# STM32F446_front_pane_-_south_-_v3.net
KiCad netlist of a schematic drawn in EAGLE
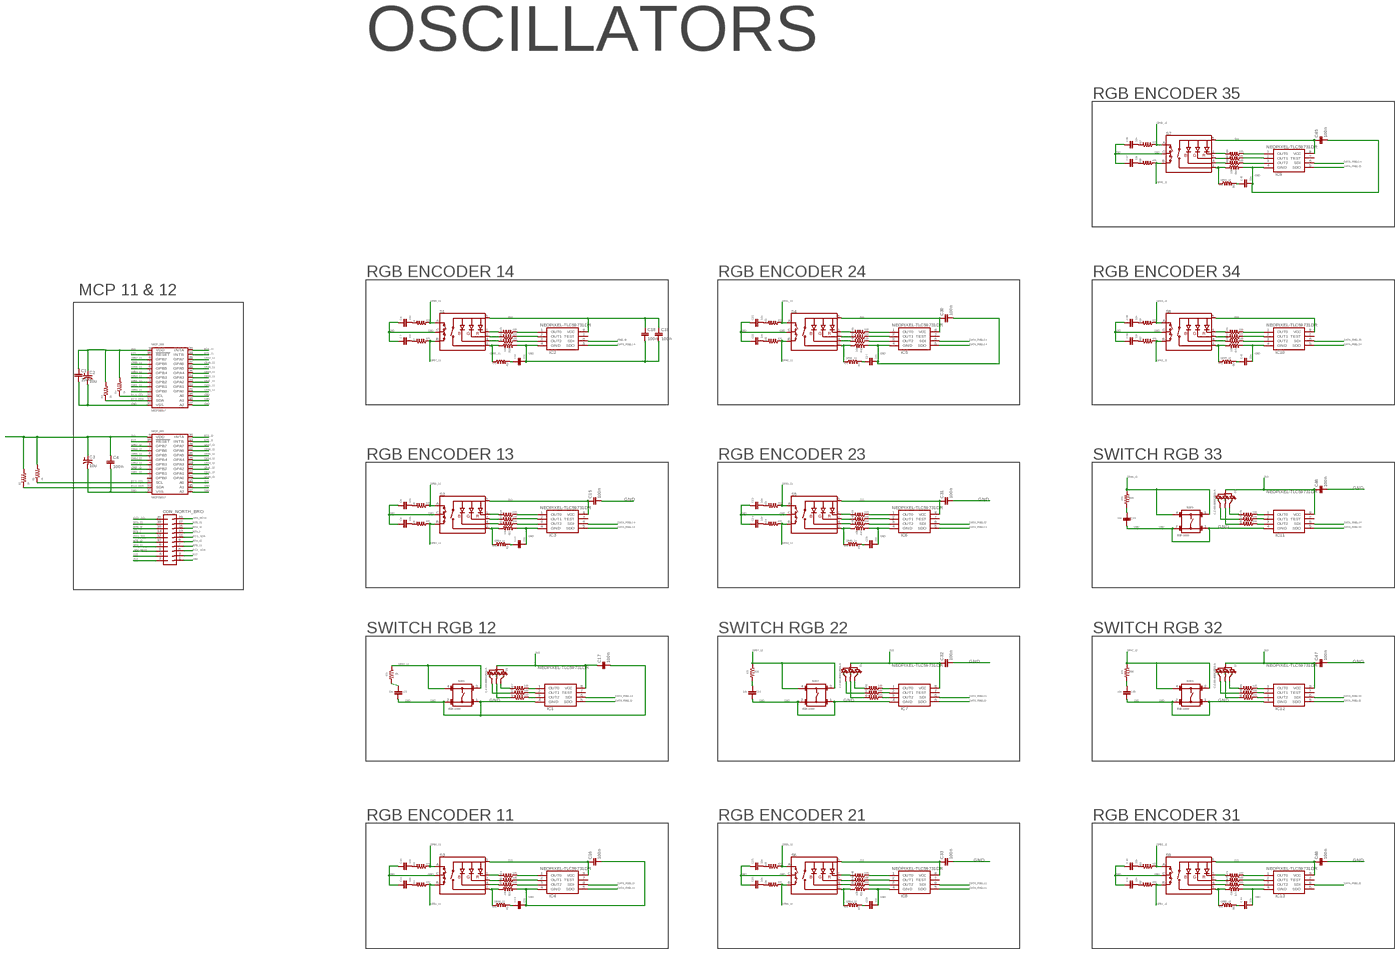
[diagram p0: schematic, sheet 1, overview]
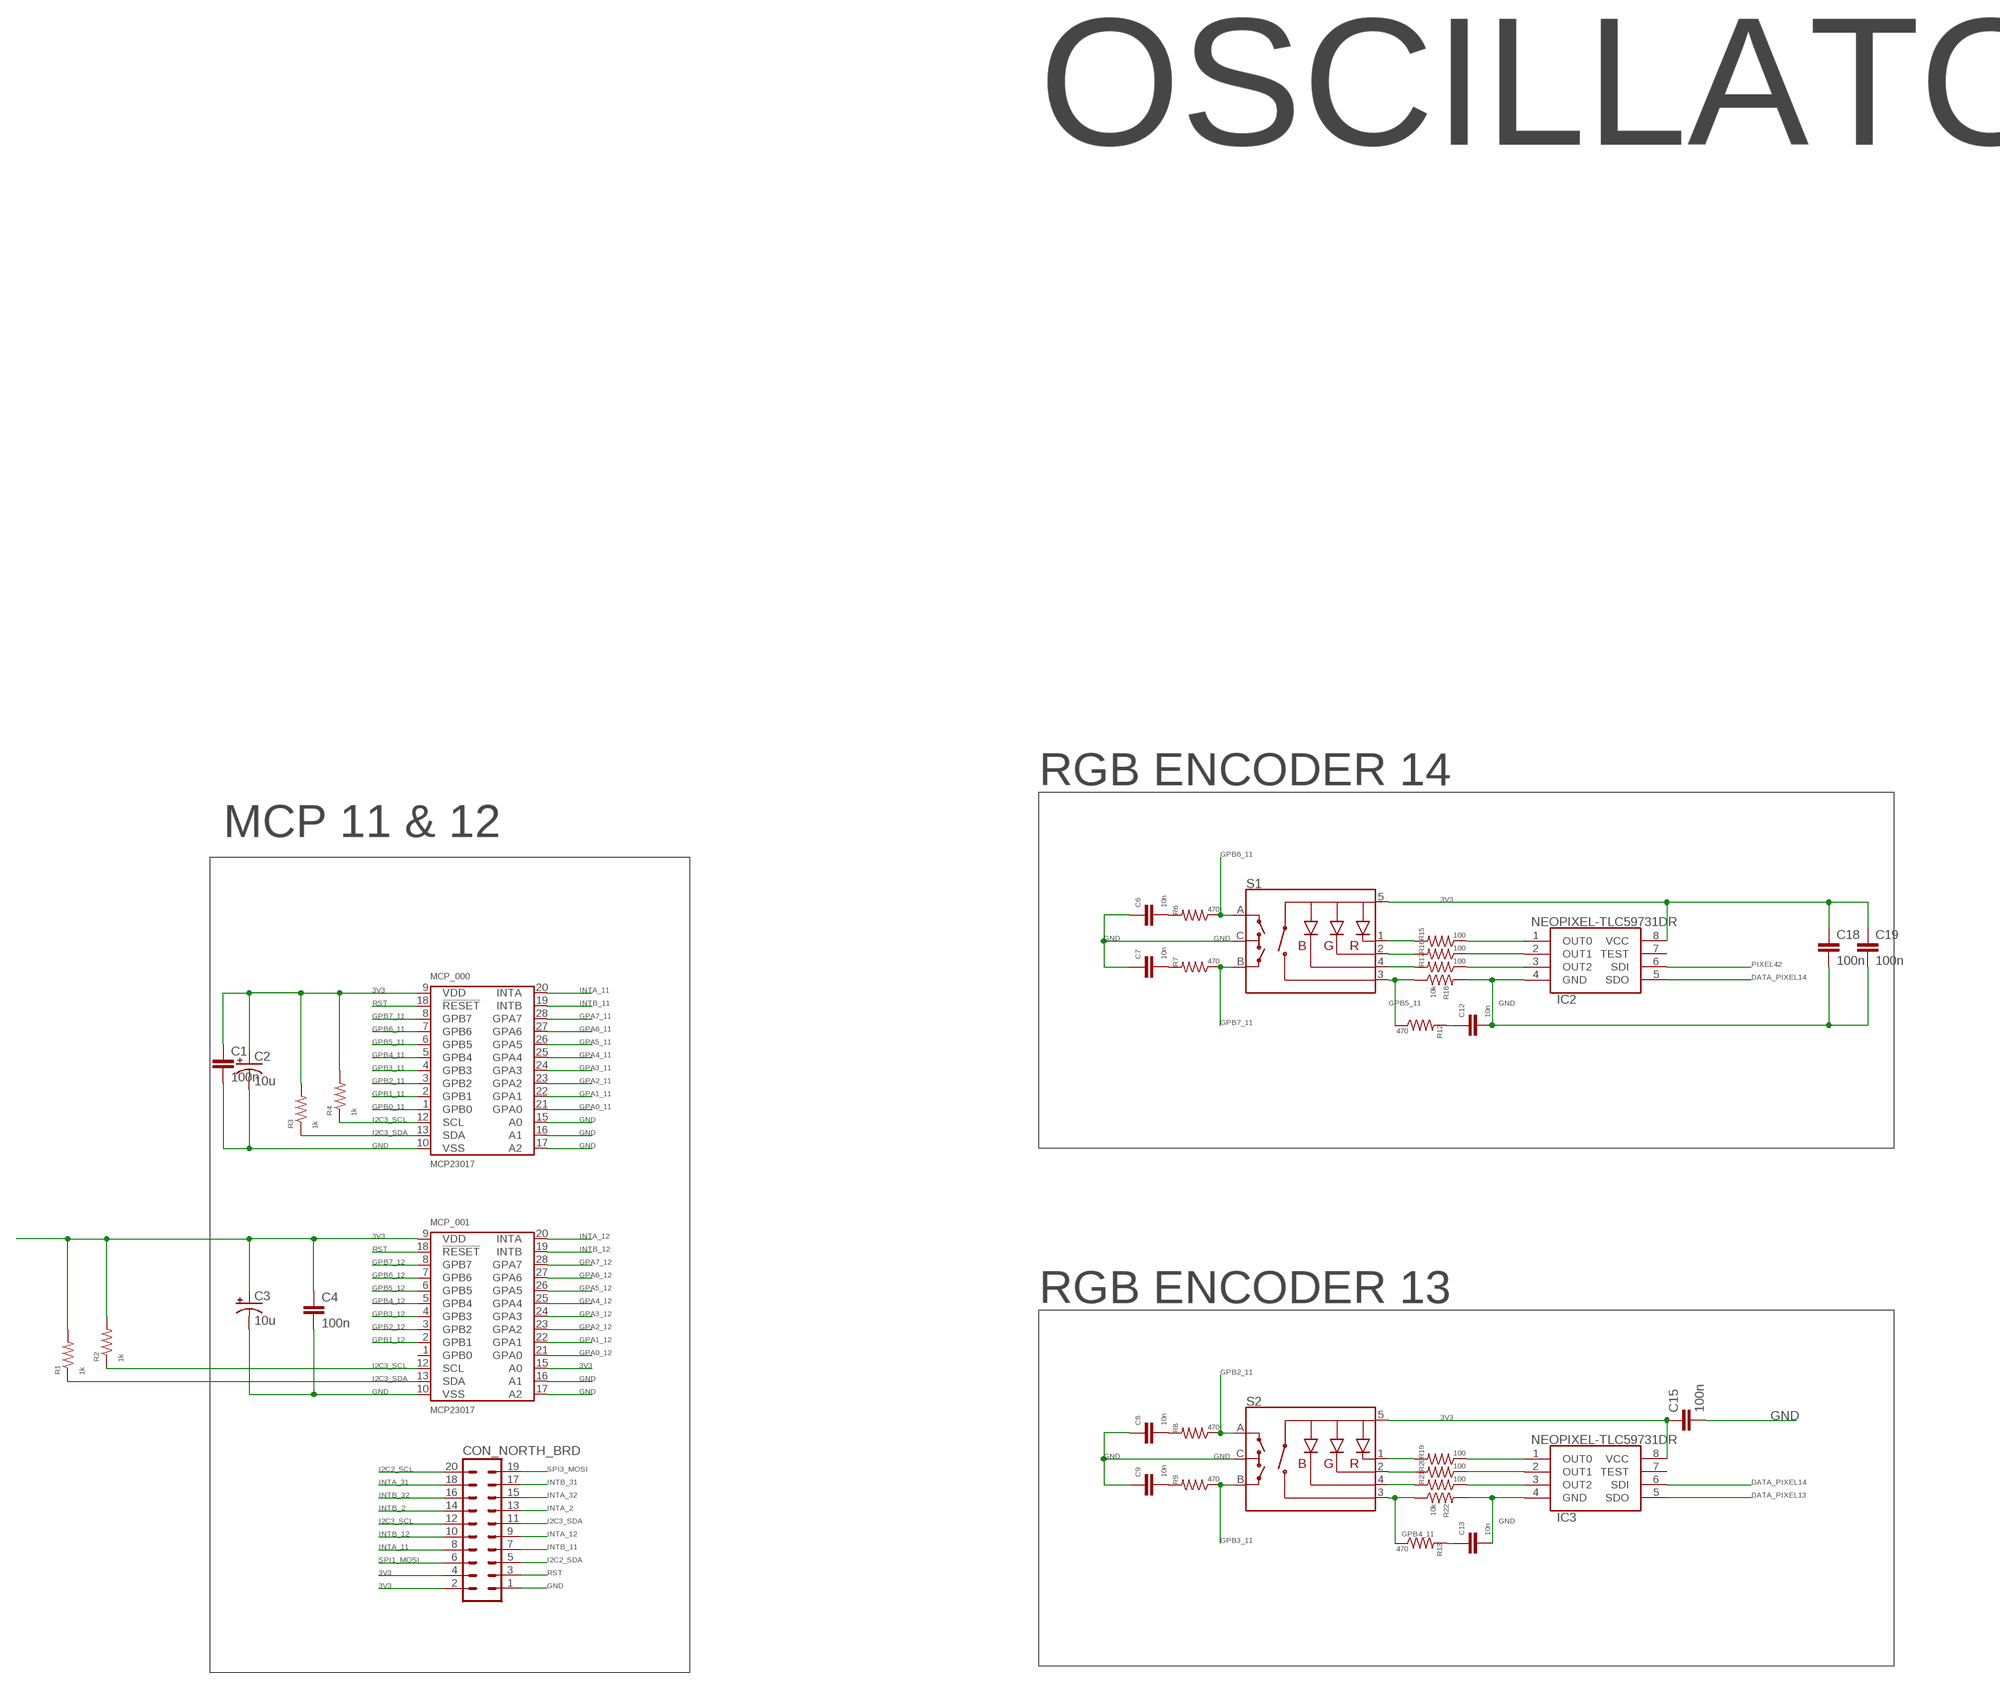
[diagram p1: schematic, sheet 1, part 1 of 4]
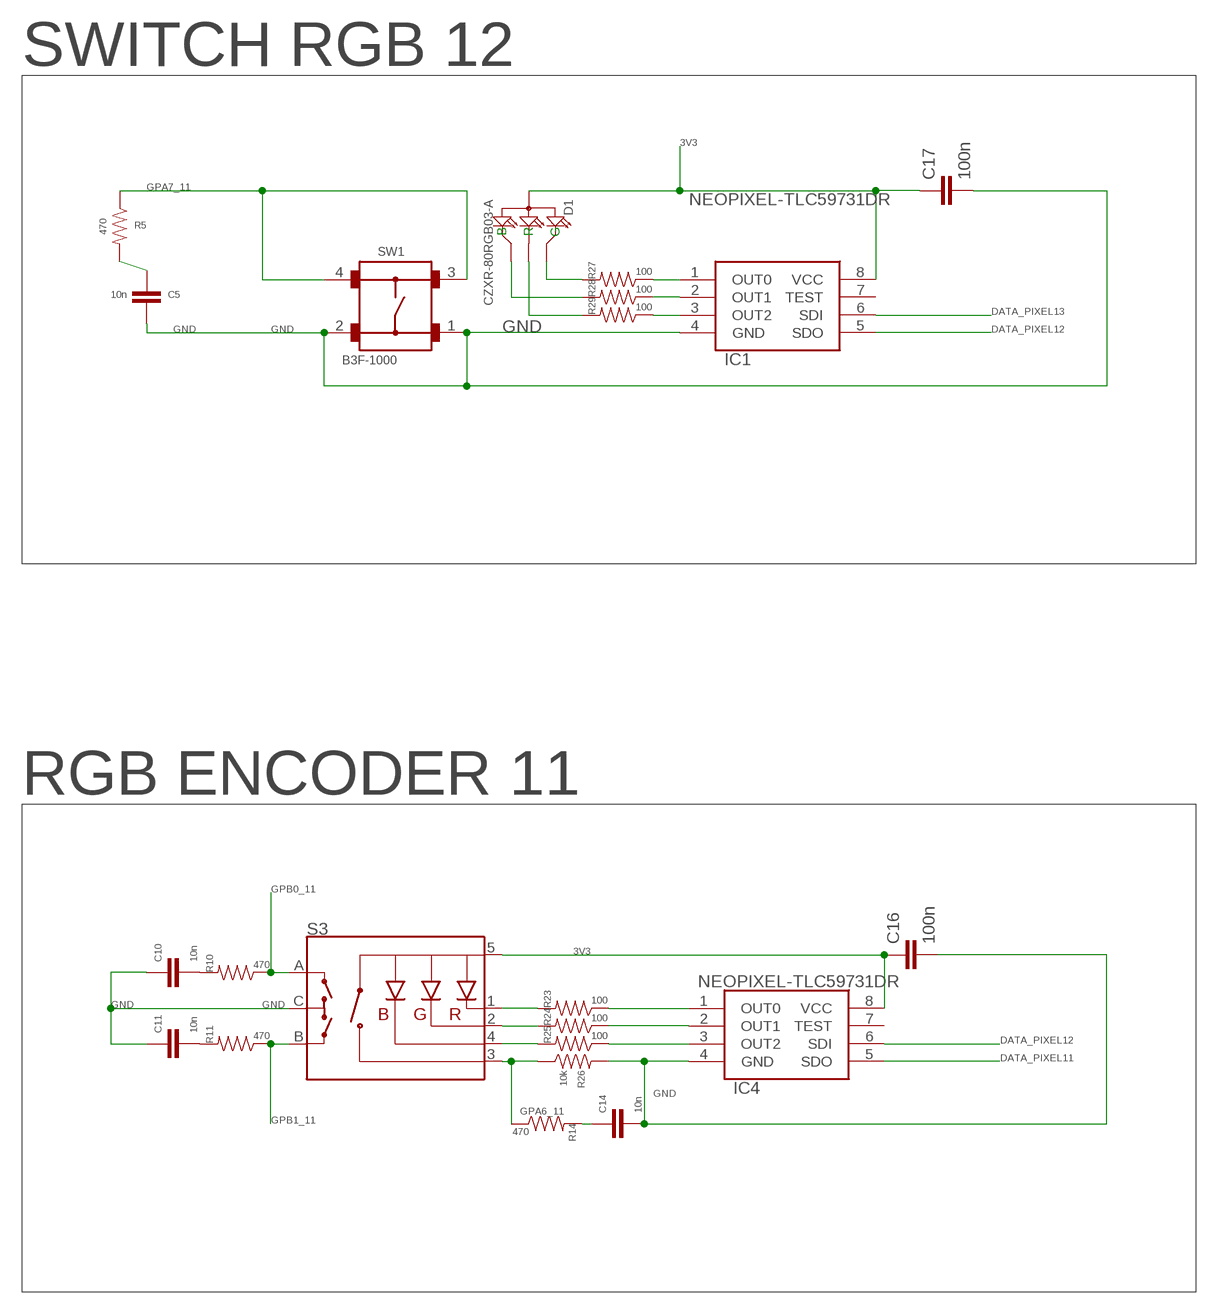
[diagram p2: schematic, sheet 1, part 2 of 4]
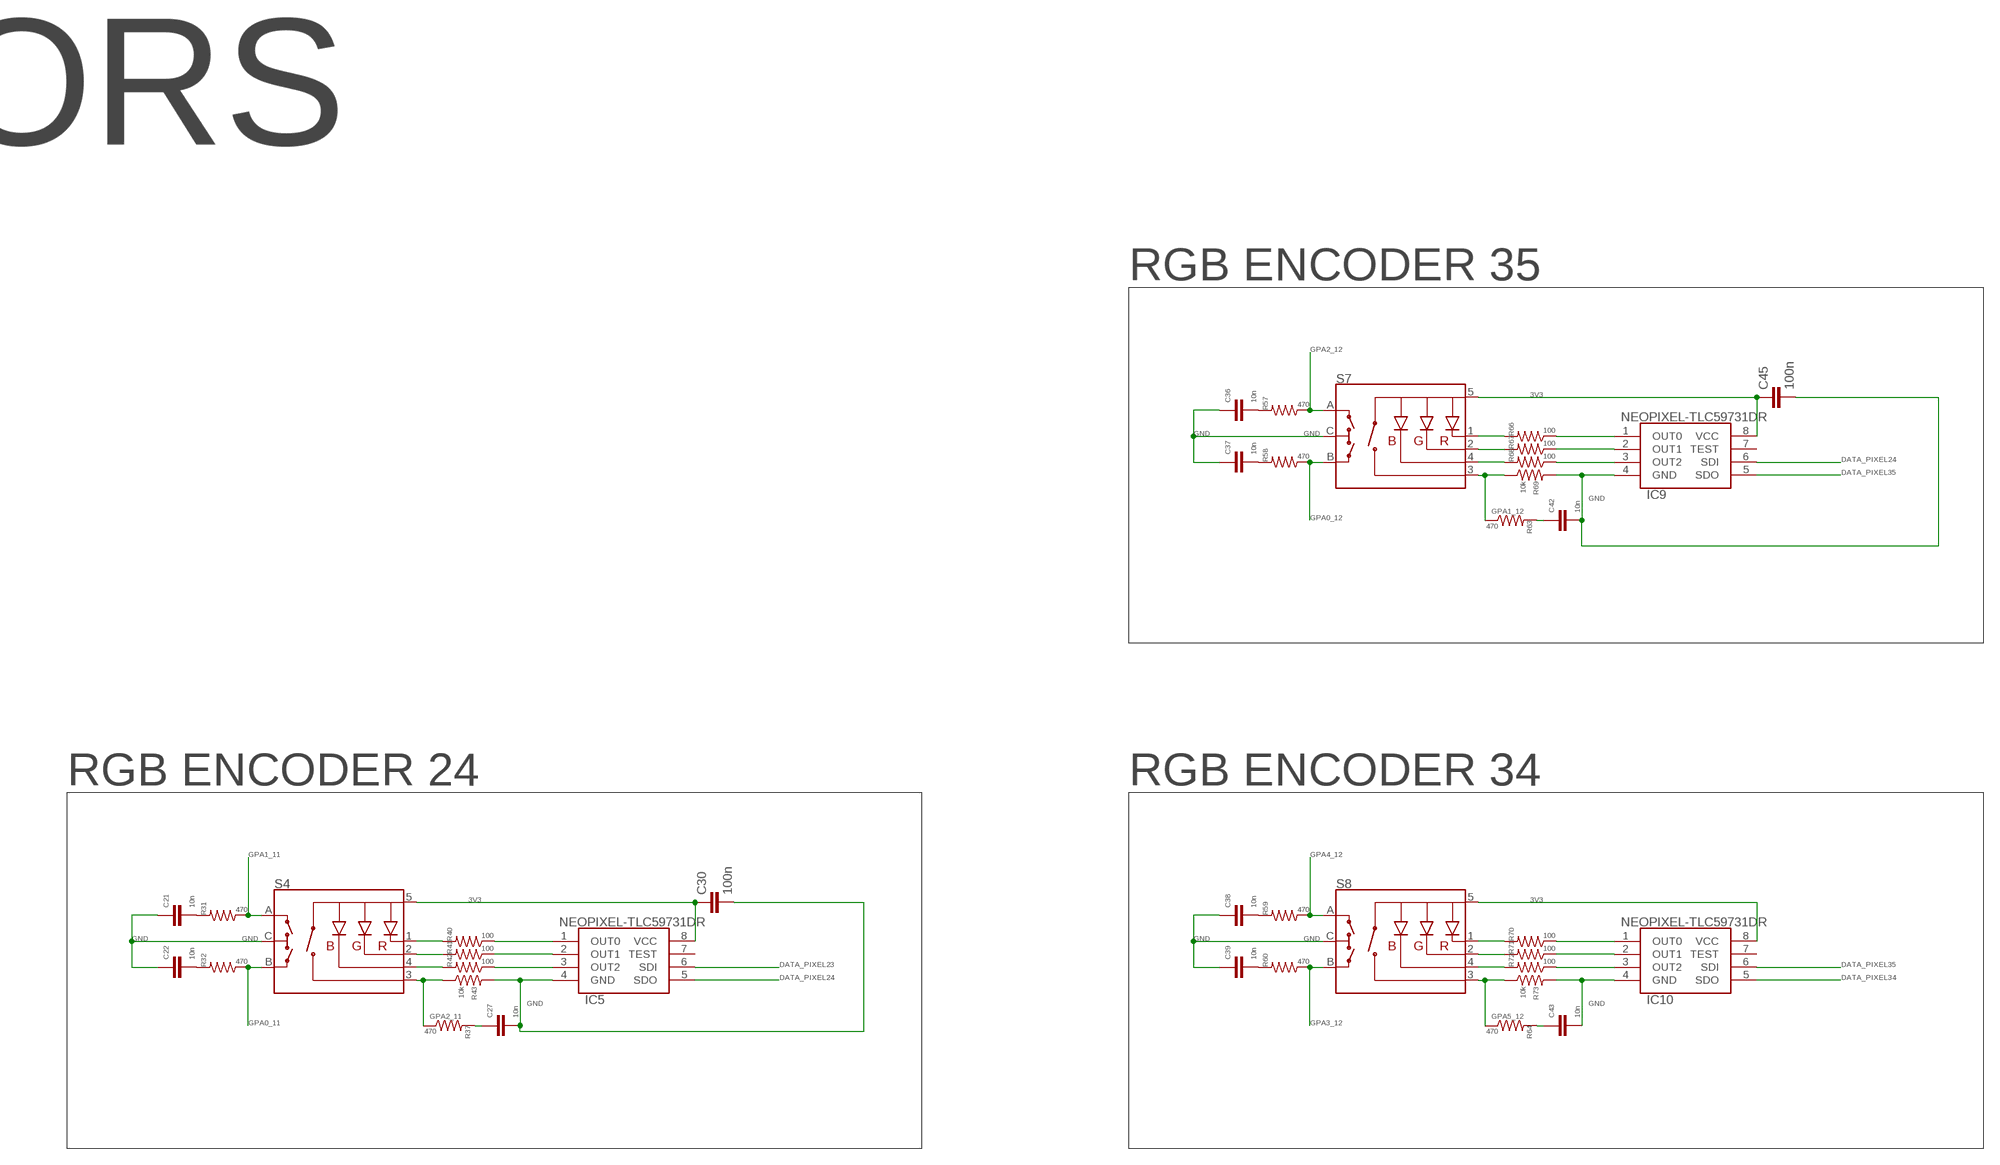
[diagram p3: schematic, sheet 1, part 3 of 4]
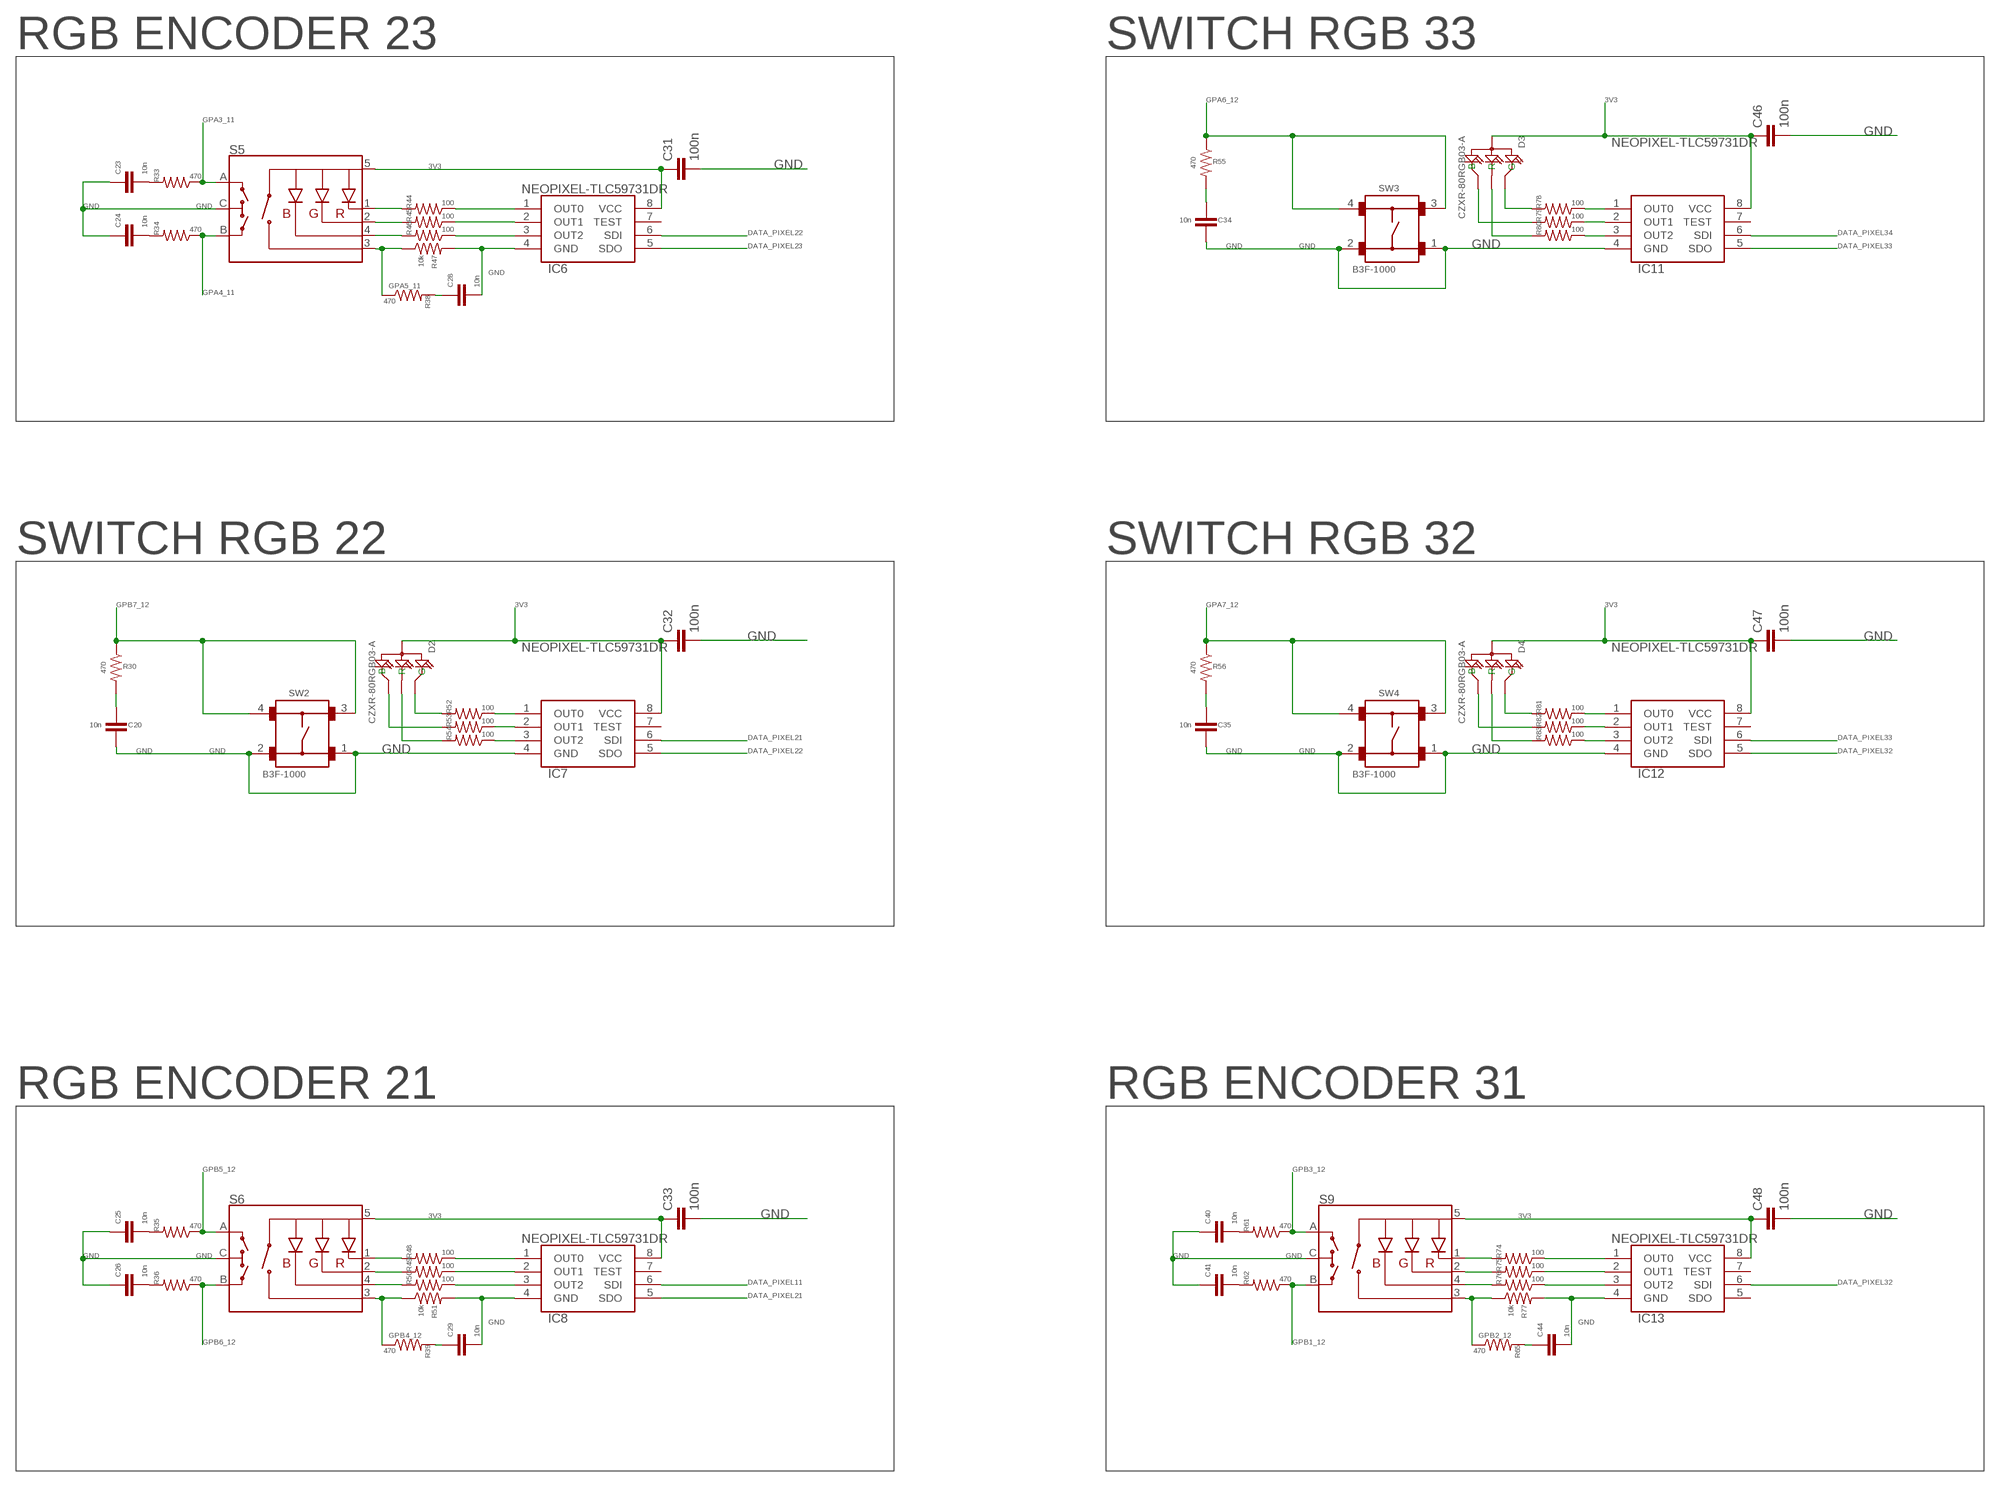
[diagram p4: schematic, sheet 1, part 4 of 4]
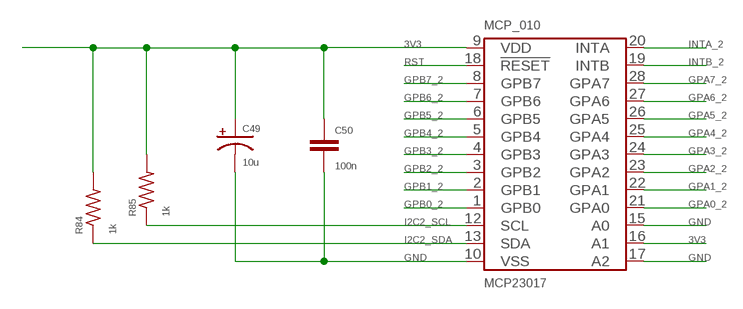
[diagram p5: schematic, sheet 2, part 1 of 2]
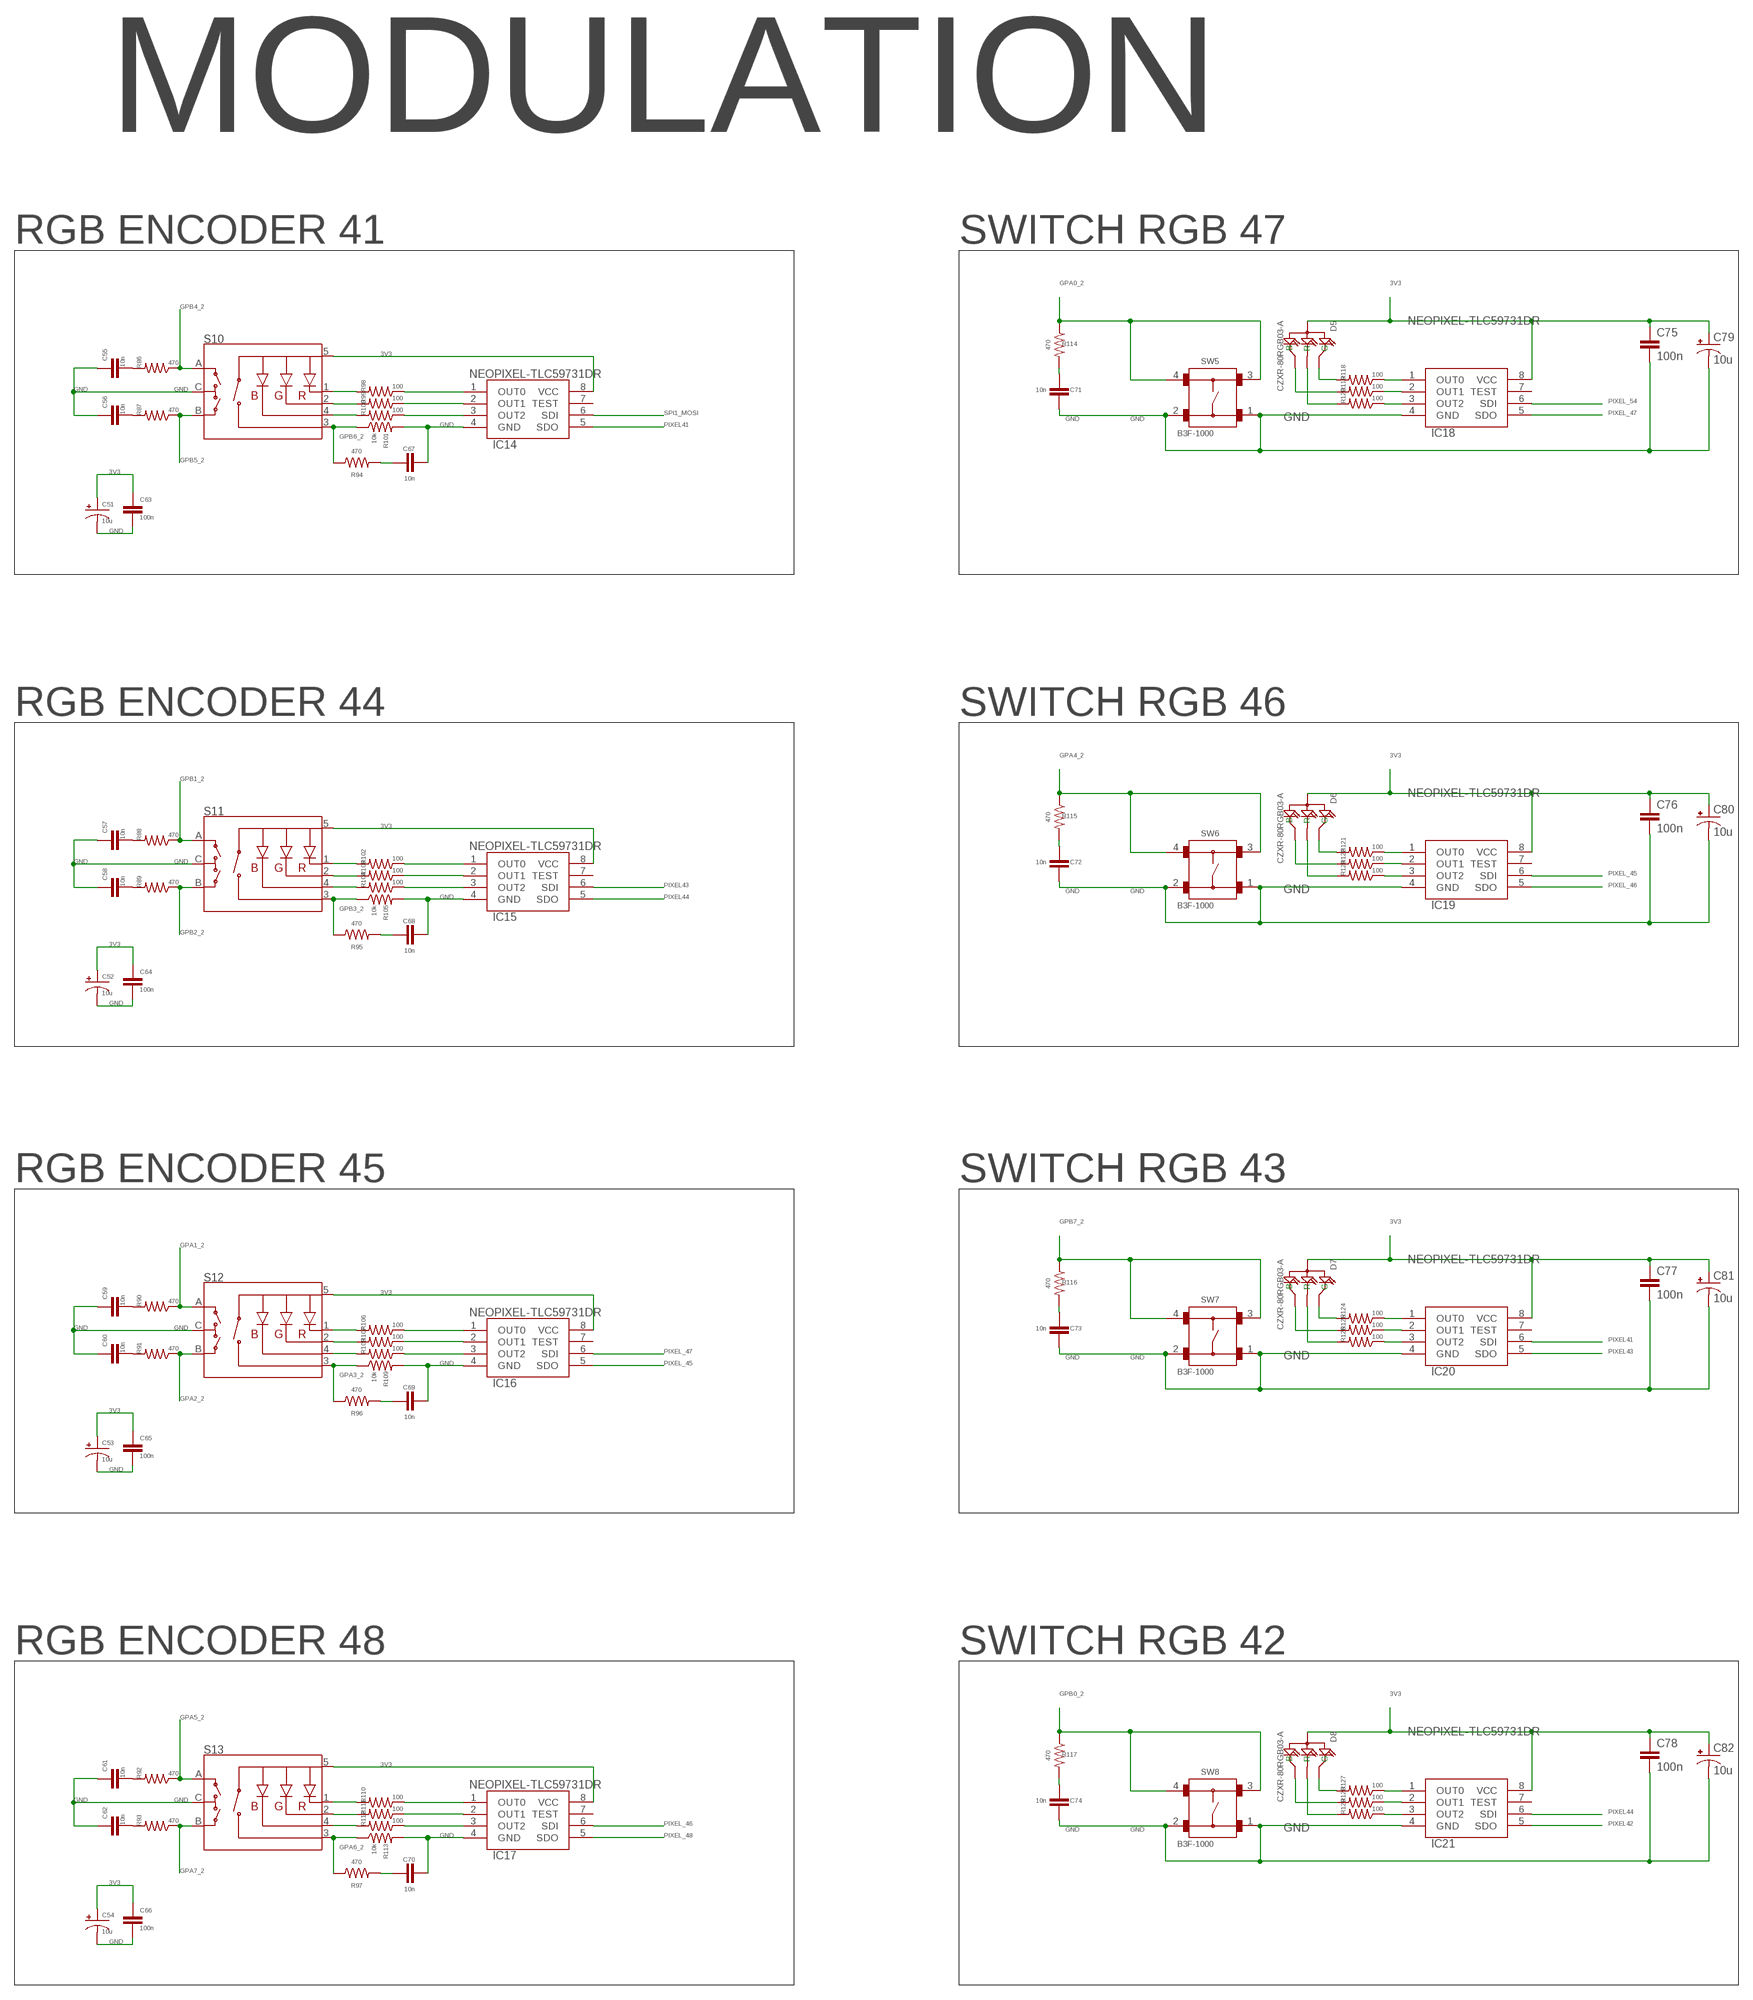
[diagram p6: schematic, sheet 2, part 2 of 2]
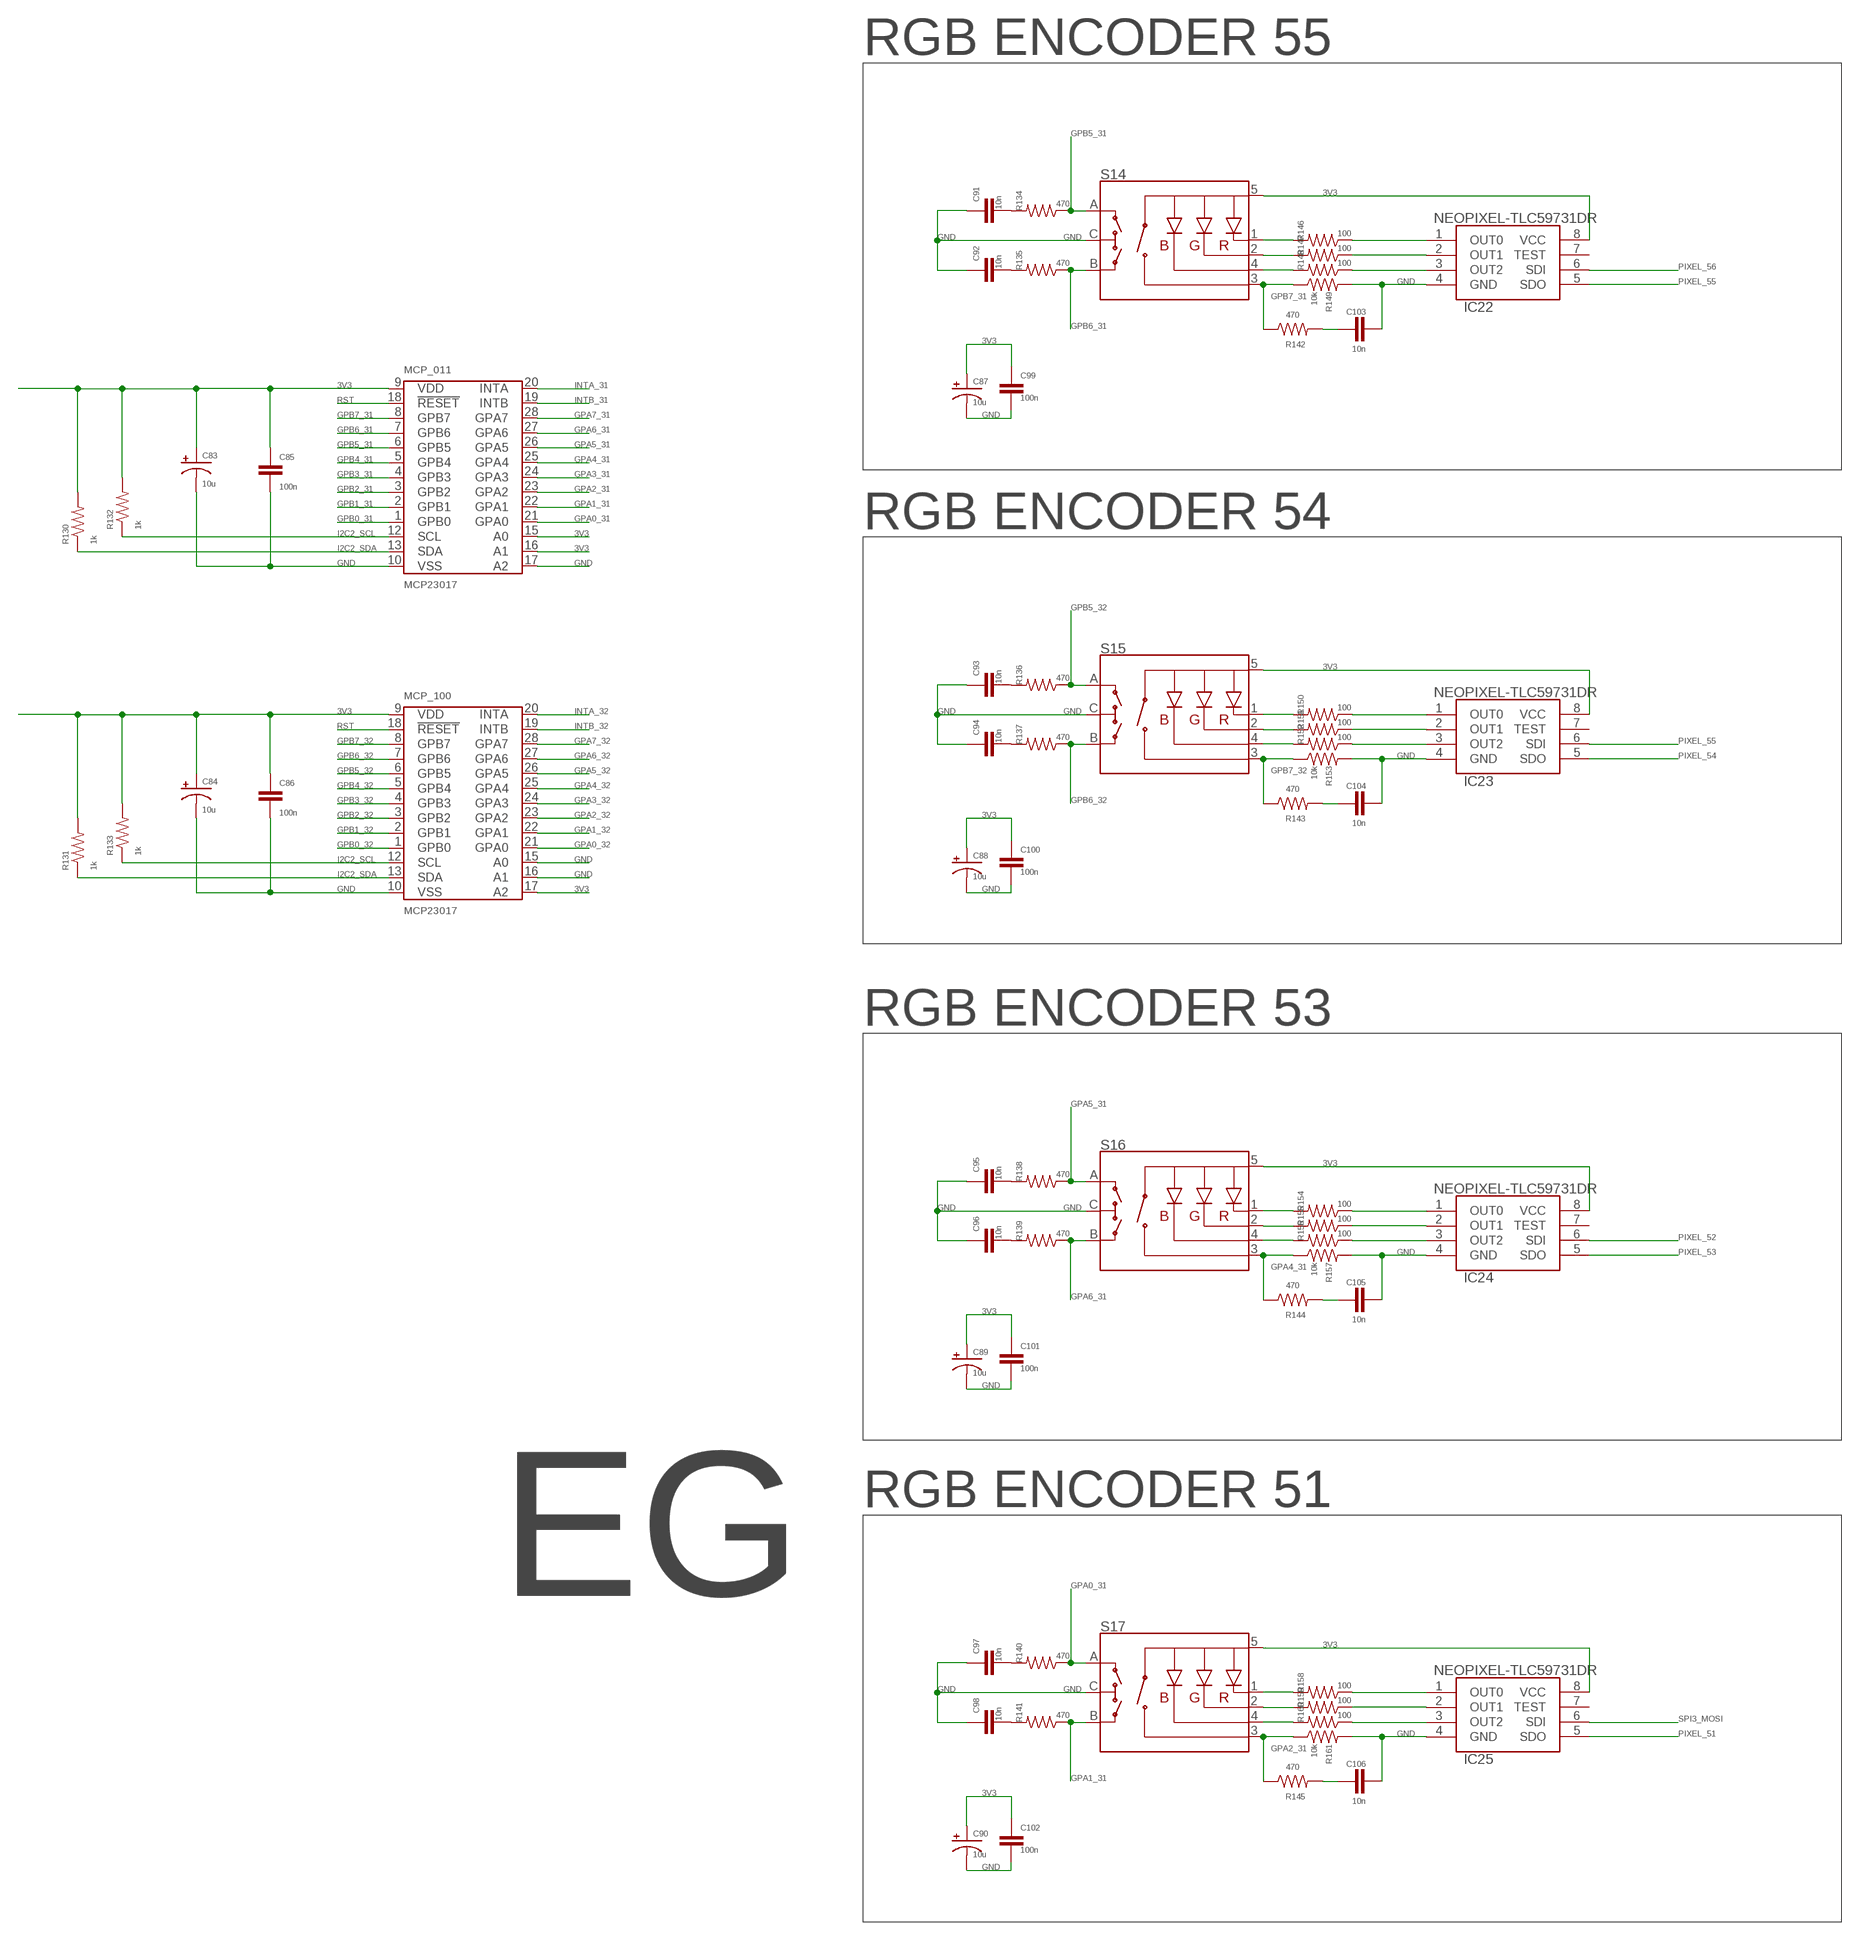
[diagram p7: schematic, sheet 3, part 1 of 2]
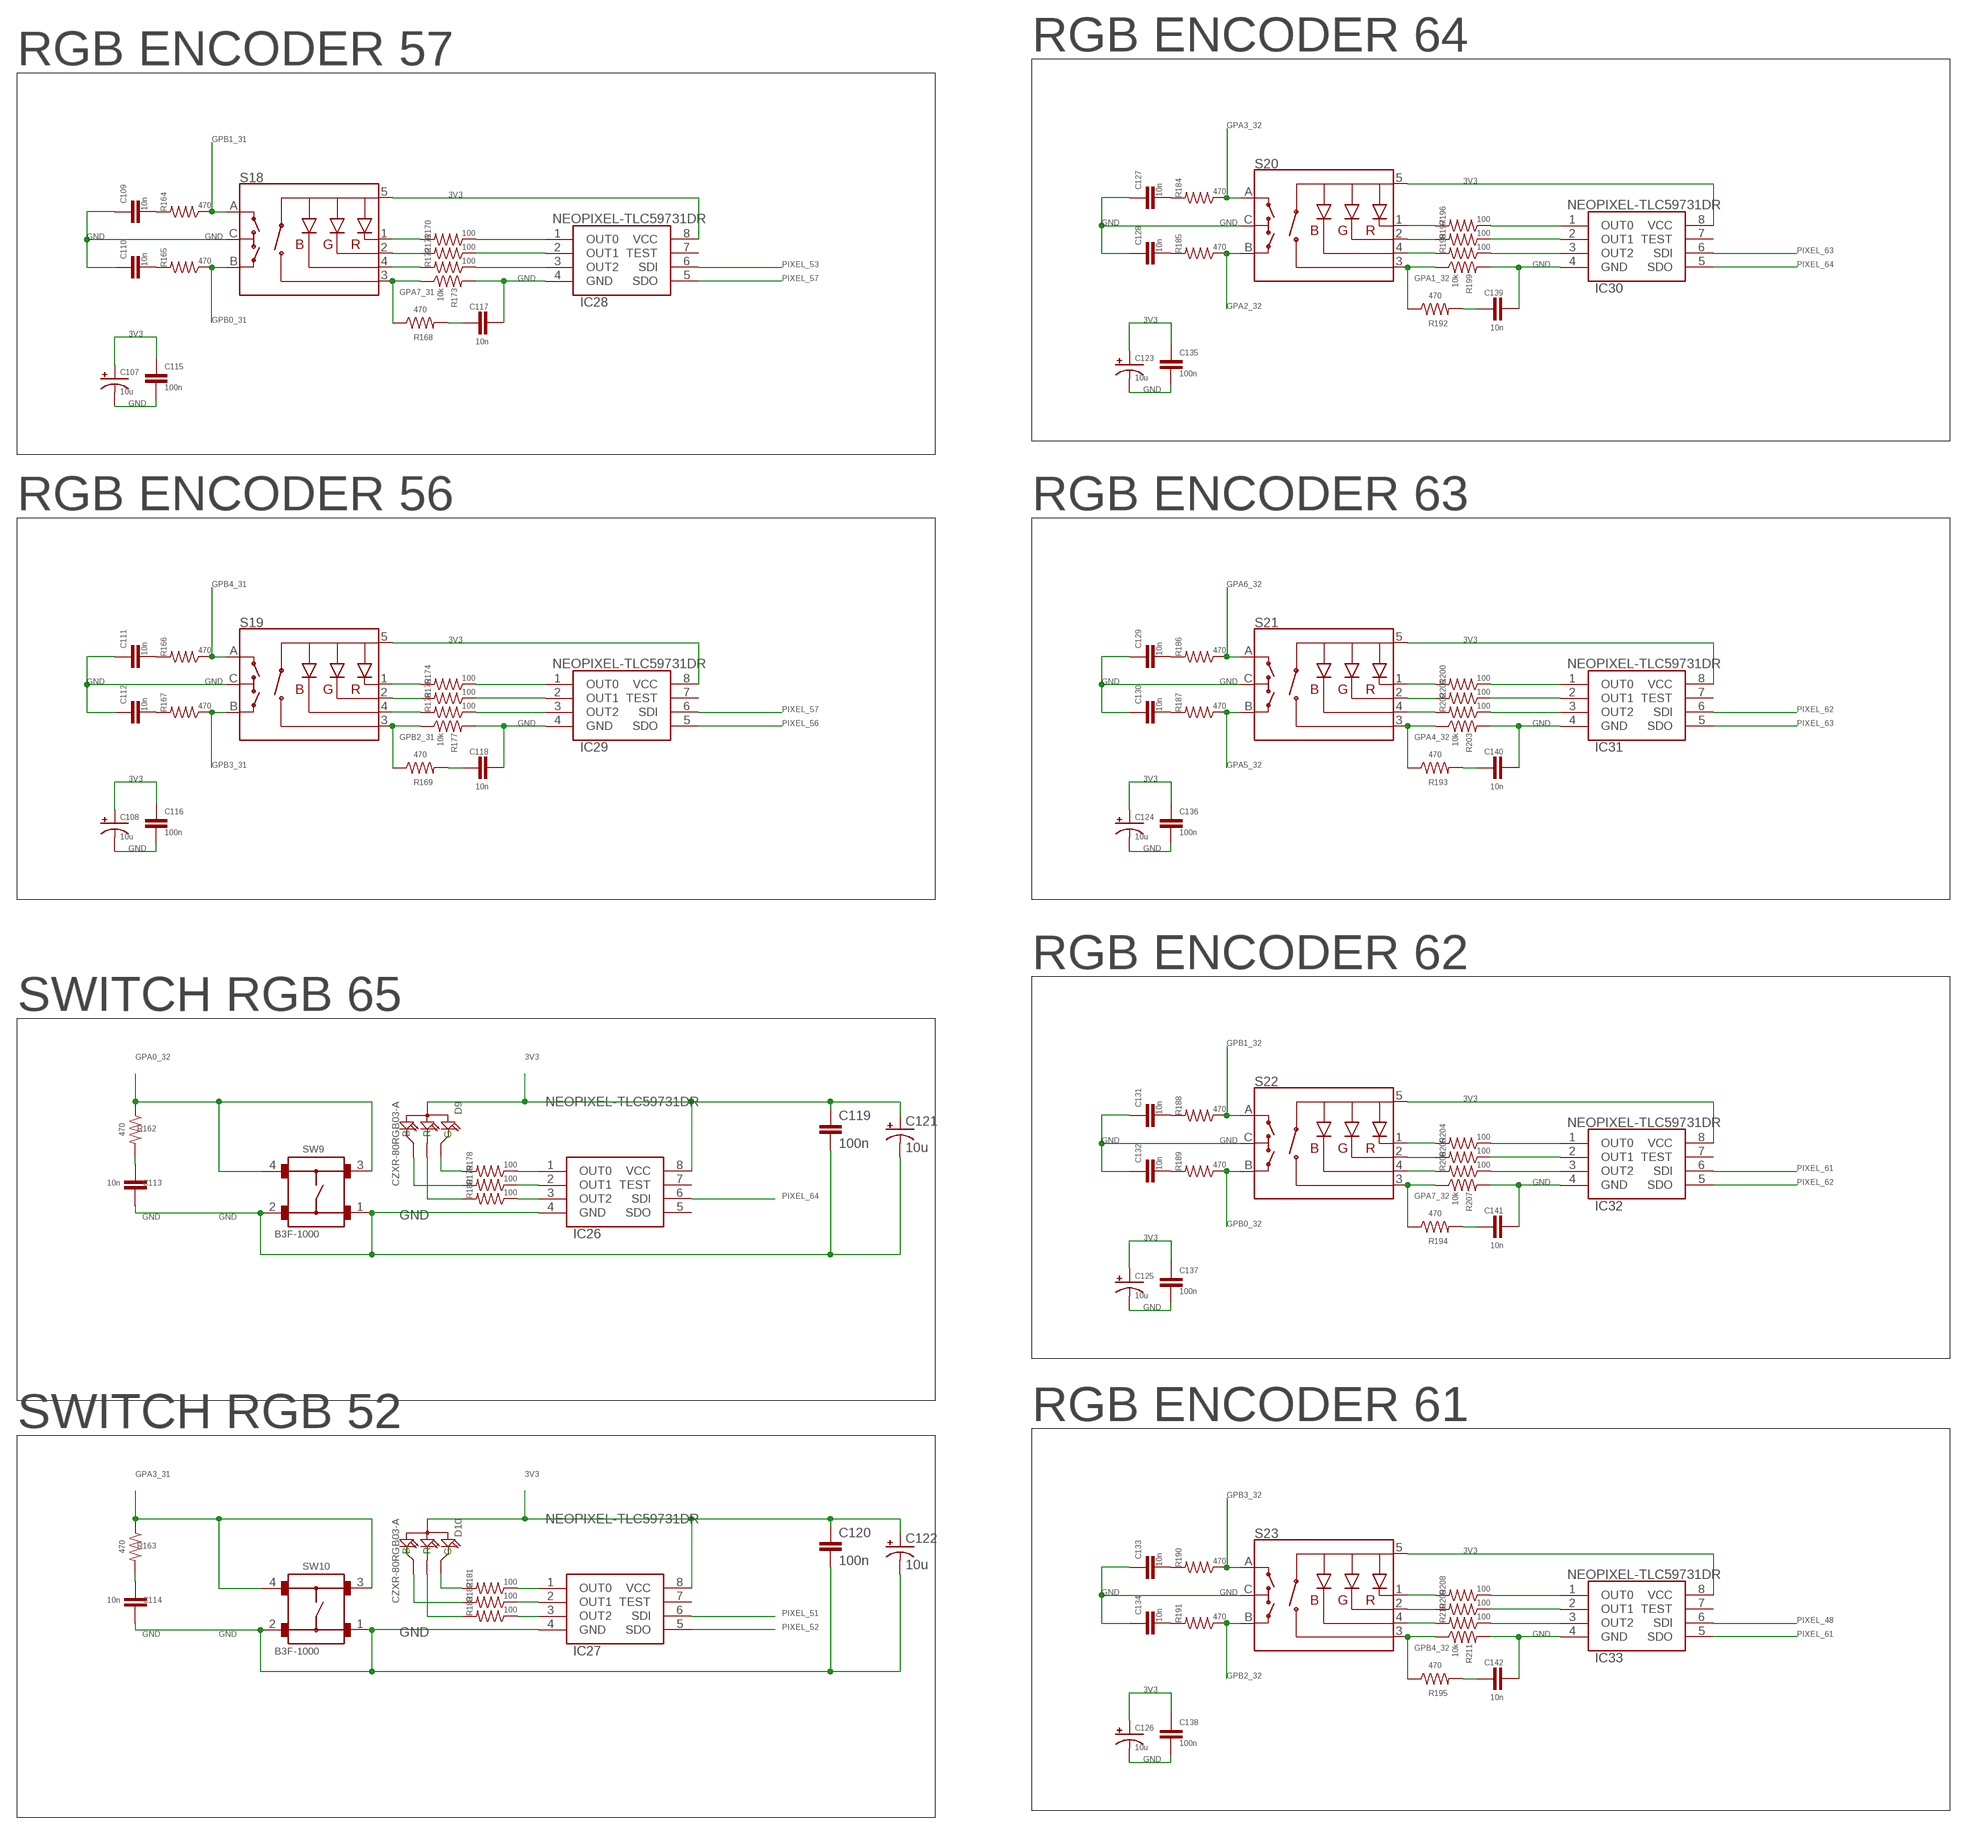
[diagram p8: schematic, sheet 3, part 2 of 2]

(export (version "E")
  (design (tool "Eeschema 10.0.6"))
  (components
    (comp (ref "C83")
      (value "10u")
      (footprint "eagle-import:CPOL2917")
      (libsource (lib "eagle-import") (part "PASSIF-CPOL-US2917"))
    )
    (comp (ref "C84")
      (value "10u")
      (footprint "eagle-import:CPOL2917")
      (libsource (lib "eagle-import") (part "PASSIF-CPOL-US2917"))
    )
    (comp (ref "C85")
      (value "100n")
      (footprint "eagle-import:0805-CAP")
      (libsource (lib "eagle-import") (part "PASSIF-CAP-0805"))
    )
    (comp (ref "C86")
      (value "100n")
      (footprint "eagle-import:0805-CAP")
      (libsource (lib "eagle-import") (part "PASSIF-CAP-0805"))
    )
    (comp (ref "C87")
      (value "10u")
      (footprint "eagle-import:CPOL2917")
      (libsource (lib "eagle-import") (part "PASSIF-CPOL-US2917"))
    )
    (comp (ref "C88")
      (value "10u")
      (footprint "eagle-import:CPOL2917")
      (libsource (lib "eagle-import") (part "PASSIF-CPOL-US2917"))
    )
    (comp (ref "C89")
      (value "10u")
      (footprint "eagle-import:CPOL2917")
      (libsource (lib "eagle-import") (part "PASSIF-CPOL-US2917"))
    )
    (comp (ref "C90")
      (value "10u")
      (footprint "eagle-import:CPOL2917")
      (libsource (lib "eagle-import") (part "PASSIF-CPOL-US2917"))
    )
    (comp (ref "C91")
      (value "10n")
      (footprint "eagle-import:0805-CAP")
      (libsource (lib "eagle-import") (part "PASSIF-CAP-0805"))
    )
    (comp (ref "C92")
      (value "10n")
      (footprint "eagle-import:0805-CAP")
      (libsource (lib "eagle-import") (part "PASSIF-CAP-0805"))
    )
    (comp (ref "C93")
      (value "10n")
      (footprint "eagle-import:0805-CAP")
      (libsource (lib "eagle-import") (part "PASSIF-CAP-0805"))
    )
    (comp (ref "C94")
      (value "10n")
      (footprint "eagle-import:0805-CAP")
      (libsource (lib "eagle-import") (part "PASSIF-CAP-0805"))
    )
    (comp (ref "C95")
      (value "10n")
      (footprint "eagle-import:0805-CAP")
      (libsource (lib "eagle-import") (part "PASSIF-CAP-0805"))
    )
    (comp (ref "C96")
      (value "10n")
      (footprint "eagle-import:0805-CAP")
      (libsource (lib "eagle-import") (part "PASSIF-CAP-0805"))
    )
    (comp (ref "C97")
      (value "10n")
      (footprint "eagle-import:0805-CAP")
      (libsource (lib "eagle-import") (part "PASSIF-CAP-0805"))
    )
    (comp (ref "C98")
      (value "10n")
      (footprint "eagle-import:0805-CAP")
      (libsource (lib "eagle-import") (part "PASSIF-CAP-0805"))
    )
    (comp (ref "C99")
      (value "100n")
      (footprint "eagle-import:0805-CAP")
      (libsource (lib "eagle-import") (part "PASSIF-CAP-0805"))
    )
    (comp (ref "C100")
      (value "100n")
      (footprint "eagle-import:0805-CAP")
      (libsource (lib "eagle-import") (part "PASSIF-CAP-0805"))
    )
    (comp (ref "C101")
      (value "100n")
      (footprint "eagle-import:0805-CAP")
      (libsource (lib "eagle-import") (part "PASSIF-CAP-0805"))
    )
    (comp (ref "C102")
      (value "100n")
      (footprint "eagle-import:0805-CAP")
      (libsource (lib "eagle-import") (part "PASSIF-CAP-0805"))
    )
    (comp (ref "C103")
      (value "10n")
      (footprint "eagle-import:0805-CAP")
      (libsource (lib "eagle-import") (part "PASSIF-CAP-0805"))
    )
    (comp (ref "C104")
      (value "10n")
      (footprint "eagle-import:0805-CAP")
      (libsource (lib "eagle-import") (part "PASSIF-CAP-0805"))
    )
    (comp (ref "C105")
      (value "10n")
      (footprint "eagle-import:0805-CAP")
      (libsource (lib "eagle-import") (part "PASSIF-CAP-0805"))
    )
    (comp (ref "C106")
      (value "10n")
      (footprint "eagle-import:0805-CAP")
      (libsource (lib "eagle-import") (part "PASSIF-CAP-0805"))
    )
    (comp (ref "C107")
      (value "10u")
      (footprint "eagle-import:CPOL2917")
      (libsource (lib "eagle-import") (part "PASSIF-CPOL-US2917"))
    )
    (comp (ref "C108")
      (value "10u")
      (footprint "eagle-import:CPOL2917")
      (libsource (lib "eagle-import") (part "PASSIF-CPOL-US2917"))
    )
    (comp (ref "C109")
      (value "10n")
      (footprint "eagle-import:0805-CAP")
      (libsource (lib "eagle-import") (part "PASSIF-CAP-0805"))
    )
    (comp (ref "C110")
      (value "10n")
      (footprint "eagle-import:0805-CAP")
      (libsource (lib "eagle-import") (part "PASSIF-CAP-0805"))
    )
    (comp (ref "C111")
      (value "10n")
      (footprint "eagle-import:0805-CAP")
      (libsource (lib "eagle-import") (part "PASSIF-CAP-0805"))
    )
    (comp (ref "C112")
      (value "10n")
      (footprint "eagle-import:0805-CAP")
      (libsource (lib "eagle-import") (part "PASSIF-CAP-0805"))
    )
    (comp (ref "C113")
      (value "10n")
      (footprint "eagle-import:0805-CAP")
      (libsource (lib "eagle-import") (part "PASSIF-CAP-0805"))
    )
    (comp (ref "C114")
      (value "10n")
      (footprint "eagle-import:0805-CAP")
      (libsource (lib "eagle-import") (part "PASSIF-CAP-0805"))
    )
    (comp (ref "C115")
      (value "100n")
      (footprint "eagle-import:0805-CAP")
      (libsource (lib "eagle-import") (part "PASSIF-CAP-0805"))
    )
    (comp (ref "C116")
      (value "100n")
      (footprint "eagle-import:0805-CAP")
      (libsource (lib "eagle-import") (part "PASSIF-CAP-0805"))
    )
    (comp (ref "C117")
      (value "10n")
      (footprint "eagle-import:0805-CAP")
      (libsource (lib "eagle-import") (part "PASSIF-CAP-0805"))
    )
    (comp (ref "C118")
      (value "10n")
      (footprint "eagle-import:0805-CAP")
      (libsource (lib "eagle-import") (part "PASSIF-CAP-0805"))
    )
    (comp (ref "C119")
      (value "100n")
      (footprint "eagle-import:0805-CAP")
      (libsource (lib "eagle-import") (part "PASSIF-CAP-0805"))
    )
    (comp (ref "C120")
      (value "100n")
      (footprint "eagle-import:0805-CAP")
      (libsource (lib "eagle-import") (part "PASSIF-CAP-0805"))
    )
    (comp (ref "C121")
      (value "10u")
      (footprint "eagle-import:CPOL2917")
      (libsource (lib "eagle-import") (part "PASSIF-CPOL-US2917"))
    )
    (comp (ref "C122")
      (value "10u")
      (footprint "eagle-import:CPOL2917")
      (libsource (lib "eagle-import") (part "PASSIF-CPOL-US2917"))
    )
    (comp (ref "C123")
      (value "10u")
      (footprint "eagle-import:CPOL2917")
      (libsource (lib "eagle-import") (part "PASSIF-CPOL-US2917"))
    )
    (comp (ref "C124")
      (value "10u")
      (footprint "eagle-import:CPOL2917")
      (libsource (lib "eagle-import") (part "PASSIF-CPOL-US2917"))
    )
    (comp (ref "C125")
      (value "10u")
      (footprint "eagle-import:CPOL2917")
      (libsource (lib "eagle-import") (part "PASSIF-CPOL-US2917"))
    )
    (comp (ref "C126")
      (value "10u")
      (footprint "eagle-import:CPOL2917")
      (libsource (lib "eagle-import") (part "PASSIF-CPOL-US2917"))
    )
    (comp (ref "C127")
      (value "10n")
      (footprint "eagle-import:0805-CAP")
      (libsource (lib "eagle-import") (part "PASSIF-CAP-0805"))
    )
    (comp (ref "C128")
      (value "10n")
      (footprint "eagle-import:0805-CAP")
      (libsource (lib "eagle-import") (part "PASSIF-CAP-0805"))
    )
    (comp (ref "C129")
      (value "10n")
      (footprint "eagle-import:0805-CAP")
      (libsource (lib "eagle-import") (part "PASSIF-CAP-0805"))
    )
    (comp (ref "C130")
      (value "10n")
      (footprint "eagle-import:0805-CAP")
      (libsource (lib "eagle-import") (part "PASSIF-CAP-0805"))
    )
    (comp (ref "C131")
      (value "10n")
      (footprint "eagle-import:0805-CAP")
      (libsource (lib "eagle-import") (part "PASSIF-CAP-0805"))
    )
    (comp (ref "C132")
      (value "10n")
      (footprint "eagle-import:0805-CAP")
      (libsource (lib "eagle-import") (part "PASSIF-CAP-0805"))
    )
    (comp (ref "C133")
      (value "10n")
      (footprint "eagle-import:0805-CAP")
      (libsource (lib "eagle-import") (part "PASSIF-CAP-0805"))
    )
    (comp (ref "C134")
      (value "10n")
      (footprint "eagle-import:0805-CAP")
      (libsource (lib "eagle-import") (part "PASSIF-CAP-0805"))
    )
    (comp (ref "C135")
      (value "100n")
      (footprint "eagle-import:0805-CAP")
      (libsource (lib "eagle-import") (part "PASSIF-CAP-0805"))
    )
    (comp (ref "C136")
      (value "100n")
      (footprint "eagle-import:0805-CAP")
      (libsource (lib "eagle-import") (part "PASSIF-CAP-0805"))
    )
    (comp (ref "C137")
      (value "100n")
      (footprint "eagle-import:0805-CAP")
      (libsource (lib "eagle-import") (part "PASSIF-CAP-0805"))
    )
    (comp (ref "C138")
      (value "100n")
      (footprint "eagle-import:0805-CAP")
      (libsource (lib "eagle-import") (part "PASSIF-CAP-0805"))
    )
    (comp (ref "C139")
      (value "10n")
      (footprint "eagle-import:0805-CAP")
      (libsource (lib "eagle-import") (part "PASSIF-CAP-0805"))
    )
    (comp (ref "C140")
      (value "10n")
      (footprint "eagle-import:0805-CAP")
      (libsource (lib "eagle-import") (part "PASSIF-CAP-0805"))
    )
    (comp (ref "C141")
      (value "10n")
      (footprint "eagle-import:0805-CAP")
      (libsource (lib "eagle-import") (part "PASSIF-CAP-0805"))
    )
    (comp (ref "C142")
      (value "10n")
      (footprint "eagle-import:0805-CAP")
      (libsource (lib "eagle-import") (part "PASSIF-CAP-0805"))
    )
    (comp (ref "D9")
      (value "CZXR-80RGB03-A")
      (footprint "eagle-import:LED4-2.0-D8.0MM")
      (libsource (lib "eagle-import") (part "DIP-LED-RGB-COMMON-ANODE(4P-D8MM)"))
    )
    (comp (ref "D10")
      (value "CZXR-80RGB03-A")
      (footprint "eagle-import:LED4-2.0-D8.0MM")
      (libsource (lib "eagle-import") (part "DIP-LED-RGB-COMMON-ANODE(4P-D8MM)"))
    )
    (comp (ref "IC22")
      (value "NEOPIXEL-TLC59731DR")
      (footprint "eagle-import:SOIC127P600X175-8N")
      (fields
        (field (name "ARROW_PART_NUMBER") "TLC59731DR")
        (field (name "MOUSER_PART_NUMBER") "595-TLC59731DR")
      )
      (libsource (lib "eagle-import") (part "NEOPIXEL-TLC59731DR"))
    )
    (comp (ref "IC23")
      (value "NEOPIXEL-TLC59731DR")
      (footprint "eagle-import:SOIC127P600X175-8N")
      (fields
        (field (name "ARROW_PART_NUMBER") "TLC59731DR")
        (field (name "MOUSER_PART_NUMBER") "595-TLC59731DR")
      )
      (libsource (lib "eagle-import") (part "NEOPIXEL-TLC59731DR"))
    )
    (comp (ref "IC24")
      (value "NEOPIXEL-TLC59731DR")
      (footprint "eagle-import:SOIC127P600X175-8N")
      (fields
        (field (name "ARROW_PART_NUMBER") "TLC59731DR")
        (field (name "MOUSER_PART_NUMBER") "595-TLC59731DR")
      )
      (libsource (lib "eagle-import") (part "NEOPIXEL-TLC59731DR"))
    )
    (comp (ref "IC25")
      (value "NEOPIXEL-TLC59731DR")
      (footprint "eagle-import:SOIC127P600X175-8N")
      (fields
        (field (name "ARROW_PART_NUMBER") "TLC59731DR")
        (field (name "MOUSER_PART_NUMBER") "595-TLC59731DR")
      )
      (libsource (lib "eagle-import") (part "NEOPIXEL-TLC59731DR"))
    )
    (comp (ref "IC26")
      (value "NEOPIXEL-TLC59731DR")
      (footprint "eagle-import:SOIC127P600X175-8N")
      (fields
        (field (name "ARROW_PART_NUMBER") "TLC59731DR")
        (field (name "MOUSER_PART_NUMBER") "595-TLC59731DR")
      )
      (libsource (lib "eagle-import") (part "NEOPIXEL-TLC59731DR"))
    )
    (comp (ref "IC27")
      (value "NEOPIXEL-TLC59731DR")
      (footprint "eagle-import:SOIC127P600X175-8N")
      (fields
        (field (name "ARROW_PART_NUMBER") "TLC59731DR")
        (field (name "MOUSER_PART_NUMBER") "595-TLC59731DR")
      )
      (libsource (lib "eagle-import") (part "NEOPIXEL-TLC59731DR"))
    )
    (comp (ref "IC28")
      (value "NEOPIXEL-TLC59731DR")
      (footprint "eagle-import:SOIC127P600X175-8N")
      (fields
        (field (name "ARROW_PART_NUMBER") "TLC59731DR")
        (field (name "MOUSER_PART_NUMBER") "595-TLC59731DR")
      )
      (libsource (lib "eagle-import") (part "NEOPIXEL-TLC59731DR"))
    )
    (comp (ref "IC29")
      (value "NEOPIXEL-TLC59731DR")
      (footprint "eagle-import:SOIC127P600X175-8N")
      (fields
        (field (name "ARROW_PART_NUMBER") "TLC59731DR")
        (field (name "MOUSER_PART_NUMBER") "595-TLC59731DR")
      )
      (libsource (lib "eagle-import") (part "NEOPIXEL-TLC59731DR"))
    )
    (comp (ref "IC30")
      (value "NEOPIXEL-TLC59731DR")
      (footprint "eagle-import:SOIC127P600X175-8N")
      (fields
        (field (name "ARROW_PART_NUMBER") "TLC59731DR")
        (field (name "MOUSER_PART_NUMBER") "595-TLC59731DR")
      )
      (libsource (lib "eagle-import") (part "NEOPIXEL-TLC59731DR"))
    )
    (comp (ref "IC31")
      (value "NEOPIXEL-TLC59731DR")
      (footprint "eagle-import:SOIC127P600X175-8N")
      (fields
        (field (name "ARROW_PART_NUMBER") "TLC59731DR")
        (field (name "MOUSER_PART_NUMBER") "595-TLC59731DR")
      )
      (libsource (lib "eagle-import") (part "NEOPIXEL-TLC59731DR"))
    )
    (comp (ref "IC32")
      (value "NEOPIXEL-TLC59731DR")
      (footprint "eagle-import:SOIC127P600X175-8N")
      (fields
        (field (name "ARROW_PART_NUMBER") "TLC59731DR")
        (field (name "MOUSER_PART_NUMBER") "595-TLC59731DR")
      )
      (libsource (lib "eagle-import") (part "NEOPIXEL-TLC59731DR"))
    )
    (comp (ref "IC33")
      (value "NEOPIXEL-TLC59731DR")
      (footprint "eagle-import:SOIC127P600X175-8N")
      (fields
        (field (name "ARROW_PART_NUMBER") "TLC59731DR")
        (field (name "MOUSER_PART_NUMBER") "595-TLC59731DR")
      )
      (libsource (lib "eagle-import") (part "NEOPIXEL-TLC59731DR"))
    )
    (comp (ref "MCP_011")
      (value "MCP23017")
      (footprint "eagle-import:SOIC-28")
      (libsource (lib "eagle-import") (part "MCP23017"))
    )
    (comp (ref "MCP_100")
      (value "MCP23017")
      (footprint "eagle-import:SOIC-28")
      (libsource (lib "eagle-import") (part "MCP23017"))
    )
    (comp (ref "R130")
      (value "1k")
      (footprint "eagle-import:R0805")
      (libsource (lib "eagle-import") (part "R-US_R0805"))
    )
    (comp (ref "R131")
      (value "1k")
      (footprint "eagle-import:R0805")
      (libsource (lib "eagle-import") (part "R-US_R0805"))
    )
    (comp (ref "R132")
      (value "1k")
      (footprint "eagle-import:R0805")
      (libsource (lib "eagle-import") (part "R-US_R0805"))
    )
    (comp (ref "R133")
      (value "1k")
      (footprint "eagle-import:R0805")
      (libsource (lib "eagle-import") (part "R-US_R0805"))
    )
    (comp (ref "R134")
      (value "470")
      (footprint "eagle-import:1206")
      (libsource (lib "eagle-import") (part "PASSIF-RESISTOR-1206"))
    )
    (comp (ref "R135")
      (value "470")
      (footprint "eagle-import:1206")
      (libsource (lib "eagle-import") (part "PASSIF-RESISTOR-1206"))
    )
    (comp (ref "R136")
      (value "470")
      (footprint "eagle-import:1206")
      (libsource (lib "eagle-import") (part "PASSIF-RESISTOR-1206"))
    )
    (comp (ref "R137")
      (value "470")
      (footprint "eagle-import:1206")
      (libsource (lib "eagle-import") (part "PASSIF-RESISTOR-1206"))
    )
    (comp (ref "R138")
      (value "470")
      (footprint "eagle-import:1206")
      (libsource (lib "eagle-import") (part "PASSIF-RESISTOR-1206"))
    )
    (comp (ref "R139")
      (value "470")
      (footprint "eagle-import:1206")
      (libsource (lib "eagle-import") (part "PASSIF-RESISTOR-1206"))
    )
    (comp (ref "R140")
      (value "470")
      (footprint "eagle-import:1206")
      (libsource (lib "eagle-import") (part "PASSIF-RESISTOR-1206"))
    )
    (comp (ref "R141")
      (value "470")
      (footprint "eagle-import:1206")
      (libsource (lib "eagle-import") (part "PASSIF-RESISTOR-1206"))
    )
    (comp (ref "R142")
      (value "470")
      (footprint "eagle-import:1206")
      (libsource (lib "eagle-import") (part "PASSIF-RESISTOR-1206"))
    )
    (comp (ref "R143")
      (value "470")
      (footprint "eagle-import:1206")
      (libsource (lib "eagle-import") (part "PASSIF-RESISTOR-1206"))
    )
    (comp (ref "R144")
      (value "470")
      (footprint "eagle-import:1206")
      (libsource (lib "eagle-import") (part "PASSIF-RESISTOR-1206"))
    )
    (comp (ref "R145")
      (value "470")
      (footprint "eagle-import:1206")
      (libsource (lib "eagle-import") (part "PASSIF-RESISTOR-1206"))
    )
    (comp (ref "R146")
      (value "100")
      (footprint "eagle-import:1206")
      (libsource (lib "eagle-import") (part "PASSIF-RESISTOR-1206"))
    )
    (comp (ref "R147")
      (value "100")
      (footprint "eagle-import:1206")
      (libsource (lib "eagle-import") (part "PASSIF-RESISTOR-1206"))
    )
    (comp (ref "R148")
      (value "100")
      (footprint "eagle-import:1206")
      (libsource (lib "eagle-import") (part "PASSIF-RESISTOR-1206"))
    )
    (comp (ref "R149")
      (value "10k")
      (footprint "eagle-import:1206")
      (libsource (lib "eagle-import") (part "PASSIF-RESISTOR-1206"))
    )
    (comp (ref "R150")
      (value "100")
      (footprint "eagle-import:1206")
      (libsource (lib "eagle-import") (part "PASSIF-RESISTOR-1206"))
    )
    (comp (ref "R151")
      (value "100")
      (footprint "eagle-import:1206")
      (libsource (lib "eagle-import") (part "PASSIF-RESISTOR-1206"))
    )
    (comp (ref "R152")
      (value "100")
      (footprint "eagle-import:1206")
      (libsource (lib "eagle-import") (part "PASSIF-RESISTOR-1206"))
    )
    (comp (ref "R153")
      (value "10k")
      (footprint "eagle-import:1206")
      (libsource (lib "eagle-import") (part "PASSIF-RESISTOR-1206"))
    )
    (comp (ref "R154")
      (value "100")
      (footprint "eagle-import:1206")
      (libsource (lib "eagle-import") (part "PASSIF-RESISTOR-1206"))
    )
    (comp (ref "R155")
      (value "100")
      (footprint "eagle-import:1206")
      (libsource (lib "eagle-import") (part "PASSIF-RESISTOR-1206"))
    )
    (comp (ref "R156")
      (value "100")
      (footprint "eagle-import:1206")
      (libsource (lib "eagle-import") (part "PASSIF-RESISTOR-1206"))
    )
    (comp (ref "R157")
      (value "10k")
      (footprint "eagle-import:1206")
      (libsource (lib "eagle-import") (part "PASSIF-RESISTOR-1206"))
    )
    (comp (ref "R158")
      (value "100")
      (footprint "eagle-import:1206")
      (libsource (lib "eagle-import") (part "PASSIF-RESISTOR-1206"))
    )
    (comp (ref "R159")
      (value "100")
      (footprint "eagle-import:1206")
      (libsource (lib "eagle-import") (part "PASSIF-RESISTOR-1206"))
    )
    (comp (ref "R160")
      (value "100")
      (footprint "eagle-import:1206")
      (libsource (lib "eagle-import") (part "PASSIF-RESISTOR-1206"))
    )
    (comp (ref "R161")
      (value "10k")
      (footprint "eagle-import:1206")
      (libsource (lib "eagle-import") (part "PASSIF-RESISTOR-1206"))
    )
    (comp (ref "R162")
      (value "470")
      (footprint "eagle-import:1206")
      (libsource (lib "eagle-import") (part "PASSIF-RESISTOR-1206"))
    )
    (comp (ref "R163")
      (value "470")
      (footprint "eagle-import:1206")
      (libsource (lib "eagle-import") (part "PASSIF-RESISTOR-1206"))
    )
    (comp (ref "R164")
      (value "470")
      (footprint "eagle-import:1206")
      (libsource (lib "eagle-import") (part "PASSIF-RESISTOR-1206"))
    )
    (comp (ref "R165")
      (value "470")
      (footprint "eagle-import:1206")
      (libsource (lib "eagle-import") (part "PASSIF-RESISTOR-1206"))
    )
    (comp (ref "R166")
      (value "470")
      (footprint "eagle-import:1206")
      (libsource (lib "eagle-import") (part "PASSIF-RESISTOR-1206"))
    )
    (comp (ref "R167")
      (value "470")
      (footprint "eagle-import:1206")
      (libsource (lib "eagle-import") (part "PASSIF-RESISTOR-1206"))
    )
    (comp (ref "R168")
      (value "470")
      (footprint "eagle-import:1206")
      (libsource (lib "eagle-import") (part "PASSIF-RESISTOR-1206"))
    )
    (comp (ref "R169")
      (value "470")
      (footprint "eagle-import:1206")
      (libsource (lib "eagle-import") (part "PASSIF-RESISTOR-1206"))
    )
    (comp (ref "R170")
      (value "100")
      (footprint "eagle-import:1206")
      (libsource (lib "eagle-import") (part "PASSIF-RESISTOR-1206"))
    )
    (comp (ref "R171")
      (value "100")
      (footprint "eagle-import:1206")
      (libsource (lib "eagle-import") (part "PASSIF-RESISTOR-1206"))
    )
    (comp (ref "R172")
      (value "100")
      (footprint "eagle-import:1206")
      (libsource (lib "eagle-import") (part "PASSIF-RESISTOR-1206"))
    )
    (comp (ref "R173")
      (value "10k")
      (footprint "eagle-import:1206")
      (libsource (lib "eagle-import") (part "PASSIF-RESISTOR-1206"))
    )
    (comp (ref "R174")
      (value "100")
      (footprint "eagle-import:1206")
      (libsource (lib "eagle-import") (part "PASSIF-RESISTOR-1206"))
    )
    (comp (ref "R175")
      (value "100")
      (footprint "eagle-import:1206")
      (libsource (lib "eagle-import") (part "PASSIF-RESISTOR-1206"))
    )
    (comp (ref "R176")
      (value "100")
      (footprint "eagle-import:1206")
      (libsource (lib "eagle-import") (part "PASSIF-RESISTOR-1206"))
    )
    (comp (ref "R177")
      (value "10k")
      (footprint "eagle-import:1206")
      (libsource (lib "eagle-import") (part "PASSIF-RESISTOR-1206"))
    )
    (comp (ref "R178")
      (value "100")
      (footprint "eagle-import:1206")
      (libsource (lib "eagle-import") (part "PASSIF-RESISTOR-1206"))
    )
    (comp (ref "R179")
      (value "100")
      (footprint "eagle-import:1206")
      (libsource (lib "eagle-import") (part "PASSIF-RESISTOR-1206"))
    )
    (comp (ref "R180")
      (value "100")
      (footprint "eagle-import:1206")
      (libsource (lib "eagle-import") (part "PASSIF-RESISTOR-1206"))
    )
    (comp (ref "R181")
      (value "100")
      (footprint "eagle-import:1206")
      (libsource (lib "eagle-import") (part "PASSIF-RESISTOR-1206"))
    )
    (comp (ref "R182")
      (value "100")
      (footprint "eagle-import:1206")
      (libsource (lib "eagle-import") (part "PASSIF-RESISTOR-1206"))
    )
    (comp (ref "R183")
      (value "100")
      (footprint "eagle-import:1206")
      (libsource (lib "eagle-import") (part "PASSIF-RESISTOR-1206"))
    )
    (comp (ref "R184")
      (value "470")
      (footprint "eagle-import:1206")
      (libsource (lib "eagle-import") (part "PASSIF-RESISTOR-1206"))
    )
    (comp (ref "R185")
      (value "470")
      (footprint "eagle-import:1206")
      (libsource (lib "eagle-import") (part "PASSIF-RESISTOR-1206"))
    )
    (comp (ref "R186")
      (value "470")
      (footprint "eagle-import:1206")
      (libsource (lib "eagle-import") (part "PASSIF-RESISTOR-1206"))
    )
    (comp (ref "R187")
      (value "470")
      (footprint "eagle-import:1206")
      (libsource (lib "eagle-import") (part "PASSIF-RESISTOR-1206"))
    )
    (comp (ref "R188")
      (value "470")
      (footprint "eagle-import:1206")
      (libsource (lib "eagle-import") (part "PASSIF-RESISTOR-1206"))
    )
    (comp (ref "R189")
      (value "470")
      (footprint "eagle-import:1206")
      (libsource (lib "eagle-import") (part "PASSIF-RESISTOR-1206"))
    )
    (comp (ref "R190")
      (value "470")
      (footprint "eagle-import:1206")
      (libsource (lib "eagle-import") (part "PASSIF-RESISTOR-1206"))
    )
    (comp (ref "R191")
      (value "470")
      (footprint "eagle-import:1206")
      (libsource (lib "eagle-import") (part "PASSIF-RESISTOR-1206"))
    )
    (comp (ref "R192")
      (value "470")
      (footprint "eagle-import:1206")
      (libsource (lib "eagle-import") (part "PASSIF-RESISTOR-1206"))
    )
    (comp (ref "R193")
      (value "470")
      (footprint "eagle-import:1206")
      (libsource (lib "eagle-import") (part "PASSIF-RESISTOR-1206"))
    )
    (comp (ref "R194")
      (value "470")
      (footprint "eagle-import:1206")
      (libsource (lib "eagle-import") (part "PASSIF-RESISTOR-1206"))
    )
    (comp (ref "R195")
      (value "470")
      (footprint "eagle-import:1206")
      (libsource (lib "eagle-import") (part "PASSIF-RESISTOR-1206"))
    )
    (comp (ref "R196")
      (value "100")
      (footprint "eagle-import:1206")
      (libsource (lib "eagle-import") (part "PASSIF-RESISTOR-1206"))
    )
    (comp (ref "R197")
      (value "100")
      (footprint "eagle-import:1206")
      (libsource (lib "eagle-import") (part "PASSIF-RESISTOR-1206"))
    )
    (comp (ref "R198")
      (value "100")
      (footprint "eagle-import:1206")
      (libsource (lib "eagle-import") (part "PASSIF-RESISTOR-1206"))
    )
    (comp (ref "R199")
      (value "10k")
      (footprint "eagle-import:1206")
      (libsource (lib "eagle-import") (part "PASSIF-RESISTOR-1206"))
    )
    (comp (ref "R200")
      (value "100")
      (footprint "eagle-import:1206")
      (libsource (lib "eagle-import") (part "PASSIF-RESISTOR-1206"))
    )
    (comp (ref "R201")
      (value "100")
      (footprint "eagle-import:1206")
      (libsource (lib "eagle-import") (part "PASSIF-RESISTOR-1206"))
    )
    (comp (ref "R202")
      (value "100")
      (footprint "eagle-import:1206")
      (libsource (lib "eagle-import") (part "PASSIF-RESISTOR-1206"))
    )
    (comp (ref "R203")
      (value "10k")
      (footprint "eagle-import:1206")
      (libsource (lib "eagle-import") (part "PASSIF-RESISTOR-1206"))
    )
    (comp (ref "R204")
      (value "100")
      (footprint "eagle-import:1206")
      (libsource (lib "eagle-import") (part "PASSIF-RESISTOR-1206"))
    )
    (comp (ref "R205")
      (value "100")
      (footprint "eagle-import:1206")
      (libsource (lib "eagle-import") (part "PASSIF-RESISTOR-1206"))
    )
    (comp (ref "R206")
      (value "100")
      (footprint "eagle-import:1206")
      (libsource (lib "eagle-import") (part "PASSIF-RESISTOR-1206"))
    )
    (comp (ref "R207")
      (value "10k")
      (footprint "eagle-import:1206")
      (libsource (lib "eagle-import") (part "PASSIF-RESISTOR-1206"))
    )
    (comp (ref "R208")
      (value "100")
      (footprint "eagle-import:1206")
      (libsource (lib "eagle-import") (part "PASSIF-RESISTOR-1206"))
    )
    (comp (ref "R209")
      (value "100")
      (footprint "eagle-import:1206")
      (libsource (lib "eagle-import") (part "PASSIF-RESISTOR-1206"))
    )
    (comp (ref "R210")
      (value "100")
      (footprint "eagle-import:1206")
      (libsource (lib "eagle-import") (part "PASSIF-RESISTOR-1206"))
    )
    (comp (ref "R211")
      (value "10k")
      (footprint "eagle-import:1206")
      (libsource (lib "eagle-import") (part "PASSIF-RESISTOR-1206"))
    )
    (comp (ref "S14")
      (value "ENCODER-RGB-SWITCH-NO_NUT")
      (footprint "eagle-import:ENCODER_LED_3")
      (libsource (lib "eagle-import") (part "ENCODER-RGB-SWITCH-NO_NUT"))
    )
    (comp (ref "S15")
      (value "ENCODER-RGB-SWITCH-NO_NUT")
      (footprint "eagle-import:ENCODER_LED_3")
      (libsource (lib "eagle-import") (part "ENCODER-RGB-SWITCH-NO_NUT"))
    )
    (comp (ref "S16")
      (value "ENCODER-RGB-SWITCH-NO_NUT")
      (footprint "eagle-import:ENCODER_LED_3")
      (libsource (lib "eagle-import") (part "ENCODER-RGB-SWITCH-NO_NUT"))
    )
    (comp (ref "S17")
      (value "ENCODER-RGB-SWITCH-NO_NUT")
      (footprint "eagle-import:ENCODER_LED_3")
      (libsource (lib "eagle-import") (part "ENCODER-RGB-SWITCH-NO_NUT"))
    )
    (comp (ref "S18")
      (value "ENCODER-RGB-SWITCH-NO_NUT")
      (footprint "eagle-import:ENCODER_LED_3")
      (libsource (lib "eagle-import") (part "ENCODER-RGB-SWITCH-NO_NUT"))
    )
    (comp (ref "S19")
      (value "ENCODER-RGB-SWITCH-NO_NUT")
      (footprint "eagle-import:ENCODER_LED_3")
      (libsource (lib "eagle-import") (part "ENCODER-RGB-SWITCH-NO_NUT"))
    )
    (comp (ref "S20")
      (value "ENCODER-RGB-SWITCH-NO_NUT")
      (footprint "eagle-import:ENCODER_LED_3")
      (libsource (lib "eagle-import") (part "ENCODER-RGB-SWITCH-NO_NUT"))
    )
    (comp (ref "S21")
      (value "ENCODER-RGB-SWITCH-NO_NUT")
      (footprint "eagle-import:ENCODER_LED_3")
      (libsource (lib "eagle-import") (part "ENCODER-RGB-SWITCH-NO_NUT"))
    )
    (comp (ref "S22")
      (value "ENCODER-RGB-SWITCH-NO_NUT")
      (footprint "eagle-import:ENCODER_LED_3")
      (libsource (lib "eagle-import") (part "ENCODER-RGB-SWITCH-NO_NUT"))
    )
    (comp (ref "S23")
      (value "ENCODER-RGB-SWITCH-NO_NUT")
      (footprint "eagle-import:ENCODER_LED_3")
      (libsource (lib "eagle-import") (part "ENCODER-RGB-SWITCH-NO_NUT"))
    )
    (comp (ref "SW9")
      (value "B3F-1000")
      (footprint "eagle-import:B3F-1000")
      (fields
        (field (name "DIGI_KEY_PART_NUMBER") "SW400-ND")
        (field (name "MANUFACTURER") "Omron Electronics Inc-EMC Div")
        (field (name "CREATED_BY") "PCBLayout.com")
      )
      (libsource (lib "eagle-import") (part "B3F-1000"))
    )
    (comp (ref "SW10")
      (value "B3F-1000")
      (footprint "eagle-import:B3F-1000")
      (fields
        (field (name "DIGI_KEY_PART_NUMBER") "SW400-ND")
        (field (name "MANUFACTURER") "Omron Electronics Inc-EMC Div")
        (field (name "CREATED_BY") "PCBLayout.com")
      )
      (libsource (lib "eagle-import") (part "B3F-1000"))
    )
    (comp (ref "C49")
      (value "10u")
      (footprint "eagle-import:CPOL2917")
      (libsource (lib "eagle-import") (part "PASSIF-CPOL-US2917"))
    )
    (comp (ref "C50")
      (value "100n")
      (footprint "eagle-import:0805-CAP")
      (libsource (lib "eagle-import") (part "PASSIF-CAP-0805"))
    )
    (comp (ref "C51")
      (value "10u")
      (footprint "eagle-import:CPOL2917")
      (libsource (lib "eagle-import") (part "PASSIF-CPOL-US2917"))
    )
    (comp (ref "C52")
      (value "10u")
      (footprint "eagle-import:CPOL2917")
      (libsource (lib "eagle-import") (part "PASSIF-CPOL-US2917"))
    )
    (comp (ref "C53")
      (value "10u")
      (footprint "eagle-import:CPOL2917")
      (libsource (lib "eagle-import") (part "PASSIF-CPOL-US2917"))
    )
    (comp (ref "C54")
      (value "10u")
      (footprint "eagle-import:CPOL2917")
      (libsource (lib "eagle-import") (part "PASSIF-CPOL-US2917"))
    )
    (comp (ref "C55")
      (value "10n")
      (footprint "eagle-import:0805-CAP")
      (libsource (lib "eagle-import") (part "PASSIF-CAP-0805"))
    )
    (comp (ref "C56")
      (value "10n")
      (footprint "eagle-import:0805-CAP")
      (libsource (lib "eagle-import") (part "PASSIF-CAP-0805"))
    )
    (comp (ref "C57")
      (value "10n")
      (footprint "eagle-import:0805-CAP")
      (libsource (lib "eagle-import") (part "PASSIF-CAP-0805"))
    )
    (comp (ref "C58")
      (value "10n")
      (footprint "eagle-import:0805-CAP")
      (libsource (lib "eagle-import") (part "PASSIF-CAP-0805"))
    )
    (comp (ref "C59")
      (value "10n")
      (footprint "eagle-import:0805-CAP")
      (libsource (lib "eagle-import") (part "PASSIF-CAP-0805"))
    )
    (comp (ref "C60")
      (value "10n")
      (footprint "eagle-import:0805-CAP")
      (libsource (lib "eagle-import") (part "PASSIF-CAP-0805"))
    )
    (comp (ref "C61")
      (value "10n")
      (footprint "eagle-import:0805-CAP")
      (libsource (lib "eagle-import") (part "PASSIF-CAP-0805"))
    )
    (comp (ref "C62")
      (value "10n")
      (footprint "eagle-import:0805-CAP")
      (libsource (lib "eagle-import") (part "PASSIF-CAP-0805"))
    )
    (comp (ref "C63")
      (value "100n")
      (footprint "eagle-import:0805-CAP")
      (libsource (lib "eagle-import") (part "PASSIF-CAP-0805"))
    )
    (comp (ref "C64")
      (value "100n")
      (footprint "eagle-import:0805-CAP")
      (libsource (lib "eagle-import") (part "PASSIF-CAP-0805"))
    )
    (comp (ref "C65")
      (value "100n")
      (footprint "eagle-import:0805-CAP")
      (libsource (lib "eagle-import") (part "PASSIF-CAP-0805"))
    )
    (comp (ref "C66")
      (value "100n")
      (footprint "eagle-import:0805-CAP")
      (libsource (lib "eagle-import") (part "PASSIF-CAP-0805"))
    )
    (comp (ref "C67")
      (value "10n")
      (footprint "eagle-import:0805-CAP")
      (libsource (lib "eagle-import") (part "PASSIF-CAP-0805"))
    )
    (comp (ref "C68")
      (value "10n")
      (footprint "eagle-import:0805-CAP")
      (libsource (lib "eagle-import") (part "PASSIF-CAP-0805"))
    )
    (comp (ref "C69")
      (value "10n")
      (footprint "eagle-import:0805-CAP")
      (libsource (lib "eagle-import") (part "PASSIF-CAP-0805"))
    )
    (comp (ref "C70")
      (value "10n")
      (footprint "eagle-import:0805-CAP")
      (libsource (lib "eagle-import") (part "PASSIF-CAP-0805"))
    )
    (comp (ref "C71")
      (value "10n")
      (footprint "eagle-import:0805-CAP")
      (libsource (lib "eagle-import") (part "PASSIF-CAP-0805"))
    )
    (comp (ref "C72")
      (value "10n")
      (footprint "eagle-import:0805-CAP")
      (libsource (lib "eagle-import") (part "PASSIF-CAP-0805"))
    )
    (comp (ref "C73")
      (value "10n")
      (footprint "eagle-import:0805-CAP")
      (libsource (lib "eagle-import") (part "PASSIF-CAP-0805"))
    )
    (comp (ref "C74")
      (value "10n")
      (footprint "eagle-import:0805-CAP")
      (libsource (lib "eagle-import") (part "PASSIF-CAP-0805"))
    )
    (comp (ref "C75")
      (value "100n")
      (footprint "eagle-import:0805-CAP")
      (libsource (lib "eagle-import") (part "PASSIF-CAP-0805"))
    )
    (comp (ref "C76")
      (value "100n")
      (footprint "eagle-import:0805-CAP")
      (libsource (lib "eagle-import") (part "PASSIF-CAP-0805"))
    )
    (comp (ref "C77")
      (value "100n")
      (footprint "eagle-import:0805-CAP")
      (libsource (lib "eagle-import") (part "PASSIF-CAP-0805"))
    )
    (comp (ref "C78")
      (value "100n")
      (footprint "eagle-import:0805-CAP")
      (libsource (lib "eagle-import") (part "PASSIF-CAP-0805"))
    )
    (comp (ref "C79")
      (value "10u")
      (footprint "eagle-import:CPOL2917")
      (libsource (lib "eagle-import") (part "PASSIF-CPOL-US2917"))
    )
    (comp (ref "C80")
      (value "10u")
      (footprint "eagle-import:CPOL2917")
      (libsource (lib "eagle-import") (part "PASSIF-CPOL-US2917"))
    )
    (comp (ref "C81")
      (value "10u")
      (footprint "eagle-import:CPOL2917")
      (libsource (lib "eagle-import") (part "PASSIF-CPOL-US2917"))
    )
    (comp (ref "C82")
      (value "10u")
      (footprint "eagle-import:CPOL2917")
      (libsource (lib "eagle-import") (part "PASSIF-CPOL-US2917"))
    )
    (comp (ref "D5")
      (value "CZXR-80RGB03-A")
      (footprint "eagle-import:LED4-2.0-D8.0MM")
      (libsource (lib "eagle-import") (part "DIP-LED-RGB-COMMON-ANODE(4P-D8MM)"))
    )
    (comp (ref "D6")
      (value "CZXR-80RGB03-A")
      (footprint "eagle-import:LED4-2.0-D8.0MM")
      (libsource (lib "eagle-import") (part "DIP-LED-RGB-COMMON-ANODE(4P-D8MM)"))
    )
    (comp (ref "D7")
      (value "CZXR-80RGB03-A")
      (footprint "eagle-import:LED4-2.0-D8.0MM")
      (libsource (lib "eagle-import") (part "DIP-LED-RGB-COMMON-ANODE(4P-D8MM)"))
    )
    (comp (ref "D8")
      (value "CZXR-80RGB03-A")
      (footprint "eagle-import:LED4-2.0-D8.0MM")
      (libsource (lib "eagle-import") (part "DIP-LED-RGB-COMMON-ANODE(4P-D8MM)"))
    )
    (comp (ref "IC14")
      (value "NEOPIXEL-TLC59731DR")
      (footprint "eagle-import:SOIC127P600X175-8N")
      (fields
        (field (name "ARROW_PART_NUMBER") "TLC59731DR")
        (field (name "MOUSER_PART_NUMBER") "595-TLC59731DR")
      )
      (libsource (lib "eagle-import") (part "NEOPIXEL-TLC59731DR"))
    )
    (comp (ref "IC15")
      (value "NEOPIXEL-TLC59731DR")
      (footprint "eagle-import:SOIC127P600X175-8N")
      (fields
        (field (name "ARROW_PART_NUMBER") "TLC59731DR")
        (field (name "MOUSER_PART_NUMBER") "595-TLC59731DR")
      )
      (libsource (lib "eagle-import") (part "NEOPIXEL-TLC59731DR"))
    )
    (comp (ref "IC16")
      (value "NEOPIXEL-TLC59731DR")
      (footprint "eagle-import:SOIC127P600X175-8N")
      (fields
        (field (name "ARROW_PART_NUMBER") "TLC59731DR")
        (field (name "MOUSER_PART_NUMBER") "595-TLC59731DR")
      )
      (libsource (lib "eagle-import") (part "NEOPIXEL-TLC59731DR"))
    )
    (comp (ref "IC17")
      (value "NEOPIXEL-TLC59731DR")
      (footprint "eagle-import:SOIC127P600X175-8N")
      (fields
        (field (name "ARROW_PART_NUMBER") "TLC59731DR")
        (field (name "MOUSER_PART_NUMBER") "595-TLC59731DR")
      )
      (libsource (lib "eagle-import") (part "NEOPIXEL-TLC59731DR"))
    )
    (comp (ref "IC18")
      (value "NEOPIXEL-TLC59731DR")
      (footprint "eagle-import:SOIC127P600X175-8N")
      (fields
        (field (name "ARROW_PART_NUMBER") "TLC59731DR")
        (field (name "MOUSER_PART_NUMBER") "595-TLC59731DR")
      )
      (libsource (lib "eagle-import") (part "NEOPIXEL-TLC59731DR"))
    )
    (comp (ref "IC19")
      (value "NEOPIXEL-TLC59731DR")
      (footprint "eagle-import:SOIC127P600X175-8N")
      (fields
        (field (name "ARROW_PART_NUMBER") "TLC59731DR")
        (field (name "MOUSER_PART_NUMBER") "595-TLC59731DR")
      )
      (libsource (lib "eagle-import") (part "NEOPIXEL-TLC59731DR"))
    )
    (comp (ref "IC20")
      (value "NEOPIXEL-TLC59731DR")
      (footprint "eagle-import:SOIC127P600X175-8N")
      (fields
        (field (name "ARROW_PART_NUMBER") "TLC59731DR")
        (field (name "MOUSER_PART_NUMBER") "595-TLC59731DR")
      )
      (libsource (lib "eagle-import") (part "NEOPIXEL-TLC59731DR"))
    )
    (comp (ref "IC21")
      (value "NEOPIXEL-TLC59731DR")
      (footprint "eagle-import:SOIC127P600X175-8N")
      (fields
        (field (name "ARROW_PART_NUMBER") "TLC59731DR")
        (field (name "MOUSER_PART_NUMBER") "595-TLC59731DR")
      )
      (libsource (lib "eagle-import") (part "NEOPIXEL-TLC59731DR"))
    )
    (comp (ref "MCP_010")
      (value "MCP23017")
      (footprint "eagle-import:SOIC-28")
      (libsource (lib "eagle-import") (part "MCP23017"))
    )
    (comp (ref "R84")
      (value "1k")
      (footprint "eagle-import:R0805")
      (libsource (lib "eagle-import") (part "R-US_R0805"))
    )
    (comp (ref "R85")
      (value "1k")
      (footprint "eagle-import:R0805")
      (libsource (lib "eagle-import") (part "R-US_R0805"))
    )
    (comp (ref "R86")
      (value "470")
      (footprint "eagle-import:1206")
      (libsource (lib "eagle-import") (part "PASSIF-RESISTOR-1206"))
    )
    (comp (ref "R87")
      (value "470")
      (footprint "eagle-import:1206")
      (libsource (lib "eagle-import") (part "PASSIF-RESISTOR-1206"))
    )
    (comp (ref "R88")
      (value "470")
      (footprint "eagle-import:1206")
      (libsource (lib "eagle-import") (part "PASSIF-RESISTOR-1206"))
    )
    (comp (ref "R89")
      (value "470")
      (footprint "eagle-import:1206")
      (libsource (lib "eagle-import") (part "PASSIF-RESISTOR-1206"))
    )
    (comp (ref "R90")
      (value "470")
      (footprint "eagle-import:1206")
      (libsource (lib "eagle-import") (part "PASSIF-RESISTOR-1206"))
    )
    (comp (ref "R91")
      (value "470")
      (footprint "eagle-import:1206")
      (libsource (lib "eagle-import") (part "PASSIF-RESISTOR-1206"))
    )
    (comp (ref "R92")
      (value "470")
      (footprint "eagle-import:1206")
      (libsource (lib "eagle-import") (part "PASSIF-RESISTOR-1206"))
    )
    (comp (ref "R93")
      (value "470")
      (footprint "eagle-import:1206")
      (libsource (lib "eagle-import") (part "PASSIF-RESISTOR-1206"))
    )
    (comp (ref "R94")
      (value "470")
      (footprint "eagle-import:1206")
      (libsource (lib "eagle-import") (part "PASSIF-RESISTOR-1206"))
    )
    (comp (ref "R95")
      (value "470")
      (footprint "eagle-import:1206")
      (libsource (lib "eagle-import") (part "PASSIF-RESISTOR-1206"))
    )
    (comp (ref "R96")
      (value "470")
      (footprint "eagle-import:1206")
      (libsource (lib "eagle-import") (part "PASSIF-RESISTOR-1206"))
    )
    (comp (ref "R97")
      (value "470")
      (footprint "eagle-import:1206")
      (libsource (lib "eagle-import") (part "PASSIF-RESISTOR-1206"))
    )
    (comp (ref "R98")
      (value "100")
      (footprint "eagle-import:1206")
      (libsource (lib "eagle-import") (part "PASSIF-RESISTOR-1206"))
    )
    (comp (ref "R99")
      (value "100")
      (footprint "eagle-import:1206")
      (libsource (lib "eagle-import") (part "PASSIF-RESISTOR-1206"))
    )
    (comp (ref "R100")
      (value "100")
      (footprint "eagle-import:1206")
      (libsource (lib "eagle-import") (part "PASSIF-RESISTOR-1206"))
    )
    (comp (ref "R101")
      (value "10k")
      (footprint "eagle-import:1206")
      (libsource (lib "eagle-import") (part "PASSIF-RESISTOR-1206"))
    )
    (comp (ref "R102")
      (value "100")
      (footprint "eagle-import:1206")
      (libsource (lib "eagle-import") (part "PASSIF-RESISTOR-1206"))
    )
    (comp (ref "R103")
      (value "100")
      (footprint "eagle-import:1206")
      (libsource (lib "eagle-import") (part "PASSIF-RESISTOR-1206"))
    )
    (comp (ref "R104")
      (value "100")
      (footprint "eagle-import:1206")
      (libsource (lib "eagle-import") (part "PASSIF-RESISTOR-1206"))
    )
    (comp (ref "R105")
      (value "10k")
      (footprint "eagle-import:1206")
      (libsource (lib "eagle-import") (part "PASSIF-RESISTOR-1206"))
    )
    (comp (ref "R106")
      (value "100")
      (footprint "eagle-import:1206")
      (libsource (lib "eagle-import") (part "PASSIF-RESISTOR-1206"))
    )
    (comp (ref "R107")
      (value "100")
      (footprint "eagle-import:1206")
      (libsource (lib "eagle-import") (part "PASSIF-RESISTOR-1206"))
    )
    (comp (ref "R108")
      (value "100")
      (footprint "eagle-import:1206")
      (libsource (lib "eagle-import") (part "PASSIF-RESISTOR-1206"))
    )
    (comp (ref "R109")
      (value "10k")
      (footprint "eagle-import:1206")
      (libsource (lib "eagle-import") (part "PASSIF-RESISTOR-1206"))
    )
    (comp (ref "R110")
      (value "100")
      (footprint "eagle-import:1206")
      (libsource (lib "eagle-import") (part "PASSIF-RESISTOR-1206"))
    )
    (comp (ref "R111")
      (value "100")
      (footprint "eagle-import:1206")
      (libsource (lib "eagle-import") (part "PASSIF-RESISTOR-1206"))
    )
    (comp (ref "R112")
      (value "100")
      (footprint "eagle-import:1206")
      (libsource (lib "eagle-import") (part "PASSIF-RESISTOR-1206"))
    )
    (comp (ref "R113")
      (value "10k")
      (footprint "eagle-import:1206")
      (libsource (lib "eagle-import") (part "PASSIF-RESISTOR-1206"))
    )
    (comp (ref "R114")
      (value "470")
      (footprint "eagle-import:1206")
      (libsource (lib "eagle-import") (part "PASSIF-RESISTOR-1206"))
    )
    (comp (ref "R115")
      (value "470")
      (footprint "eagle-import:1206")
      (libsource (lib "eagle-import") (part "PASSIF-RESISTOR-1206"))
    )
    (comp (ref "R116")
      (value "470")
      (footprint "eagle-import:1206")
      (libsource (lib "eagle-import") (part "PASSIF-RESISTOR-1206"))
    )
    (comp (ref "R117")
      (value "470")
      (footprint "eagle-import:1206")
      (libsource (lib "eagle-import") (part "PASSIF-RESISTOR-1206"))
    )
    (comp (ref "R118")
      (value "100")
      (footprint "eagle-import:1206")
      (libsource (lib "eagle-import") (part "PASSIF-RESISTOR-1206"))
    )
    (comp (ref "R119")
      (value "100")
      (footprint "eagle-import:1206")
      (libsource (lib "eagle-import") (part "PASSIF-RESISTOR-1206"))
    )
    (comp (ref "R120")
      (value "100")
      (footprint "eagle-import:1206")
      (libsource (lib "eagle-import") (part "PASSIF-RESISTOR-1206"))
    )
    (comp (ref "R121")
      (value "100")
      (footprint "eagle-import:1206")
      (libsource (lib "eagle-import") (part "PASSIF-RESISTOR-1206"))
    )
    (comp (ref "R122")
      (value "100")
      (footprint "eagle-import:1206")
      (libsource (lib "eagle-import") (part "PASSIF-RESISTOR-1206"))
    )
    (comp (ref "R123")
      (value "100")
      (footprint "eagle-import:1206")
      (libsource (lib "eagle-import") (part "PASSIF-RESISTOR-1206"))
    )
    (comp (ref "R124")
      (value "100")
      (footprint "eagle-import:1206")
      (libsource (lib "eagle-import") (part "PASSIF-RESISTOR-1206"))
    )
    (comp (ref "R125")
      (value "100")
      (footprint "eagle-import:1206")
      (libsource (lib "eagle-import") (part "PASSIF-RESISTOR-1206"))
    )
    (comp (ref "R126")
      (value "100")
      (footprint "eagle-import:1206")
      (libsource (lib "eagle-import") (part "PASSIF-RESISTOR-1206"))
    )
    (comp (ref "R127")
      (value "100")
      (footprint "eagle-import:1206")
      (libsource (lib "eagle-import") (part "PASSIF-RESISTOR-1206"))
    )
    (comp (ref "R128")
      (value "100")
      (footprint "eagle-import:1206")
      (libsource (lib "eagle-import") (part "PASSIF-RESISTOR-1206"))
    )
    (comp (ref "R129")
      (value "100")
      (footprint "eagle-import:1206")
      (libsource (lib "eagle-import") (part "PASSIF-RESISTOR-1206"))
    )
    (comp (ref "S10")
      (value "ENCODER-RGB-SWITCH-NO_NUT")
      (footprint "eagle-import:ENCODER_LED_3")
      (libsource (lib "eagle-import") (part "ENCODER-RGB-SWITCH-NO_NUT"))
    )
    (comp (ref "S11")
      (value "ENCODER-RGB-SWITCH-NO_NUT")
      (footprint "eagle-import:ENCODER_LED_3")
      (libsource (lib "eagle-import") (part "ENCODER-RGB-SWITCH-NO_NUT"))
    )
    (comp (ref "S12")
      (value "ENCODER-RGB-SWITCH-NO_NUT")
      (footprint "eagle-import:ENCODER_LED_3")
      (libsource (lib "eagle-import") (part "ENCODER-RGB-SWITCH-NO_NUT"))
    )
    (comp (ref "S13")
      (value "ENCODER-RGB-SWITCH-NO_NUT")
      (footprint "eagle-import:ENCODER_LED_3")
      (libsource (lib "eagle-import") (part "ENCODER-RGB-SWITCH-NO_NUT"))
    )
    (comp (ref "SW5")
      (value "B3F-1000")
      (footprint "eagle-import:B3F-1000")
      (fields
        (field (name "DIGI_KEY_PART_NUMBER") "SW400-ND")
        (field (name "MANUFACTURER") "Omron Electronics Inc-EMC Div")
        (field (name "CREATED_BY") "PCBLayout.com")
      )
      (libsource (lib "eagle-import") (part "B3F-1000"))
    )
    (comp (ref "SW6")
      (value "B3F-1000")
      (footprint "eagle-import:B3F-1000")
      (fields
        (field (name "DIGI_KEY_PART_NUMBER") "SW400-ND")
        (field (name "MANUFACTURER") "Omron Electronics Inc-EMC Div")
        (field (name "CREATED_BY") "PCBLayout.com")
      )
      (libsource (lib "eagle-import") (part "B3F-1000"))
    )
    (comp (ref "SW7")
      (value "B3F-1000")
      (footprint "eagle-import:B3F-1000")
      (fields
        (field (name "DIGI_KEY_PART_NUMBER") "SW400-ND")
        (field (name "MANUFACTURER") "Omron Electronics Inc-EMC Div")
        (field (name "CREATED_BY") "PCBLayout.com")
      )
      (libsource (lib "eagle-import") (part "B3F-1000"))
    )
    (comp (ref "SW8")
      (value "B3F-1000")
      (footprint "eagle-import:B3F-1000")
      (fields
        (field (name "DIGI_KEY_PART_NUMBER") "SW400-ND")
        (field (name "MANUFACTURER") "Omron Electronics Inc-EMC Div")
        (field (name "CREATED_BY") "PCBLayout.com")
      )
      (libsource (lib "eagle-import") (part "B3F-1000"))
    )
    (comp (ref "C1")
      (value "100n")
      (footprint "eagle-import:0805-CAP")
      (libsource (lib "eagle-import") (part "PASSIF-CAP-0805"))
    )
    (comp (ref "C2")
      (value "10u")
      (footprint "eagle-import:CPOL2917")
      (libsource (lib "eagle-import") (part "PASSIF-CPOL-US2917"))
    )
    (comp (ref "C3")
      (value "10u")
      (footprint "eagle-import:CPOL2917")
      (libsource (lib "eagle-import") (part "PASSIF-CPOL-US2917"))
    )
    (comp (ref "C4")
      (value "100n")
      (footprint "eagle-import:0805-CAP")
      (libsource (lib "eagle-import") (part "PASSIF-CAP-0805"))
    )
    (comp (ref "C5")
      (value "10n")
      (footprint "eagle-import:0805-CAP")
      (libsource (lib "eagle-import") (part "PASSIF-CAP-0805"))
    )
    (comp (ref "C6")
      (value "10n")
      (footprint "eagle-import:0805-CAP")
      (libsource (lib "eagle-import") (part "PASSIF-CAP-0805"))
    )
    (comp (ref "C7")
      (value "10n")
      (footprint "eagle-import:0805-CAP")
      (libsource (lib "eagle-import") (part "PASSIF-CAP-0805"))
    )
    (comp (ref "C8")
      (value "10n")
      (footprint "eagle-import:0805-CAP")
      (libsource (lib "eagle-import") (part "PASSIF-CAP-0805"))
    )
    (comp (ref "C9")
      (value "10n")
      (footprint "eagle-import:0805-CAP")
      (libsource (lib "eagle-import") (part "PASSIF-CAP-0805"))
    )
    (comp (ref "C10")
      (value "10n")
      (footprint "eagle-import:0805-CAP")
      (libsource (lib "eagle-import") (part "PASSIF-CAP-0805"))
    )
    (comp (ref "C11")
      (value "10n")
      (footprint "eagle-import:0805-CAP")
      (libsource (lib "eagle-import") (part "PASSIF-CAP-0805"))
    )
    (comp (ref "C12")
      (value "10n")
      (footprint "eagle-import:0805-CAP")
      (libsource (lib "eagle-import") (part "PASSIF-CAP-0805"))
    )
    (comp (ref "C13")
      (value "10n")
      (footprint "eagle-import:0805-CAP")
      (libsource (lib "eagle-import") (part "PASSIF-CAP-0805"))
    )
    (comp (ref "C14")
      (value "10n")
      (footprint "eagle-import:0805-CAP")
      (libsource (lib "eagle-import") (part "PASSIF-CAP-0805"))
    )
    (comp (ref "C15")
      (value "100n")
      (footprint "eagle-import:1206")
      (libsource (lib "eagle-import") (part "PASSIF-CAP-1206"))
    )
    (comp (ref "C16")
      (value "100n")
      (footprint "eagle-import:1206")
      (libsource (lib "eagle-import") (part "PASSIF-CAP-1206"))
    )
    (comp (ref "C17")
      (value "100n")
      (footprint "eagle-import:1206")
      (libsource (lib "eagle-import") (part "PASSIF-CAP-1206"))
    )
    (comp (ref "C18")
      (value "100n")
      (footprint "eagle-import:1206")
      (libsource (lib "eagle-import") (part "PASSIF-CAP-1206"))
    )
    (comp (ref "C19")
      (value "100n")
      (footprint "eagle-import:1206")
      (libsource (lib "eagle-import") (part "PASSIF-CAP-1206"))
    )
    (comp (ref "C20")
      (value "10n")
      (footprint "eagle-import:0805-CAP")
      (libsource (lib "eagle-import") (part "PASSIF-CAP-0805"))
    )
    (comp (ref "C21")
      (value "10n")
      (footprint "eagle-import:0805-CAP")
      (libsource (lib "eagle-import") (part "PASSIF-CAP-0805"))
    )
    (comp (ref "C22")
      (value "10n")
      (footprint "eagle-import:0805-CAP")
      (libsource (lib "eagle-import") (part "PASSIF-CAP-0805"))
    )
    (comp (ref "C23")
      (value "10n")
      (footprint "eagle-import:0805-CAP")
      (libsource (lib "eagle-import") (part "PASSIF-CAP-0805"))
    )
    (comp (ref "C24")
      (value "10n")
      (footprint "eagle-import:0805-CAP")
      (libsource (lib "eagle-import") (part "PASSIF-CAP-0805"))
    )
    (comp (ref "C25")
      (value "10n")
      (footprint "eagle-import:0805-CAP")
      (libsource (lib "eagle-import") (part "PASSIF-CAP-0805"))
    )
    (comp (ref "C26")
      (value "10n")
      (footprint "eagle-import:0805-CAP")
      (libsource (lib "eagle-import") (part "PASSIF-CAP-0805"))
    )
    (comp (ref "C27")
      (value "10n")
      (footprint "eagle-import:0805-CAP")
      (libsource (lib "eagle-import") (part "PASSIF-CAP-0805"))
    )
    (comp (ref "C28")
      (value "10n")
      (footprint "eagle-import:0805-CAP")
      (libsource (lib "eagle-import") (part "PASSIF-CAP-0805"))
    )
    (comp (ref "C29")
      (value "10n")
      (footprint "eagle-import:0805-CAP")
      (libsource (lib "eagle-import") (part "PASSIF-CAP-0805"))
    )
    (comp (ref "C30")
      (value "100n")
      (footprint "eagle-import:1206")
      (libsource (lib "eagle-import") (part "PASSIF-CAP-1206"))
    )
    (comp (ref "C31")
      (value "100n")
      (footprint "eagle-import:1206")
      (libsource (lib "eagle-import") (part "PASSIF-CAP-1206"))
    )
    (comp (ref "C32")
      (value "100n")
      (footprint "eagle-import:1206")
      (libsource (lib "eagle-import") (part "PASSIF-CAP-1206"))
    )
    (comp (ref "C33")
      (value "100n")
      (footprint "eagle-import:1206")
      (libsource (lib "eagle-import") (part "PASSIF-CAP-1206"))
    )
    (comp (ref "C34")
      (value "10n")
      (footprint "eagle-import:0805-CAP")
      (libsource (lib "eagle-import") (part "PASSIF-CAP-0805"))
    )
    (comp (ref "C35")
      (value "10n")
      (footprint "eagle-import:0805-CAP")
      (libsource (lib "eagle-import") (part "PASSIF-CAP-0805"))
    )
    (comp (ref "C36")
      (value "10n")
      (footprint "eagle-import:0805-CAP")
      (libsource (lib "eagle-import") (part "PASSIF-CAP-0805"))
    )
    (comp (ref "C37")
      (value "10n")
      (footprint "eagle-import:0805-CAP")
      (libsource (lib "eagle-import") (part "PASSIF-CAP-0805"))
    )
    (comp (ref "C38")
      (value "10n")
      (footprint "eagle-import:0805-CAP")
      (libsource (lib "eagle-import") (part "PASSIF-CAP-0805"))
    )
    (comp (ref "C39")
      (value "10n")
      (footprint "eagle-import:0805-CAP")
      (libsource (lib "eagle-import") (part "PASSIF-CAP-0805"))
    )
    (comp (ref "C40")
      (value "10n")
      (footprint "eagle-import:0805-CAP")
      (libsource (lib "eagle-import") (part "PASSIF-CAP-0805"))
    )
    (comp (ref "C41")
      (value "10n")
      (footprint "eagle-import:0805-CAP")
      (libsource (lib "eagle-import") (part "PASSIF-CAP-0805"))
    )
    (comp (ref "C42")
      (value "10n")
      (footprint "eagle-import:0805-CAP")
      (libsource (lib "eagle-import") (part "PASSIF-CAP-0805"))
    )
    (comp (ref "C43")
      (value "10n")
      (footprint "eagle-import:0805-CAP")
      (libsource (lib "eagle-import") (part "PASSIF-CAP-0805"))
    )
    (comp (ref "C44")
      (value "10n")
      (footprint "eagle-import:0805-CAP")
      (libsource (lib "eagle-import") (part "PASSIF-CAP-0805"))
    )
    (comp (ref "C45")
      (value "100n")
      (footprint "eagle-import:1206")
      (libsource (lib "eagle-import") (part "PASSIF-CAP-1206"))
    )
    (comp (ref "C46")
      (value "100n")
      (footprint "eagle-import:1206")
      (libsource (lib "eagle-import") (part "PASSIF-CAP-1206"))
    )
    (comp (ref "C47")
      (value "100n")
      (footprint "eagle-import:1206")
      (libsource (lib "eagle-import") (part "PASSIF-CAP-1206"))
    )
    (comp (ref "C48")
      (value "100n")
      (footprint "eagle-import:1206")
      (libsource (lib "eagle-import") (part "PASSIF-CAP-1206"))
    )
    (comp (ref "CON_NORTH_BRD")
      (value "MA10-2")
      (footprint "eagle-import:MA10-2")
      (libsource (lib "eagle-import") (part "MA10-2"))
    )
    (comp (ref "D1")
      (value "CZXR-80RGB03-A")
      (footprint "eagle-import:LED4-2.0-D8.0MM")
      (libsource (lib "eagle-import") (part "DIP-LED-RGB-COMMON-ANODE(4P-D8MM)"))
    )
    (comp (ref "D2")
      (value "CZXR-80RGB03-A")
      (footprint "eagle-import:LED4-2.0-D8.0MM")
      (libsource (lib "eagle-import") (part "DIP-LED-RGB-COMMON-ANODE(4P-D8MM)"))
    )
    (comp (ref "D3")
      (value "CZXR-80RGB03-A")
      (footprint "eagle-import:LED4-2.0-D8.0MM")
      (libsource (lib "eagle-import") (part "DIP-LED-RGB-COMMON-ANODE(4P-D8MM)"))
    )
    (comp (ref "D4")
      (value "CZXR-80RGB03-A")
      (footprint "eagle-import:LED4-2.0-D8.0MM")
      (libsource (lib "eagle-import") (part "DIP-LED-RGB-COMMON-ANODE(4P-D8MM)"))
    )
    (comp (ref "IC1")
      (value "NEOPIXEL-TLC59731DR")
      (footprint "eagle-import:SOIC127P600X175-8N")
      (fields
        (field (name "ARROW_PART_NUMBER") "TLC59731DR")
        (field (name "MOUSER_PART_NUMBER") "595-TLC59731DR")
      )
      (libsource (lib "eagle-import") (part "NEOPIXEL-TLC59731DR"))
    )
    (comp (ref "IC2")
      (value "NEOPIXEL-TLC59731DR")
      (footprint "eagle-import:SOIC127P600X175-8N")
      (fields
        (field (name "ARROW_PART_NUMBER") "TLC59731DR")
        (field (name "MOUSER_PART_NUMBER") "595-TLC59731DR")
      )
      (libsource (lib "eagle-import") (part "NEOPIXEL-TLC59731DR"))
    )
    (comp (ref "IC3")
      (value "NEOPIXEL-TLC59731DR")
      (footprint "eagle-import:SOIC127P600X175-8N")
      (fields
        (field (name "ARROW_PART_NUMBER") "TLC59731DR")
        (field (name "MOUSER_PART_NUMBER") "595-TLC59731DR")
      )
      (libsource (lib "eagle-import") (part "NEOPIXEL-TLC59731DR"))
    )
    (comp (ref "IC4")
      (value "NEOPIXEL-TLC59731DR")
      (footprint "eagle-import:SOIC127P600X175-8N")
      (fields
        (field (name "ARROW_PART_NUMBER") "TLC59731DR")
        (field (name "MOUSER_PART_NUMBER") "595-TLC59731DR")
      )
      (libsource (lib "eagle-import") (part "NEOPIXEL-TLC59731DR"))
    )
    (comp (ref "IC5")
      (value "NEOPIXEL-TLC59731DR")
      (footprint "eagle-import:SOIC127P600X175-8N")
      (fields
        (field (name "ARROW_PART_NUMBER") "TLC59731DR")
        (field (name "MOUSER_PART_NUMBER") "595-TLC59731DR")
      )
      (libsource (lib "eagle-import") (part "NEOPIXEL-TLC59731DR"))
    )
    (comp (ref "IC6")
      (value "NEOPIXEL-TLC59731DR")
      (footprint "eagle-import:SOIC127P600X175-8N")
      (fields
        (field (name "ARROW_PART_NUMBER") "TLC59731DR")
        (field (name "MOUSER_PART_NUMBER") "595-TLC59731DR")
      )
      (libsource (lib "eagle-import") (part "NEOPIXEL-TLC59731DR"))
    )
    (comp (ref "IC7")
      (value "NEOPIXEL-TLC59731DR")
      (footprint "eagle-import:SOIC127P600X175-8N")
      (fields
        (field (name "ARROW_PART_NUMBER") "TLC59731DR")
        (field (name "MOUSER_PART_NUMBER") "595-TLC59731DR")
      )
      (libsource (lib "eagle-import") (part "NEOPIXEL-TLC59731DR"))
    )
    (comp (ref "IC8")
      (value "NEOPIXEL-TLC59731DR")
      (footprint "eagle-import:SOIC127P600X175-8N")
      (fields
        (field (name "ARROW_PART_NUMBER") "TLC59731DR")
        (field (name "MOUSER_PART_NUMBER") "595-TLC59731DR")
      )
      (libsource (lib "eagle-import") (part "NEOPIXEL-TLC59731DR"))
    )
    (comp (ref "IC9")
      (value "NEOPIXEL-TLC59731DR")
      (footprint "eagle-import:SOIC127P600X175-8N")
      (fields
        (field (name "ARROW_PART_NUMBER") "TLC59731DR")
        (field (name "MOUSER_PART_NUMBER") "595-TLC59731DR")
      )
      (libsource (lib "eagle-import") (part "NEOPIXEL-TLC59731DR"))
    )
    (comp (ref "IC10")
      (value "NEOPIXEL-TLC59731DR")
      (footprint "eagle-import:SOIC127P600X175-8N")
      (fields
        (field (name "ARROW_PART_NUMBER") "TLC59731DR")
        (field (name "MOUSER_PART_NUMBER") "595-TLC59731DR")
      )
      (libsource (lib "eagle-import") (part "NEOPIXEL-TLC59731DR"))
    )
    (comp (ref "IC11")
      (value "NEOPIXEL-TLC59731DR")
      (footprint "eagle-import:SOIC127P600X175-8N")
      (fields
        (field (name "ARROW_PART_NUMBER") "TLC59731DR")
        (field (name "MOUSER_PART_NUMBER") "595-TLC59731DR")
      )
      (libsource (lib "eagle-import") (part "NEOPIXEL-TLC59731DR"))
    )
    (comp (ref "IC12")
      (value "NEOPIXEL-TLC59731DR")
      (footprint "eagle-import:SOIC127P600X175-8N")
      (fields
        (field (name "ARROW_PART_NUMBER") "TLC59731DR")
        (field (name "MOUSER_PART_NUMBER") "595-TLC59731DR")
      )
      (libsource (lib "eagle-import") (part "NEOPIXEL-TLC59731DR"))
    )
    (comp (ref "IC13")
      (value "NEOPIXEL-TLC59731DR")
      (footprint "eagle-import:SOIC127P600X175-8N")
      (fields
        (field (name "ARROW_PART_NUMBER") "TLC59731DR")
        (field (name "MOUSER_PART_NUMBER") "595-TLC59731DR")
      )
      (libsource (lib "eagle-import") (part "NEOPIXEL-TLC59731DR"))
    )
    (comp (ref "MCP_000")
      (value "MCP23017")
      (footprint "eagle-import:SOIC-28")
      (libsource (lib "eagle-import") (part "MCP23017"))
    )
    (comp (ref "MCP_001")
      (value "MCP23017")
      (footprint "eagle-import:SOIC-28")
      (libsource (lib "eagle-import") (part "MCP23017"))
    )
    (comp (ref "R1")
      (value "1k")
      (footprint "eagle-import:R0805")
      (libsource (lib "eagle-import") (part "R-US_R0805"))
    )
    (comp (ref "R2")
      (value "1k")
      (footprint "eagle-import:R0805")
      (libsource (lib "eagle-import") (part "R-US_R0805"))
    )
    (comp (ref "R3")
      (value "1k")
      (footprint "eagle-import:R0805")
      (libsource (lib "eagle-import") (part "R-US_R0805"))
    )
    (comp (ref "R4")
      (value "1k")
      (footprint "eagle-import:R0805")
      (libsource (lib "eagle-import") (part "R-US_R0805"))
    )
    (comp (ref "R5")
      (value "470")
      (footprint "eagle-import:1206")
      (libsource (lib "eagle-import") (part "PASSIF-RESISTOR-1206"))
    )
    (comp (ref "R6")
      (value "470")
      (footprint "eagle-import:1206")
      (libsource (lib "eagle-import") (part "PASSIF-RESISTOR-1206"))
    )
    (comp (ref "R7")
      (value "470")
      (footprint "eagle-import:1206")
      (libsource (lib "eagle-import") (part "PASSIF-RESISTOR-1206"))
    )
    (comp (ref "R8")
      (value "470")
      (footprint "eagle-import:1206")
      (libsource (lib "eagle-import") (part "PASSIF-RESISTOR-1206"))
    )
    (comp (ref "R9")
      (value "470")
      (footprint "eagle-import:1206")
      (libsource (lib "eagle-import") (part "PASSIF-RESISTOR-1206"))
    )
    (comp (ref "R10")
      (value "470")
      (footprint "eagle-import:1206")
      (libsource (lib "eagle-import") (part "PASSIF-RESISTOR-1206"))
    )
    (comp (ref "R11")
      (value "470")
      (footprint "eagle-import:1206")
      (libsource (lib "eagle-import") (part "PASSIF-RESISTOR-1206"))
    )
    (comp (ref "R12")
      (value "470")
      (footprint "eagle-import:1206")
      (libsource (lib "eagle-import") (part "PASSIF-RESISTOR-1206"))
    )
    (comp (ref "R13")
      (value "470")
      (footprint "eagle-import:1206")
      (libsource (lib "eagle-import") (part "PASSIF-RESISTOR-1206"))
    )
    (comp (ref "R14")
      (value "470")
      (footprint "eagle-import:1206")
      (libsource (lib "eagle-import") (part "PASSIF-RESISTOR-1206"))
    )
    (comp (ref "R15")
      (value "100")
      (footprint "eagle-import:1206")
      (libsource (lib "eagle-import") (part "PASSIF-RESISTOR-1206"))
    )
    (comp (ref "R16")
      (value "100")
      (footprint "eagle-import:1206")
      (libsource (lib "eagle-import") (part "PASSIF-RESISTOR-1206"))
    )
    (comp (ref "R17")
      (value "100")
      (footprint "eagle-import:1206")
      (libsource (lib "eagle-import") (part "PASSIF-RESISTOR-1206"))
    )
    (comp (ref "R18")
      (value "10k")
      (footprint "eagle-import:1206")
      (libsource (lib "eagle-import") (part "PASSIF-RESISTOR-1206"))
    )
    (comp (ref "R19")
      (value "100")
      (footprint "eagle-import:1206")
      (libsource (lib "eagle-import") (part "PASSIF-RESISTOR-1206"))
    )
    (comp (ref "R20")
      (value "100")
      (footprint "eagle-import:1206")
      (libsource (lib "eagle-import") (part "PASSIF-RESISTOR-1206"))
    )
    (comp (ref "R21")
      (value "100")
      (footprint "eagle-import:1206")
      (libsource (lib "eagle-import") (part "PASSIF-RESISTOR-1206"))
    )
    (comp (ref "R22")
      (value "10k")
      (footprint "eagle-import:1206")
      (libsource (lib "eagle-import") (part "PASSIF-RESISTOR-1206"))
    )
    (comp (ref "R23")
      (value "100")
      (footprint "eagle-import:1206")
      (libsource (lib "eagle-import") (part "PASSIF-RESISTOR-1206"))
    )
    (comp (ref "R24")
      (value "100")
      (footprint "eagle-import:1206")
      (libsource (lib "eagle-import") (part "PASSIF-RESISTOR-1206"))
    )
    (comp (ref "R25")
      (value "100")
      (footprint "eagle-import:1206")
      (libsource (lib "eagle-import") (part "PASSIF-RESISTOR-1206"))
    )
    (comp (ref "R26")
      (value "10k")
      (footprint "eagle-import:1206")
      (libsource (lib "eagle-import") (part "PASSIF-RESISTOR-1206"))
    )
    (comp (ref "R27")
      (value "100")
      (footprint "eagle-import:1206")
      (libsource (lib "eagle-import") (part "PASSIF-RESISTOR-1206"))
    )
    (comp (ref "R28")
      (value "100")
      (footprint "eagle-import:1206")
      (libsource (lib "eagle-import") (part "PASSIF-RESISTOR-1206"))
    )
    (comp (ref "R29")
      (value "100")
      (footprint "eagle-import:1206")
      (libsource (lib "eagle-import") (part "PASSIF-RESISTOR-1206"))
    )
    (comp (ref "R30")
      (value "470")
      (footprint "eagle-import:1206")
      (libsource (lib "eagle-import") (part "PASSIF-RESISTOR-1206"))
    )
    (comp (ref "R31")
      (value "470")
      (footprint "eagle-import:1206")
      (libsource (lib "eagle-import") (part "PASSIF-RESISTOR-1206"))
    )
    (comp (ref "R32")
      (value "470")
      (footprint "eagle-import:1206")
      (libsource (lib "eagle-import") (part "PASSIF-RESISTOR-1206"))
    )
    (comp (ref "R33")
      (value "470")
      (footprint "eagle-import:1206")
      (libsource (lib "eagle-import") (part "PASSIF-RESISTOR-1206"))
    )
    (comp (ref "R34")
      (value "470")
      (footprint "eagle-import:1206")
      (libsource (lib "eagle-import") (part "PASSIF-RESISTOR-1206"))
    )
    (comp (ref "R35")
      (value "470")
      (footprint "eagle-import:1206")
      (libsource (lib "eagle-import") (part "PASSIF-RESISTOR-1206"))
    )
    (comp (ref "R36")
      (value "470")
      (footprint "eagle-import:1206")
      (libsource (lib "eagle-import") (part "PASSIF-RESISTOR-1206"))
    )
    (comp (ref "R37")
      (value "470")
      (footprint "eagle-import:1206")
      (libsource (lib "eagle-import") (part "PASSIF-RESISTOR-1206"))
    )
    (comp (ref "R38")
      (value "470")
      (footprint "eagle-import:1206")
      (libsource (lib "eagle-import") (part "PASSIF-RESISTOR-1206"))
    )
    (comp (ref "R39")
      (value "470")
      (footprint "eagle-import:1206")
      (libsource (lib "eagle-import") (part "PASSIF-RESISTOR-1206"))
    )
    (comp (ref "R40")
      (value "100")
      (footprint "eagle-import:1206")
      (libsource (lib "eagle-import") (part "PASSIF-RESISTOR-1206"))
    )
    (comp (ref "R41")
      (value "100")
      (footprint "eagle-import:1206")
      (libsource (lib "eagle-import") (part "PASSIF-RESISTOR-1206"))
    )
    (comp (ref "R42")
      (value "100")
      (footprint "eagle-import:1206")
      (libsource (lib "eagle-import") (part "PASSIF-RESISTOR-1206"))
    )
    (comp (ref "R43")
      (value "10k")
      (footprint "eagle-import:1206")
      (libsource (lib "eagle-import") (part "PASSIF-RESISTOR-1206"))
    )
    (comp (ref "R44")
      (value "100")
      (footprint "eagle-import:1206")
      (libsource (lib "eagle-import") (part "PASSIF-RESISTOR-1206"))
    )
    (comp (ref "R45")
      (value "100")
      (footprint "eagle-import:1206")
      (libsource (lib "eagle-import") (part "PASSIF-RESISTOR-1206"))
    )
    (comp (ref "R46")
      (value "100")
      (footprint "eagle-import:1206")
      (libsource (lib "eagle-import") (part "PASSIF-RESISTOR-1206"))
    )
    (comp (ref "R47")
      (value "10k")
      (footprint "eagle-import:1206")
      (libsource (lib "eagle-import") (part "PASSIF-RESISTOR-1206"))
    )
    (comp (ref "R48")
      (value "100")
      (footprint "eagle-import:1206")
      (libsource (lib "eagle-import") (part "PASSIF-RESISTOR-1206"))
    )
    (comp (ref "R49")
      (value "100")
      (footprint "eagle-import:1206")
      (libsource (lib "eagle-import") (part "PASSIF-RESISTOR-1206"))
    )
    (comp (ref "R50")
      (value "100")
      (footprint "eagle-import:1206")
      (libsource (lib "eagle-import") (part "PASSIF-RESISTOR-1206"))
    )
    (comp (ref "R51")
      (value "10k")
      (footprint "eagle-import:1206")
      (libsource (lib "eagle-import") (part "PASSIF-RESISTOR-1206"))
    )
    (comp (ref "R52")
      (value "100")
      (footprint "eagle-import:1206")
      (libsource (lib "eagle-import") (part "PASSIF-RESISTOR-1206"))
    )
    (comp (ref "R53")
      (value "100")
      (footprint "eagle-import:1206")
      (libsource (lib "eagle-import") (part "PASSIF-RESISTOR-1206"))
    )
    (comp (ref "R54")
      (value "100")
      (footprint "eagle-import:1206")
      (libsource (lib "eagle-import") (part "PASSIF-RESISTOR-1206"))
    )
    (comp (ref "R55")
      (value "470")
      (footprint "eagle-import:1206")
      (libsource (lib "eagle-import") (part "PASSIF-RESISTOR-1206"))
    )
    (comp (ref "R56")
      (value "470")
      (footprint "eagle-import:1206")
      (libsource (lib "eagle-import") (part "PASSIF-RESISTOR-1206"))
    )
    (comp (ref "R57")
      (value "470")
      (footprint "eagle-import:1206")
      (libsource (lib "eagle-import") (part "PASSIF-RESISTOR-1206"))
    )
    (comp (ref "R58")
      (value "470")
      (footprint "eagle-import:1206")
      (libsource (lib "eagle-import") (part "PASSIF-RESISTOR-1206"))
    )
    (comp (ref "R59")
      (value "470")
      (footprint "eagle-import:1206")
      (libsource (lib "eagle-import") (part "PASSIF-RESISTOR-1206"))
    )
    (comp (ref "R60")
      (value "470")
      (footprint "eagle-import:1206")
      (libsource (lib "eagle-import") (part "PASSIF-RESISTOR-1206"))
    )
    (comp (ref "R61")
      (value "470")
      (footprint "eagle-import:1206")
      (libsource (lib "eagle-import") (part "PASSIF-RESISTOR-1206"))
    )
    (comp (ref "R62")
      (value "470")
      (footprint "eagle-import:1206")
      (libsource (lib "eagle-import") (part "PASSIF-RESISTOR-1206"))
    )
    (comp (ref "R63")
      (value "470")
      (footprint "eagle-import:1206")
      (libsource (lib "eagle-import") (part "PASSIF-RESISTOR-1206"))
    )
    (comp (ref "R64")
      (value "470")
      (footprint "eagle-import:1206")
      (libsource (lib "eagle-import") (part "PASSIF-RESISTOR-1206"))
    )
    (comp (ref "R65")
      (value "470")
      (footprint "eagle-import:1206")
      (libsource (lib "eagle-import") (part "PASSIF-RESISTOR-1206"))
    )
    (comp (ref "R66")
      (value "100")
      (footprint "eagle-import:1206")
      (libsource (lib "eagle-import") (part "PASSIF-RESISTOR-1206"))
    )
    (comp (ref "R67")
      (value "100")
      (footprint "eagle-import:1206")
      (libsource (lib "eagle-import") (part "PASSIF-RESISTOR-1206"))
    )
    (comp (ref "R68")
      (value "100")
      (footprint "eagle-import:1206")
      (libsource (lib "eagle-import") (part "PASSIF-RESISTOR-1206"))
    )
    (comp (ref "R69")
      (value "10k")
      (footprint "eagle-import:1206")
      (libsource (lib "eagle-import") (part "PASSIF-RESISTOR-1206"))
    )
    (comp (ref "R70")
      (value "100")
      (footprint "eagle-import:1206")
      (libsource (lib "eagle-import") (part "PASSIF-RESISTOR-1206"))
    )
    (comp (ref "R71")
      (value "100")
      (footprint "eagle-import:1206")
      (libsource (lib "eagle-import") (part "PASSIF-RESISTOR-1206"))
    )
    (comp (ref "R72")
      (value "100")
      (footprint "eagle-import:1206")
      (libsource (lib "eagle-import") (part "PASSIF-RESISTOR-1206"))
    )
    (comp (ref "R73")
      (value "10k")
      (footprint "eagle-import:1206")
      (libsource (lib "eagle-import") (part "PASSIF-RESISTOR-1206"))
    )
    (comp (ref "R74")
      (value "100")
      (footprint "eagle-import:1206")
      (libsource (lib "eagle-import") (part "PASSIF-RESISTOR-1206"))
    )
    (comp (ref "R75")
      (value "100")
      (footprint "eagle-import:1206")
      (libsource (lib "eagle-import") (part "PASSIF-RESISTOR-1206"))
    )
    (comp (ref "R76")
      (value "100")
      (footprint "eagle-import:1206")
      (libsource (lib "eagle-import") (part "PASSIF-RESISTOR-1206"))
    )
    (comp (ref "R77")
      (value "10k")
      (footprint "eagle-import:1206")
      (libsource (lib "eagle-import") (part "PASSIF-RESISTOR-1206"))
    )
    (comp (ref "R78")
      (value "100")
      (footprint "eagle-import:1206")
      (libsource (lib "eagle-import") (part "PASSIF-RESISTOR-1206"))
    )
    (comp (ref "R79")
      (value "100")
      (footprint "eagle-import:1206")
      (libsource (lib "eagle-import") (part "PASSIF-RESISTOR-1206"))
    )
    (comp (ref "R80")
      (value "100")
      (footprint "eagle-import:1206")
      (libsource (lib "eagle-import") (part "PASSIF-RESISTOR-1206"))
    )
    (comp (ref "R81")
      (value "100")
      (footprint "eagle-import:1206")
      (libsource (lib "eagle-import") (part "PASSIF-RESISTOR-1206"))
    )
    (comp (ref "R82")
      (value "100")
      (footprint "eagle-import:1206")
      (libsource (lib "eagle-import") (part "PASSIF-RESISTOR-1206"))
    )
    (comp (ref "R83")
      (value "100")
      (footprint "eagle-import:1206")
      (libsource (lib "eagle-import") (part "PASSIF-RESISTOR-1206"))
    )
    (comp (ref "S1")
      (value "ENCODER-RGB-SWITCH-NO_NUT")
      (footprint "eagle-import:ENCODER_LED_3")
      (libsource (lib "eagle-import") (part "ENCODER-RGB-SWITCH-NO_NUT"))
    )
    (comp (ref "S2")
      (value "ENCODER-RGB-SWITCH-NO_NUT")
      (footprint "eagle-import:ENCODER_LED_3")
      (libsource (lib "eagle-import") (part "ENCODER-RGB-SWITCH-NO_NUT"))
    )
    (comp (ref "S3")
      (value "ENCODER-RGB-SWITCH-NO_NUT")
      (footprint "eagle-import:ENCODER_LED_3")
      (libsource (lib "eagle-import") (part "ENCODER-RGB-SWITCH-NO_NUT"))
    )
    (comp (ref "S4")
      (value "ENCODER-RGB-SWITCH-NO_NUT")
      (footprint "eagle-import:ENCODER_LED_3")
      (libsource (lib "eagle-import") (part "ENCODER-RGB-SWITCH-NO_NUT"))
    )
    (comp (ref "S5")
      (value "ENCODER-RGB-SWITCH-NO_NUT")
      (footprint "eagle-import:ENCODER_LED_3")
      (libsource (lib "eagle-import") (part "ENCODER-RGB-SWITCH-NO_NUT"))
    )
    (comp (ref "S6")
      (value "ENCODER-RGB-SWITCH-NO_NUT")
      (footprint "eagle-import:ENCODER_LED_3")
      (libsource (lib "eagle-import") (part "ENCODER-RGB-SWITCH-NO_NUT"))
    )
    (comp (ref "S7")
      (value "ENCODER-RGB-SWITCH-NO_NUT")
      (footprint "eagle-import:ENCODER_LED_3")
      (libsource (lib "eagle-import") (part "ENCODER-RGB-SWITCH-NO_NUT"))
    )
    (comp (ref "S8")
      (value "ENCODER-RGB-SWITCH-NO_NUT")
      (footprint "eagle-import:ENCODER_LED_3")
      (libsource (lib "eagle-import") (part "ENCODER-RGB-SWITCH-NO_NUT"))
    )
    (comp (ref "S9")
      (value "ENCODER-RGB-SWITCH-NO_NUT")
      (footprint "eagle-import:ENCODER_LED_3")
      (libsource (lib "eagle-import") (part "ENCODER-RGB-SWITCH-NO_NUT"))
    )
    (comp (ref "SW1")
      (value "B3F-1000")
      (footprint "eagle-import:B3F-1000")
      (fields
        (field (name "DIGI_KEY_PART_NUMBER") "SW400-ND")
        (field (name "MANUFACTURER") "Omron Electronics Inc-EMC Div")
        (field (name "CREATED_BY") "PCBLayout.com")
      )
      (libsource (lib "eagle-import") (part "B3F-1000"))
    )
    (comp (ref "SW2")
      (value "B3F-1000")
      (footprint "eagle-import:B3F-1000")
      (fields
        (field (name "DIGI_KEY_PART_NUMBER") "SW400-ND")
        (field (name "MANUFACTURER") "Omron Electronics Inc-EMC Div")
        (field (name "CREATED_BY") "PCBLayout.com")
      )
      (libsource (lib "eagle-import") (part "B3F-1000"))
    )
    (comp (ref "SW3")
      (value "B3F-1000")
      (footprint "eagle-import:B3F-1000")
      (fields
        (field (name "DIGI_KEY_PART_NUMBER") "SW400-ND")
        (field (name "MANUFACTURER") "Omron Electronics Inc-EMC Div")
        (field (name "CREATED_BY") "PCBLayout.com")
      )
      (libsource (lib "eagle-import") (part "B3F-1000"))
    )
    (comp (ref "SW4")
      (value "B3F-1000")
      (footprint "eagle-import:B3F-1000")
      (fields
        (field (name "DIGI_KEY_PART_NUMBER") "SW400-ND")
        (field (name "MANUFACTURER") "Omron Electronics Inc-EMC Div")
        (field (name "CREATED_BY") "PCBLayout.com")
      )
      (libsource (lib "eagle-import") (part "B3F-1000"))
    )
  )
  (nets
    (net (code "1") (name "3V3") (class "Default")
      (node (ref "C1") (pin "1") (pinfunction "1_1") (pintype "passive"))
      (node (ref "C100") (pin "1") (pinfunction "1_1") (pintype "passive"))
      (node (ref "C101") (pin "1") (pinfunction "1_1") (pintype "passive"))
      (node (ref "C102") (pin "1") (pinfunction "1_1") (pintype "passive"))
      (node (ref "C107") (pin "+") (pinfunction "+_+") (pintype "passive"))
      (node (ref "C108") (pin "+") (pinfunction "+_+") (pintype "passive"))
      (node (ref "C115") (pin "1") (pinfunction "1_1") (pintype "passive"))
      (node (ref "C116") (pin "1") (pinfunction "1_1") (pintype "passive"))
      (node (ref "C119") (pin "1") (pinfunction "1_1") (pintype "passive"))
      (node (ref "C120") (pin "1") (pinfunction "1_1") (pintype "passive"))
      (node (ref "C121") (pin "+") (pinfunction "+_+") (pintype "passive"))
      (node (ref "C122") (pin "+") (pinfunction "+_+") (pintype "passive"))
      (node (ref "C123") (pin "+") (pinfunction "+_+") (pintype "passive"))
      (node (ref "C124") (pin "+") (pinfunction "+_+") (pintype "passive"))
      (node (ref "C125") (pin "+") (pinfunction "+_+") (pintype "passive"))
      (node (ref "C126") (pin "+") (pinfunction "+_+") (pintype "passive"))
      (node (ref "C135") (pin "1") (pinfunction "1_1") (pintype "passive"))
      (node (ref "C136") (pin "1") (pinfunction "1_1") (pintype "passive"))
      (node (ref "C137") (pin "1") (pinfunction "1_1") (pintype "passive"))
      (node (ref "C138") (pin "1") (pinfunction "1_1") (pintype "passive"))
      (node (ref "C15") (pin "1") (pinfunction "1_1") (pintype "passive"))
      (node (ref "C16") (pin "1") (pinfunction "1_1") (pintype "passive"))
      (node (ref "C17") (pin "1") (pinfunction "1_1") (pintype "passive"))
      (node (ref "C18") (pin "1") (pinfunction "1_1") (pintype "passive"))
      (node (ref "C19") (pin "1") (pinfunction "1_1") (pintype "passive"))
      (node (ref "C2") (pin "+") (pinfunction "+_+") (pintype "passive"))
      (node (ref "C3") (pin "+") (pinfunction "+_+") (pintype "passive"))
      (node (ref "C30") (pin "1") (pinfunction "1_1") (pintype "passive"))
      (node (ref "C31") (pin "1") (pinfunction "1_1") (pintype "passive"))
      (node (ref "C32") (pin "1") (pinfunction "1_1") (pintype "passive"))
      (node (ref "C33") (pin "1") (pinfunction "1_1") (pintype "passive"))
      (node (ref "C4") (pin "1") (pinfunction "1_1") (pintype "passive"))
      (node (ref "C45") (pin "1") (pinfunction "1_1") (pintype "passive"))
      (node (ref "C46") (pin "1") (pinfunction "1_1") (pintype "passive"))
      (node (ref "C47") (pin "1") (pinfunction "1_1") (pintype "passive"))
      (node (ref "C48") (pin "1") (pinfunction "1_1") (pintype "passive"))
      (node (ref "C49") (pin "+") (pinfunction "+_+") (pintype "passive"))
      (node (ref "C50") (pin "1") (pinfunction "1_1") (pintype "passive"))
      (node (ref "C51") (pin "+") (pinfunction "+_+") (pintype "passive"))
      (node (ref "C52") (pin "+") (pinfunction "+_+") (pintype "passive"))
      (node (ref "C53") (pin "+") (pinfunction "+_+") (pintype "passive"))
      (node (ref "C54") (pin "+") (pinfunction "+_+") (pintype "passive"))
      (node (ref "C63") (pin "1") (pinfunction "1_1") (pintype "passive"))
      (node (ref "C64") (pin "1") (pinfunction "1_1") (pintype "passive"))
      (node (ref "C65") (pin "1") (pinfunction "1_1") (pintype "passive"))
      (node (ref "C66") (pin "1") (pinfunction "1_1") (pintype "passive"))
      (node (ref "C75") (pin "1") (pinfunction "1_1") (pintype "passive"))
      (node (ref "C76") (pin "1") (pinfunction "1_1") (pintype "passive"))
      (node (ref "C77") (pin "1") (pinfunction "1_1") (pintype "passive"))
      (node (ref "C78") (pin "1") (pinfunction "1_1") (pintype "passive"))
      (node (ref "C79") (pin "+") (pinfunction "+_+") (pintype "passive"))
      (node (ref "C80") (pin "+") (pinfunction "+_+") (pintype "passive"))
      (node (ref "C81") (pin "+") (pinfunction "+_+") (pintype "passive"))
      (node (ref "C82") (pin "+") (pinfunction "+_+") (pintype "passive"))
      (node (ref "C83") (pin "+") (pinfunction "+_+") (pintype "passive"))
      (node (ref "C84") (pin "+") (pinfunction "+_+") (pintype "passive"))
      (node (ref "C85") (pin "1") (pinfunction "1_1") (pintype "passive"))
      (node (ref "C86") (pin "1") (pinfunction "1_1") (pintype "passive"))
      (node (ref "C87") (pin "+") (pinfunction "+_+") (pintype "passive"))
      (node (ref "C88") (pin "+") (pinfunction "+_+") (pintype "passive"))
      (node (ref "C89") (pin "+") (pinfunction "+_+") (pintype "passive"))
      (node (ref "C90") (pin "+") (pinfunction "+_+") (pintype "passive"))
      (node (ref "C99") (pin "1") (pinfunction "1_1") (pintype "passive"))
      (node (ref "CON_NORTH_BRD") (pin "2") (pinfunction "2_2") (pintype "passive"))
      (node (ref "CON_NORTH_BRD") (pin "4") (pinfunction "4_4") (pintype "passive"))
      (node (ref "D1") (pin "2") (pinfunction "+_2") (pintype "bidirectional"))
      (node (ref "D10") (pin "2") (pinfunction "+_2") (pintype "bidirectional"))
      (node (ref "D2") (pin "2") (pinfunction "+_2") (pintype "bidirectional"))
      (node (ref "D3") (pin "2") (pinfunction "+_2") (pintype "bidirectional"))
      (node (ref "D4") (pin "2") (pinfunction "+_2") (pintype "bidirectional"))
      (node (ref "D5") (pin "2") (pinfunction "+_2") (pintype "bidirectional"))
      (node (ref "D6") (pin "2") (pinfunction "+_2") (pintype "bidirectional"))
      (node (ref "D7") (pin "2") (pinfunction "+_2") (pintype "bidirectional"))
      (node (ref "D8") (pin "2") (pinfunction "+_2") (pintype "bidirectional"))
      (node (ref "D9") (pin "2") (pinfunction "+_2") (pintype "bidirectional"))
      (node (ref "IC1") (pin "8") (pinfunction "VCC_8") (pintype "bidirectional"))
      (node (ref "IC10") (pin "8") (pinfunction "VCC_8") (pintype "bidirectional"))
      (node (ref "IC11") (pin "8") (pinfunction "VCC_8") (pintype "bidirectional"))
      (node (ref "IC12") (pin "8") (pinfunction "VCC_8") (pintype "bidirectional"))
      (node (ref "IC13") (pin "8") (pinfunction "VCC_8") (pintype "bidirectional"))
      (node (ref "IC14") (pin "8") (pinfunction "VCC_8") (pintype "bidirectional"))
      (node (ref "IC15") (pin "8") (pinfunction "VCC_8") (pintype "bidirectional"))
      (node (ref "IC16") (pin "8") (pinfunction "VCC_8") (pintype "bidirectional"))
      (node (ref "IC17") (pin "8") (pinfunction "VCC_8") (pintype "bidirectional"))
      (node (ref "IC18") (pin "8") (pinfunction "VCC_8") (pintype "bidirectional"))
      (node (ref "IC19") (pin "8") (pinfunction "VCC_8") (pintype "bidirectional"))
      (node (ref "IC2") (pin "8") (pinfunction "VCC_8") (pintype "bidirectional"))
      (node (ref "IC20") (pin "8") (pinfunction "VCC_8") (pintype "bidirectional"))
      (node (ref "IC21") (pin "8") (pinfunction "VCC_8") (pintype "bidirectional"))
      (node (ref "IC22") (pin "8") (pinfunction "VCC_8") (pintype "bidirectional"))
      (node (ref "IC23") (pin "8") (pinfunction "VCC_8") (pintype "bidirectional"))
      (node (ref "IC24") (pin "8") (pinfunction "VCC_8") (pintype "bidirectional"))
      (node (ref "IC25") (pin "8") (pinfunction "VCC_8") (pintype "bidirectional"))
      (node (ref "IC26") (pin "8") (pinfunction "VCC_8") (pintype "bidirectional"))
      (node (ref "IC27") (pin "8") (pinfunction "VCC_8") (pintype "bidirectional"))
      (node (ref "IC28") (pin "8") (pinfunction "VCC_8") (pintype "bidirectional"))
      (node (ref "IC29") (pin "8") (pinfunction "VCC_8") (pintype "bidirectional"))
      (node (ref "IC3") (pin "8") (pinfunction "VCC_8") (pintype "bidirectional"))
      (node (ref "IC30") (pin "8") (pinfunction "VCC_8") (pintype "bidirectional"))
      (node (ref "IC31") (pin "8") (pinfunction "VCC_8") (pintype "bidirectional"))
      (node (ref "IC32") (pin "8") (pinfunction "VCC_8") (pintype "bidirectional"))
      (node (ref "IC33") (pin "8") (pinfunction "VCC_8") (pintype "bidirectional"))
      (node (ref "IC4") (pin "8") (pinfunction "VCC_8") (pintype "bidirectional"))
      (node (ref "IC5") (pin "8") (pinfunction "VCC_8") (pintype "bidirectional"))
      (node (ref "IC6") (pin "8") (pinfunction "VCC_8") (pintype "bidirectional"))
      (node (ref "IC7") (pin "8") (pinfunction "VCC_8") (pintype "bidirectional"))
      (node (ref "IC8") (pin "8") (pinfunction "VCC_8") (pintype "bidirectional"))
      (node (ref "IC9") (pin "8") (pinfunction "VCC_8") (pintype "bidirectional"))
      (node (ref "MCP_000") (pin "9") (pinfunction "VDD_9") (pintype "bidirectional"))
      (node (ref "MCP_001") (pin "15") (pinfunction "A0_15") (pintype "bidirectional"))
      (node (ref "MCP_001") (pin "9") (pinfunction "VDD_9") (pintype "bidirectional"))
      (node (ref "MCP_010") (pin "16") (pinfunction "A1_16") (pintype "bidirectional"))
      (node (ref "MCP_010") (pin "9") (pinfunction "VDD_9") (pintype "bidirectional"))
      (node (ref "MCP_011") (pin "15") (pinfunction "A0_15") (pintype "bidirectional"))
      (node (ref "MCP_011") (pin "16") (pinfunction "A1_16") (pintype "bidirectional"))
      (node (ref "MCP_011") (pin "9") (pinfunction "VDD_9") (pintype "bidirectional"))
      (node (ref "MCP_100") (pin "17") (pinfunction "A2_17") (pintype "bidirectional"))
      (node (ref "MCP_100") (pin "9") (pinfunction "VDD_9") (pintype "bidirectional"))
      (node (ref "R1") (pin "2") (pinfunction "2_2") (pintype "passive"))
      (node (ref "R130") (pin "2") (pinfunction "2_2") (pintype "passive"))
      (node (ref "R131") (pin "2") (pinfunction "2_2") (pintype "passive"))
      (node (ref "R132") (pin "2") (pinfunction "2_2") (pintype "passive"))
      (node (ref "R133") (pin "2") (pinfunction "2_2") (pintype "passive"))
      (node (ref "R2") (pin "2") (pinfunction "2_2") (pintype "passive"))
      (node (ref "R3") (pin "2") (pinfunction "2_2") (pintype "passive"))
      (node (ref "R4") (pin "2") (pinfunction "2_2") (pintype "passive"))
      (node (ref "R84") (pin "2") (pinfunction "2_2") (pintype "passive"))
      (node (ref "R85") (pin "2") (pinfunction "2_2") (pintype "passive"))
      (node (ref "S1") (pin "5") (pinfunction "+_5") (pintype "passive"))
      (node (ref "S10") (pin "5") (pinfunction "+_5") (pintype "passive"))
      (node (ref "S11") (pin "5") (pinfunction "+_5") (pintype "passive"))
      (node (ref "S12") (pin "5") (pinfunction "+_5") (pintype "passive"))
      (node (ref "S13") (pin "5") (pinfunction "+_5") (pintype "passive"))
      (node (ref "S14") (pin "5") (pinfunction "+_5") (pintype "passive"))
      (node (ref "S15") (pin "5") (pinfunction "+_5") (pintype "passive"))
      (node (ref "S16") (pin "5") (pinfunction "+_5") (pintype "passive"))
      (node (ref "S17") (pin "5") (pinfunction "+_5") (pintype "passive"))
      (node (ref "S18") (pin "5") (pinfunction "+_5") (pintype "passive"))
      (node (ref "S19") (pin "5") (pinfunction "+_5") (pintype "passive"))
      (node (ref "S2") (pin "5") (pinfunction "+_5") (pintype "passive"))
      (node (ref "S20") (pin "5") (pinfunction "+_5") (pintype "passive"))
      (node (ref "S21") (pin "5") (pinfunction "+_5") (pintype "passive"))
      (node (ref "S22") (pin "5") (pinfunction "+_5") (pintype "passive"))
      (node (ref "S23") (pin "5") (pinfunction "+_5") (pintype "passive"))
      (node (ref "S3") (pin "5") (pinfunction "+_5") (pintype "passive"))
      (node (ref "S4") (pin "5") (pinfunction "+_5") (pintype "passive"))
      (node (ref "S5") (pin "5") (pinfunction "+_5") (pintype "passive"))
      (node (ref "S6") (pin "5") (pinfunction "+_5") (pintype "passive"))
      (node (ref "S7") (pin "5") (pinfunction "+_5") (pintype "passive"))
      (node (ref "S8") (pin "5") (pinfunction "+_5") (pintype "passive"))
      (node (ref "S9") (pin "5") (pinfunction "+_5") (pintype "passive"))
    )
    (net (code "2") (name "DATA_PIXEL11") (class "Default")
      (node (ref "IC4") (pin "5") (pinfunction "SDO_5") (pintype "bidirectional"))
      (node (ref "IC8") (pin "6") (pinfunction "SDI_6") (pintype "bidirectional"))
    )
    (net (code "3") (name "DATA_PIXEL12") (class "Default")
      (node (ref "IC1") (pin "5") (pinfunction "SDO_5") (pintype "bidirectional"))
      (node (ref "IC4") (pin "6") (pinfunction "SDI_6") (pintype "bidirectional"))
    )
    (net (code "4") (name "DATA_PIXEL13") (class "Default")
      (node (ref "IC1") (pin "6") (pinfunction "SDI_6") (pintype "bidirectional"))
      (node (ref "IC3") (pin "5") (pinfunction "SDO_5") (pintype "bidirectional"))
    )
    (net (code "5") (name "DATA_PIXEL14") (class "Default")
      (node (ref "IC2") (pin "5") (pinfunction "SDO_5") (pintype "bidirectional"))
      (node (ref "IC3") (pin "6") (pinfunction "SDI_6") (pintype "bidirectional"))
    )
    (net (code "6") (name "DATA_PIXEL21") (class "Default")
      (node (ref "IC7") (pin "6") (pinfunction "SDI_6") (pintype "bidirectional"))
      (node (ref "IC8") (pin "5") (pinfunction "SDO_5") (pintype "bidirectional"))
    )
    (net (code "7") (name "DATA_PIXEL22") (class "Default")
      (node (ref "IC6") (pin "6") (pinfunction "SDI_6") (pintype "bidirectional"))
      (node (ref "IC7") (pin "5") (pinfunction "SDO_5") (pintype "bidirectional"))
    )
    (net (code "8") (name "DATA_PIXEL23") (class "Default")
      (node (ref "IC5") (pin "6") (pinfunction "SDI_6") (pintype "bidirectional"))
      (node (ref "IC6") (pin "5") (pinfunction "SDO_5") (pintype "bidirectional"))
    )
    (net (code "9") (name "DATA_PIXEL24") (class "Default")
      (node (ref "IC5") (pin "5") (pinfunction "SDO_5") (pintype "bidirectional"))
      (node (ref "IC9") (pin "6") (pinfunction "SDI_6") (pintype "bidirectional"))
    )
    (net (code "10") (name "DATA_PIXEL32") (class "Default")
      (node (ref "IC12") (pin "5") (pinfunction "SDO_5") (pintype "bidirectional"))
      (node (ref "IC13") (pin "6") (pinfunction "SDI_6") (pintype "bidirectional"))
    )
    (net (code "11") (name "DATA_PIXEL33") (class "Default")
      (node (ref "IC11") (pin "5") (pinfunction "SDO_5") (pintype "bidirectional"))
      (node (ref "IC12") (pin "6") (pinfunction "SDI_6") (pintype "bidirectional"))
    )
    (net (code "12") (name "DATA_PIXEL34") (class "Default")
      (node (ref "IC10") (pin "5") (pinfunction "SDO_5") (pintype "bidirectional"))
      (node (ref "IC11") (pin "6") (pinfunction "SDI_6") (pintype "bidirectional"))
    )
    (net (code "13") (name "DATA_PIXEL35") (class "Default")
      (node (ref "IC10") (pin "6") (pinfunction "SDI_6") (pintype "bidirectional"))
      (node (ref "IC9") (pin "5") (pinfunction "SDO_5") (pintype "bidirectional"))
    )
    (net (code "14") (name "GND") (class "Default")
      (node (ref "C1") (pin "2") (pinfunction "2_2") (pintype "passive"))
      (node (ref "C10") (pin "1") (pinfunction "1_1") (pintype "passive"))
      (node (ref "C100") (pin "2") (pinfunction "2_2") (pintype "passive"))
      (node (ref "C101") (pin "2") (pinfunction "2_2") (pintype "passive"))
      (node (ref "C102") (pin "2") (pinfunction "2_2") (pintype "passive"))
      (node (ref "C103") (pin "2") (pinfunction "2_2") (pintype "passive"))
      (node (ref "C104") (pin "2") (pinfunction "2_2") (pintype "passive"))
      (node (ref "C105") (pin "2") (pinfunction "2_2") (pintype "passive"))
      (node (ref "C106") (pin "2") (pinfunction "2_2") (pintype "passive"))
      (node (ref "C107") (pin "-") (pinfunction "-_-") (pintype "passive"))
      (node (ref "C108") (pin "-") (pinfunction "-_-") (pintype "passive"))
      (node (ref "C109") (pin "1") (pinfunction "1_1") (pintype "passive"))
      (node (ref "C11") (pin "1") (pinfunction "1_1") (pintype "passive"))
      (node (ref "C110") (pin "1") (pinfunction "1_1") (pintype "passive"))
      (node (ref "C111") (pin "1") (pinfunction "1_1") (pintype "passive"))
      (node (ref "C112") (pin "1") (pinfunction "1_1") (pintype "passive"))
      (node (ref "C113") (pin "1") (pinfunction "1_1") (pintype "passive"))
      (node (ref "C114") (pin "1") (pinfunction "1_1") (pintype "passive"))
      (node (ref "C115") (pin "2") (pinfunction "2_2") (pintype "passive"))
      (node (ref "C116") (pin "2") (pinfunction "2_2") (pintype "passive"))
      (node (ref "C117") (pin "2") (pinfunction "2_2") (pintype "passive"))
      (node (ref "C118") (pin "2") (pinfunction "2_2") (pintype "passive"))
      (node (ref "C119") (pin "2") (pinfunction "2_2") (pintype "passive"))
      (node (ref "C12") (pin "2") (pinfunction "2_2") (pintype "passive"))
      (node (ref "C120") (pin "2") (pinfunction "2_2") (pintype "passive"))
      (node (ref "C121") (pin "-") (pinfunction "-_-") (pintype "passive"))
      (node (ref "C122") (pin "-") (pinfunction "-_-") (pintype "passive"))
      (node (ref "C123") (pin "-") (pinfunction "-_-") (pintype "passive"))
      (node (ref "C124") (pin "-") (pinfunction "-_-") (pintype "passive"))
      (node (ref "C125") (pin "-") (pinfunction "-_-") (pintype "passive"))
      (node (ref "C126") (pin "-") (pinfunction "-_-") (pintype "passive"))
      (node (ref "C127") (pin "1") (pinfunction "1_1") (pintype "passive"))
      (node (ref "C128") (pin "1") (pinfunction "1_1") (pintype "passive"))
      (node (ref "C129") (pin "1") (pinfunction "1_1") (pintype "passive"))
      (node (ref "C13") (pin "2") (pinfunction "2_2") (pintype "passive"))
      (node (ref "C130") (pin "1") (pinfunction "1_1") (pintype "passive"))
      (node (ref "C131") (pin "1") (pinfunction "1_1") (pintype "passive"))
      (node (ref "C132") (pin "1") (pinfunction "1_1") (pintype "passive"))
      (node (ref "C133") (pin "1") (pinfunction "1_1") (pintype "passive"))
      (node (ref "C134") (pin "1") (pinfunction "1_1") (pintype "passive"))
      (node (ref "C135") (pin "2") (pinfunction "2_2") (pintype "passive"))
      (node (ref "C136") (pin "2") (pinfunction "2_2") (pintype "passive"))
      (node (ref "C137") (pin "2") (pinfunction "2_2") (pintype "passive"))
      (node (ref "C138") (pin "2") (pinfunction "2_2") (pintype "passive"))
      (node (ref "C139") (pin "2") (pinfunction "2_2") (pintype "passive"))
      (node (ref "C14") (pin "2") (pinfunction "2_2") (pintype "passive"))
      (node (ref "C140") (pin "2") (pinfunction "2_2") (pintype "passive"))
      (node (ref "C141") (pin "2") (pinfunction "2_2") (pintype "passive"))
      (node (ref "C142") (pin "2") (pinfunction "2_2") (pintype "passive"))
      (node (ref "C15") (pin "2") (pinfunction "2_2") (pintype "passive"))
      (node (ref "C16") (pin "2") (pinfunction "2_2") (pintype "passive"))
      (node (ref "C17") (pin "2") (pinfunction "2_2") (pintype "passive"))
      (node (ref "C18") (pin "2") (pinfunction "2_2") (pintype "passive"))
      (node (ref "C19") (pin "2") (pinfunction "2_2") (pintype "passive"))
      (node (ref "C2") (pin "-") (pinfunction "-_-") (pintype "passive"))
      (node (ref "C20") (pin "1") (pinfunction "1_1") (pintype "passive"))
      (node (ref "C21") (pin "1") (pinfunction "1_1") (pintype "passive"))
      (node (ref "C22") (pin "1") (pinfunction "1_1") (pintype "passive"))
      (node (ref "C23") (pin "1") (pinfunction "1_1") (pintype "passive"))
      (node (ref "C24") (pin "1") (pinfunction "1_1") (pintype "passive"))
      (node (ref "C25") (pin "1") (pinfunction "1_1") (pintype "passive"))
      (node (ref "C26") (pin "1") (pinfunction "1_1") (pintype "passive"))
      (node (ref "C27") (pin "2") (pinfunction "2_2") (pintype "passive"))
      (node (ref "C28") (pin "2") (pinfunction "2_2") (pintype "passive"))
      (node (ref "C29") (pin "2") (pinfunction "2_2") (pintype "passive"))
      (node (ref "C3") (pin "-") (pinfunction "-_-") (pintype "passive"))
      (node (ref "C30") (pin "2") (pinfunction "2_2") (pintype "passive"))
      (node (ref "C31") (pin "2") (pinfunction "2_2") (pintype "passive"))
      (node (ref "C32") (pin "2") (pinfunction "2_2") (pintype "passive"))
      (node (ref "C33") (pin "2") (pinfunction "2_2") (pintype "passive"))
      (node (ref "C34") (pin "1") (pinfunction "1_1") (pintype "passive"))
      (node (ref "C35") (pin "1") (pinfunction "1_1") (pintype "passive"))
      (node (ref "C36") (pin "1") (pinfunction "1_1") (pintype "passive"))
      (node (ref "C37") (pin "1") (pinfunction "1_1") (pintype "passive"))
      (node (ref "C38") (pin "1") (pinfunction "1_1") (pintype "passive"))
      (node (ref "C39") (pin "1") (pinfunction "1_1") (pintype "passive"))
      (node (ref "C4") (pin "2") (pinfunction "2_2") (pintype "passive"))
      (node (ref "C40") (pin "1") (pinfunction "1_1") (pintype "passive"))
      (node (ref "C41") (pin "1") (pinfunction "1_1") (pintype "passive"))
      (node (ref "C42") (pin "2") (pinfunction "2_2") (pintype "passive"))
      (node (ref "C43") (pin "2") (pinfunction "2_2") (pintype "passive"))
      (node (ref "C44") (pin "2") (pinfunction "2_2") (pintype "passive"))
      (node (ref "C45") (pin "2") (pinfunction "2_2") (pintype "passive"))
      (node (ref "C46") (pin "2") (pinfunction "2_2") (pintype "passive"))
      (node (ref "C47") (pin "2") (pinfunction "2_2") (pintype "passive"))
      (node (ref "C48") (pin "2") (pinfunction "2_2") (pintype "passive"))
      (node (ref "C49") (pin "-") (pinfunction "-_-") (pintype "passive"))
      (node (ref "C5") (pin "1") (pinfunction "1_1") (pintype "passive"))
      (node (ref "C50") (pin "2") (pinfunction "2_2") (pintype "passive"))
      (node (ref "C51") (pin "-") (pinfunction "-_-") (pintype "passive"))
      (node (ref "C52") (pin "-") (pinfunction "-_-") (pintype "passive"))
      (node (ref "C53") (pin "-") (pinfunction "-_-") (pintype "passive"))
      (node (ref "C54") (pin "-") (pinfunction "-_-") (pintype "passive"))
      (node (ref "C55") (pin "1") (pinfunction "1_1") (pintype "passive"))
      (node (ref "C56") (pin "1") (pinfunction "1_1") (pintype "passive"))
      (node (ref "C57") (pin "1") (pinfunction "1_1") (pintype "passive"))
      (node (ref "C58") (pin "1") (pinfunction "1_1") (pintype "passive"))
      (node (ref "C59") (pin "1") (pinfunction "1_1") (pintype "passive"))
      (node (ref "C6") (pin "1") (pinfunction "1_1") (pintype "passive"))
      (node (ref "C60") (pin "1") (pinfunction "1_1") (pintype "passive"))
      (node (ref "C61") (pin "1") (pinfunction "1_1") (pintype "passive"))
      (node (ref "C62") (pin "1") (pinfunction "1_1") (pintype "passive"))
      (node (ref "C63") (pin "2") (pinfunction "2_2") (pintype "passive"))
      (node (ref "C64") (pin "2") (pinfunction "2_2") (pintype "passive"))
      (node (ref "C65") (pin "2") (pinfunction "2_2") (pintype "passive"))
      (node (ref "C66") (pin "2") (pinfunction "2_2") (pintype "passive"))
      (node (ref "C67") (pin "2") (pinfunction "2_2") (pintype "passive"))
      (node (ref "C68") (pin "2") (pinfunction "2_2") (pintype "passive"))
      (node (ref "C69") (pin "2") (pinfunction "2_2") (pintype "passive"))
      (node (ref "C7") (pin "1") (pinfunction "1_1") (pintype "passive"))
      (node (ref "C70") (pin "2") (pinfunction "2_2") (pintype "passive"))
      (node (ref "C71") (pin "1") (pinfunction "1_1") (pintype "passive"))
      (node (ref "C72") (pin "1") (pinfunction "1_1") (pintype "passive"))
      (node (ref "C73") (pin "1") (pinfunction "1_1") (pintype "passive"))
      (node (ref "C74") (pin "1") (pinfunction "1_1") (pintype "passive"))
      (node (ref "C75") (pin "2") (pinfunction "2_2") (pintype "passive"))
      (node (ref "C76") (pin "2") (pinfunction "2_2") (pintype "passive"))
      (node (ref "C77") (pin "2") (pinfunction "2_2") (pintype "passive"))
      (node (ref "C78") (pin "2") (pinfunction "2_2") (pintype "passive"))
      (node (ref "C79") (pin "-") (pinfunction "-_-") (pintype "passive"))
      (node (ref "C8") (pin "1") (pinfunction "1_1") (pintype "passive"))
      (node (ref "C80") (pin "-") (pinfunction "-_-") (pintype "passive"))
      (node (ref "C81") (pin "-") (pinfunction "-_-") (pintype "passive"))
      (node (ref "C82") (pin "-") (pinfunction "-_-") (pintype "passive"))
      (node (ref "C83") (pin "-") (pinfunction "-_-") (pintype "passive"))
      (node (ref "C84") (pin "-") (pinfunction "-_-") (pintype "passive"))
      (node (ref "C85") (pin "2") (pinfunction "2_2") (pintype "passive"))
      (node (ref "C86") (pin "2") (pinfunction "2_2") (pintype "passive"))
      (node (ref "C87") (pin "-") (pinfunction "-_-") (pintype "passive"))
      (node (ref "C88") (pin "-") (pinfunction "-_-") (pintype "passive"))
      (node (ref "C89") (pin "-") (pinfunction "-_-") (pintype "passive"))
      (node (ref "C9") (pin "1") (pinfunction "1_1") (pintype "passive"))
      (node (ref "C90") (pin "-") (pinfunction "-_-") (pintype "passive"))
      (node (ref "C91") (pin "1") (pinfunction "1_1") (pintype "passive"))
      (node (ref "C92") (pin "1") (pinfunction "1_1") (pintype "passive"))
      (node (ref "C93") (pin "1") (pinfunction "1_1") (pintype "passive"))
      (node (ref "C94") (pin "1") (pinfunction "1_1") (pintype "passive"))
      (node (ref "C95") (pin "1") (pinfunction "1_1") (pintype "passive"))
      (node (ref "C96") (pin "1") (pinfunction "1_1") (pintype "passive"))
      (node (ref "C97") (pin "1") (pinfunction "1_1") (pintype "passive"))
      (node (ref "C98") (pin "1") (pinfunction "1_1") (pintype "passive"))
      (node (ref "C99") (pin "2") (pinfunction "2_2") (pintype "passive"))
      (node (ref "CON_NORTH_BRD") (pin "1") (pinfunction "1_1") (pintype "passive"))
      (node (ref "IC1") (pin "4") (pinfunction "GND_4") (pintype "bidirectional"))
      (node (ref "IC10") (pin "4") (pinfunction "GND_4") (pintype "bidirectional"))
      (node (ref "IC11") (pin "4") (pinfunction "GND_4") (pintype "bidirectional"))
      (node (ref "IC12") (pin "4") (pinfunction "GND_4") (pintype "bidirectional"))
      (node (ref "IC13") (pin "4") (pinfunction "GND_4") (pintype "bidirectional"))
      (node (ref "IC14") (pin "4") (pinfunction "GND_4") (pintype "bidirectional"))
      (node (ref "IC15") (pin "4") (pinfunction "GND_4") (pintype "bidirectional"))
      (node (ref "IC16") (pin "4") (pinfunction "GND_4") (pintype "bidirectional"))
      (node (ref "IC17") (pin "4") (pinfunction "GND_4") (pintype "bidirectional"))
      (node (ref "IC18") (pin "4") (pinfunction "GND_4") (pintype "bidirectional"))
      (node (ref "IC19") (pin "4") (pinfunction "GND_4") (pintype "bidirectional"))
      (node (ref "IC2") (pin "4") (pinfunction "GND_4") (pintype "bidirectional"))
      (node (ref "IC20") (pin "4") (pinfunction "GND_4") (pintype "bidirectional"))
      (node (ref "IC21") (pin "4") (pinfunction "GND_4") (pintype "bidirectional"))
      (node (ref "IC22") (pin "4") (pinfunction "GND_4") (pintype "bidirectional"))
      (node (ref "IC23") (pin "4") (pinfunction "GND_4") (pintype "bidirectional"))
      (node (ref "IC24") (pin "4") (pinfunction "GND_4") (pintype "bidirectional"))
      (node (ref "IC25") (pin "4") (pinfunction "GND_4") (pintype "bidirectional"))
      (node (ref "IC26") (pin "4") (pinfunction "GND_4") (pintype "bidirectional"))
      (node (ref "IC27") (pin "4") (pinfunction "GND_4") (pintype "bidirectional"))
      (node (ref "IC28") (pin "4") (pinfunction "GND_4") (pintype "bidirectional"))
      (node (ref "IC29") (pin "4") (pinfunction "GND_4") (pintype "bidirectional"))
      (node (ref "IC3") (pin "4") (pinfunction "GND_4") (pintype "bidirectional"))
      (node (ref "IC30") (pin "4") (pinfunction "GND_4") (pintype "bidirectional"))
      (node (ref "IC31") (pin "4") (pinfunction "GND_4") (pintype "bidirectional"))
      (node (ref "IC32") (pin "4") (pinfunction "GND_4") (pintype "bidirectional"))
      (node (ref "IC33") (pin "4") (pinfunction "GND_4") (pintype "bidirectional"))
      (node (ref "IC4") (pin "4") (pinfunction "GND_4") (pintype "bidirectional"))
      (node (ref "IC5") (pin "4") (pinfunction "GND_4") (pintype "bidirectional"))
      (node (ref "IC6") (pin "4") (pinfunction "GND_4") (pintype "bidirectional"))
      (node (ref "IC7") (pin "4") (pinfunction "GND_4") (pintype "bidirectional"))
      (node (ref "IC8") (pin "4") (pinfunction "GND_4") (pintype "bidirectional"))
      (node (ref "IC9") (pin "4") (pinfunction "GND_4") (pintype "bidirectional"))
      (node (ref "MCP_000") (pin "10") (pinfunction "VSS_10") (pintype "bidirectional"))
      (node (ref "MCP_000") (pin "15") (pinfunction "A0_15") (pintype "bidirectional"))
      (node (ref "MCP_000") (pin "16") (pinfunction "A1_16") (pintype "bidirectional"))
      (node (ref "MCP_000") (pin "17") (pinfunction "A2_17") (pintype "bidirectional"))
      (node (ref "MCP_001") (pin "10") (pinfunction "VSS_10") (pintype "bidirectional"))
      (node (ref "MCP_001") (pin "16") (pinfunction "A1_16") (pintype "bidirectional"))
      (node (ref "MCP_001") (pin "17") (pinfunction "A2_17") (pintype "bidirectional"))
      (node (ref "MCP_010") (pin "10") (pinfunction "VSS_10") (pintype "bidirectional"))
      (node (ref "MCP_010") (pin "15") (pinfunction "A0_15") (pintype "bidirectional"))
      (node (ref "MCP_010") (pin "17") (pinfunction "A2_17") (pintype "bidirectional"))
      (node (ref "MCP_011") (pin "10") (pinfunction "VSS_10") (pintype "bidirectional"))
      (node (ref "MCP_011") (pin "17") (pinfunction "A2_17") (pintype "bidirectional"))
      (node (ref "MCP_100") (pin "10") (pinfunction "VSS_10") (pintype "bidirectional"))
      (node (ref "MCP_100") (pin "15") (pinfunction "A0_15") (pintype "bidirectional"))
      (node (ref "MCP_100") (pin "16") (pinfunction "A1_16") (pintype "bidirectional"))
      (node (ref "R101") (pin "2") (pinfunction "2_2") (pintype "passive"))
      (node (ref "R105") (pin "2") (pinfunction "2_2") (pintype "passive"))
      (node (ref "R109") (pin "2") (pinfunction "2_2") (pintype "passive"))
      (node (ref "R113") (pin "2") (pinfunction "2_2") (pintype "passive"))
      (node (ref "R149") (pin "2") (pinfunction "2_2") (pintype "passive"))
      (node (ref "R153") (pin "2") (pinfunction "2_2") (pintype "passive"))
      (node (ref "R157") (pin "2") (pinfunction "2_2") (pintype "passive"))
      (node (ref "R161") (pin "2") (pinfunction "2_2") (pintype "passive"))
      (node (ref "R173") (pin "2") (pinfunction "2_2") (pintype "passive"))
      (node (ref "R177") (pin "2") (pinfunction "2_2") (pintype "passive"))
      (node (ref "R18") (pin "2") (pinfunction "2_2") (pintype "passive"))
      (node (ref "R199") (pin "2") (pinfunction "2_2") (pintype "passive"))
      (node (ref "R203") (pin "2") (pinfunction "2_2") (pintype "passive"))
      (node (ref "R207") (pin "2") (pinfunction "2_2") (pintype "passive"))
      (node (ref "R211") (pin "2") (pinfunction "2_2") (pintype "passive"))
      (node (ref "R22") (pin "2") (pinfunction "2_2") (pintype "passive"))
      (node (ref "R26") (pin "2") (pinfunction "2_2") (pintype "passive"))
      (node (ref "R43") (pin "2") (pinfunction "2_2") (pintype "passive"))
      (node (ref "R47") (pin "2") (pinfunction "2_2") (pintype "passive"))
      (node (ref "R51") (pin "2") (pinfunction "2_2") (pintype "passive"))
      (node (ref "R69") (pin "2") (pinfunction "2_2") (pintype "passive"))
      (node (ref "R73") (pin "2") (pinfunction "2_2") (pintype "passive"))
      (node (ref "R77") (pin "2") (pinfunction "2_2") (pintype "passive"))
      (node (ref "S1") (pin "C") (pinfunction "C_C") (pintype "bidirectional"))
      (node (ref "S10") (pin "C") (pinfunction "C_C") (pintype "bidirectional"))
      (node (ref "S11") (pin "C") (pinfunction "C_C") (pintype "bidirectional"))
      (node (ref "S12") (pin "C") (pinfunction "C_C") (pintype "bidirectional"))
      (node (ref "S13") (pin "C") (pinfunction "C_C") (pintype "bidirectional"))
      (node (ref "S14") (pin "C") (pinfunction "C_C") (pintype "bidirectional"))
      (node (ref "S15") (pin "C") (pinfunction "C_C") (pintype "bidirectional"))
      (node (ref "S16") (pin "C") (pinfunction "C_C") (pintype "bidirectional"))
      (node (ref "S17") (pin "C") (pinfunction "C_C") (pintype "bidirectional"))
      (node (ref "S18") (pin "C") (pinfunction "C_C") (pintype "bidirectional"))
      (node (ref "S19") (pin "C") (pinfunction "C_C") (pintype "bidirectional"))
      (node (ref "S2") (pin "C") (pinfunction "C_C") (pintype "bidirectional"))
      (node (ref "S20") (pin "C") (pinfunction "C_C") (pintype "bidirectional"))
      (node (ref "S21") (pin "C") (pinfunction "C_C") (pintype "bidirectional"))
      (node (ref "S22") (pin "C") (pinfunction "C_C") (pintype "bidirectional"))
      (node (ref "S23") (pin "C") (pinfunction "C_C") (pintype "bidirectional"))
      (node (ref "S3") (pin "C") (pinfunction "C_C") (pintype "bidirectional"))
      (node (ref "S4") (pin "C") (pinfunction "C_C") (pintype "bidirectional"))
      (node (ref "S5") (pin "C") (pinfunction "C_C") (pintype "bidirectional"))
      (node (ref "S6") (pin "C") (pinfunction "C_C") (pintype "bidirectional"))
      (node (ref "S7") (pin "C") (pinfunction "C_C") (pintype "bidirectional"))
      (node (ref "S8") (pin "C") (pinfunction "C_C") (pintype "bidirectional"))
      (node (ref "S9") (pin "C") (pinfunction "C_C") (pintype "bidirectional"))
      (node (ref "SW1") (pin "1") (pinfunction "1_1") (pintype "passive"))
      (node (ref "SW1") (pin "2") (pinfunction "2_2") (pintype "passive"))
      (node (ref "SW10") (pin "1") (pinfunction "1_1") (pintype "passive"))
      (node (ref "SW10") (pin "2") (pinfunction "2_2") (pintype "passive"))
      (node (ref "SW2") (pin "1") (pinfunction "1_1") (pintype "passive"))
      (node (ref "SW2") (pin "2") (pinfunction "2_2") (pintype "passive"))
      (node (ref "SW3") (pin "1") (pinfunction "1_1") (pintype "passive"))
      (node (ref "SW3") (pin "2") (pinfunction "2_2") (pintype "passive"))
      (node (ref "SW4") (pin "1") (pinfunction "1_1") (pintype "passive"))
      (node (ref "SW4") (pin "2") (pinfunction "2_2") (pintype "passive"))
      (node (ref "SW5") (pin "1") (pinfunction "1_1") (pintype "passive"))
      (node (ref "SW5") (pin "2") (pinfunction "2_2") (pintype "passive"))
      (node (ref "SW6") (pin "1") (pinfunction "1_1") (pintype "passive"))
      (node (ref "SW6") (pin "2") (pinfunction "2_2") (pintype "passive"))
      (node (ref "SW7") (pin "1") (pinfunction "1_1") (pintype "passive"))
      (node (ref "SW7") (pin "2") (pinfunction "2_2") (pintype "passive"))
      (node (ref "SW8") (pin "1") (pinfunction "1_1") (pintype "passive"))
      (node (ref "SW8") (pin "2") (pinfunction "2_2") (pintype "passive"))
      (node (ref "SW9") (pin "1") (pinfunction "1_1") (pintype "passive"))
      (node (ref "SW9") (pin "2") (pinfunction "2_2") (pintype "passive"))
    )
    (net (code "15") (name "GPA0_2") (class "Default")
      (node (ref "MCP_010") (pin "21") (pinfunction "GPA0_21") (pintype "bidirectional"))
      (node (ref "R114") (pin "1") (pinfunction "1_1") (pintype "passive"))
      (node (ref "SW5") (pin "3") (pinfunction "3_3") (pintype "passive"))
      (node (ref "SW5") (pin "4") (pinfunction "4_4") (pintype "passive"))
    )
    (net (code "16") (name "GPA0_11") (class "Default")
      (node (ref "MCP_000") (pin "21") (pinfunction "GPA0_21") (pintype "bidirectional"))
      (node (ref "R32") (pin "1") (pinfunction "1_1") (pintype "passive"))
      (node (ref "S4") (pin "B") (pinfunction "B_B") (pintype "bidirectional"))
    )
    (net (code "17") (name "GPA0_12") (class "Default")
      (node (ref "MCP_001") (pin "21") (pinfunction "GPA0_21") (pintype "bidirectional"))
      (node (ref "R58") (pin "1") (pinfunction "1_1") (pintype "passive"))
      (node (ref "S7") (pin "B") (pinfunction "B_B") (pintype "bidirectional"))
    )
    (net (code "18") (name "GPA0_31") (class "Default")
      (node (ref "MCP_011") (pin "21") (pinfunction "GPA0_21") (pintype "bidirectional"))
      (node (ref "R140") (pin "1") (pinfunction "1_1") (pintype "passive"))
      (node (ref "S17") (pin "A") (pinfunction "A_A") (pintype "bidirectional"))
    )
    (net (code "19") (name "GPA0_32") (class "Default")
      (node (ref "MCP_100") (pin "21") (pinfunction "GPA0_21") (pintype "bidirectional"))
      (node (ref "R162") (pin "1") (pinfunction "1_1") (pintype "passive"))
      (node (ref "SW9") (pin "3") (pinfunction "3_3") (pintype "passive"))
      (node (ref "SW9") (pin "4") (pinfunction "4_4") (pintype "passive"))
    )
    (net (code "20") (name "GPA1_2") (class "Default")
      (node (ref "MCP_010") (pin "22") (pinfunction "GPA1_22") (pintype "bidirectional"))
      (node (ref "R90") (pin "1") (pinfunction "1_1") (pintype "passive"))
      (node (ref "S12") (pin "A") (pinfunction "A_A") (pintype "bidirectional"))
    )
    (net (code "21") (name "GPA1_11") (class "Default")
      (node (ref "MCP_000") (pin "22") (pinfunction "GPA1_22") (pintype "bidirectional"))
      (node (ref "R31") (pin "1") (pinfunction "1_1") (pintype "passive"))
      (node (ref "S4") (pin "A") (pinfunction "A_A") (pintype "bidirectional"))
    )
    (net (code "22") (name "GPA1_12") (class "Default")
      (node (ref "MCP_001") (pin "22") (pinfunction "GPA1_22") (pintype "bidirectional"))
      (node (ref "R63") (pin "1") (pinfunction "1_1") (pintype "passive"))
      (node (ref "R69") (pin "1") (pinfunction "1_1") (pintype "passive"))
      (node (ref "S7") (pin "3") (pinfunction "SW_3") (pintype "passive"))
    )
    (net (code "23") (name "GPA1_31") (class "Default")
      (node (ref "MCP_011") (pin "22") (pinfunction "GPA1_22") (pintype "bidirectional"))
      (node (ref "R141") (pin "1") (pinfunction "1_1") (pintype "passive"))
      (node (ref "S17") (pin "B") (pinfunction "B_B") (pintype "bidirectional"))
    )
    (net (code "24") (name "GPA1_32") (class "Default")
      (node (ref "MCP_100") (pin "22") (pinfunction "GPA1_22") (pintype "bidirectional"))
      (node (ref "R192") (pin "1") (pinfunction "1_1") (pintype "passive"))
      (node (ref "R199") (pin "1") (pinfunction "1_1") (pintype "passive"))
      (node (ref "S20") (pin "3") (pinfunction "SW_3") (pintype "passive"))
    )
    (net (code "25") (name "GPA2_2") (class "Default")
      (node (ref "MCP_010") (pin "23") (pinfunction "GPA2_23") (pintype "bidirectional"))
      (node (ref "R91") (pin "1") (pinfunction "1_1") (pintype "passive"))
      (node (ref "S12") (pin "B") (pinfunction "B_B") (pintype "bidirectional"))
    )
    (net (code "26") (name "GPA2_11") (class "Default")
      (node (ref "MCP_000") (pin "23") (pinfunction "GPA2_23") (pintype "bidirectional"))
      (node (ref "R37") (pin "1") (pinfunction "1_1") (pintype "passive"))
      (node (ref "R43") (pin "1") (pinfunction "1_1") (pintype "passive"))
      (node (ref "S4") (pin "3") (pinfunction "SW_3") (pintype "passive"))
    )
    (net (code "27") (name "GPA2_12") (class "Default")
      (node (ref "MCP_001") (pin "23") (pinfunction "GPA2_23") (pintype "bidirectional"))
      (node (ref "R57") (pin "1") (pinfunction "1_1") (pintype "passive"))
      (node (ref "S7") (pin "A") (pinfunction "A_A") (pintype "bidirectional"))
    )
    (net (code "28") (name "GPA2_31") (class "Default")
      (node (ref "MCP_011") (pin "23") (pinfunction "GPA2_23") (pintype "bidirectional"))
      (node (ref "R145") (pin "1") (pinfunction "1_1") (pintype "passive"))
      (node (ref "R161") (pin "1") (pinfunction "1_1") (pintype "passive"))
      (node (ref "S17") (pin "3") (pinfunction "SW_3") (pintype "passive"))
    )
    (net (code "29") (name "GPA2_32") (class "Default")
      (node (ref "MCP_100") (pin "23") (pinfunction "GPA2_23") (pintype "bidirectional"))
      (node (ref "R185") (pin "1") (pinfunction "1_1") (pintype "passive"))
      (node (ref "S20") (pin "B") (pinfunction "B_B") (pintype "bidirectional"))
    )
    (net (code "30") (name "GPA3_2") (class "Default")
      (node (ref "MCP_010") (pin "24") (pinfunction "GPA3_24") (pintype "bidirectional"))
      (node (ref "R109") (pin "1") (pinfunction "1_1") (pintype "passive"))
      (node (ref "R96") (pin "1") (pinfunction "1_1") (pintype "passive"))
      (node (ref "S12") (pin "3") (pinfunction "SW_3") (pintype "passive"))
    )
    (net (code "31") (name "GPA3_11") (class "Default")
      (node (ref "MCP_000") (pin "24") (pinfunction "GPA3_24") (pintype "bidirectional"))
      (node (ref "R33") (pin "1") (pinfunction "1_1") (pintype "passive"))
      (node (ref "S5") (pin "A") (pinfunction "A_A") (pintype "bidirectional"))
    )
    (net (code "32") (name "GPA3_12") (class "Default")
      (node (ref "MCP_001") (pin "24") (pinfunction "GPA3_24") (pintype "bidirectional"))
      (node (ref "R60") (pin "1") (pinfunction "1_1") (pintype "passive"))
      (node (ref "S8") (pin "B") (pinfunction "B_B") (pintype "bidirectional"))
    )
    (net (code "33") (name "GPA3_31") (class "Default")
      (node (ref "MCP_011") (pin "24") (pinfunction "GPA3_24") (pintype "bidirectional"))
      (node (ref "R163") (pin "1") (pinfunction "1_1") (pintype "passive"))
      (node (ref "SW10") (pin "3") (pinfunction "3_3") (pintype "passive"))
      (node (ref "SW10") (pin "4") (pinfunction "4_4") (pintype "passive"))
    )
    (net (code "34") (name "GPA3_32") (class "Default")
      (node (ref "MCP_100") (pin "24") (pinfunction "GPA3_24") (pintype "bidirectional"))
      (node (ref "R184") (pin "1") (pinfunction "1_1") (pintype "passive"))
      (node (ref "S20") (pin "A") (pinfunction "A_A") (pintype "bidirectional"))
    )
    (net (code "35") (name "GPA4_2") (class "Default")
      (node (ref "MCP_010") (pin "25") (pinfunction "GPA4_25") (pintype "bidirectional"))
      (node (ref "R115") (pin "1") (pinfunction "1_1") (pintype "passive"))
      (node (ref "SW6") (pin "3") (pinfunction "3_3") (pintype "passive"))
      (node (ref "SW6") (pin "4") (pinfunction "4_4") (pintype "passive"))
    )
    (net (code "36") (name "GPA4_11") (class "Default")
      (node (ref "MCP_000") (pin "25") (pinfunction "GPA4_25") (pintype "bidirectional"))
      (node (ref "R34") (pin "1") (pinfunction "1_1") (pintype "passive"))
      (node (ref "S5") (pin "B") (pinfunction "B_B") (pintype "bidirectional"))
    )
    (net (code "37") (name "GPA4_12") (class "Default")
      (node (ref "MCP_001") (pin "25") (pinfunction "GPA4_25") (pintype "bidirectional"))
      (node (ref "R59") (pin "1") (pinfunction "1_1") (pintype "passive"))
      (node (ref "S8") (pin "A") (pinfunction "A_A") (pintype "bidirectional"))
    )
    (net (code "38") (name "GPA4_31") (class "Default")
      (node (ref "MCP_011") (pin "25") (pinfunction "GPA4_25") (pintype "bidirectional"))
      (node (ref "R144") (pin "1") (pinfunction "1_1") (pintype "passive"))
      (node (ref "R157") (pin "1") (pinfunction "1_1") (pintype "passive"))
      (node (ref "S16") (pin "3") (pinfunction "SW_3") (pintype "passive"))
    )
    (net (code "39") (name "GPA4_32") (class "Default")
      (node (ref "MCP_100") (pin "25") (pinfunction "GPA4_25") (pintype "bidirectional"))
      (node (ref "R193") (pin "1") (pinfunction "1_1") (pintype "passive"))
      (node (ref "R203") (pin "1") (pinfunction "1_1") (pintype "passive"))
      (node (ref "S21") (pin "3") (pinfunction "SW_3") (pintype "passive"))
    )
    (net (code "40") (name "GPA5_2") (class "Default")
      (node (ref "MCP_010") (pin "26") (pinfunction "GPA5_26") (pintype "bidirectional"))
      (node (ref "R92") (pin "1") (pinfunction "1_1") (pintype "passive"))
      (node (ref "S13") (pin "A") (pinfunction "A_A") (pintype "bidirectional"))
    )
    (net (code "41") (name "GPA5_11") (class "Default")
      (node (ref "MCP_000") (pin "26") (pinfunction "GPA5_26") (pintype "bidirectional"))
      (node (ref "R38") (pin "1") (pinfunction "1_1") (pintype "passive"))
      (node (ref "R47") (pin "1") (pinfunction "1_1") (pintype "passive"))
      (node (ref "S5") (pin "3") (pinfunction "SW_3") (pintype "passive"))
    )
    (net (code "42") (name "GPA5_12") (class "Default")
      (node (ref "MCP_001") (pin "26") (pinfunction "GPA5_26") (pintype "bidirectional"))
      (node (ref "R64") (pin "1") (pinfunction "1_1") (pintype "passive"))
      (node (ref "R73") (pin "1") (pinfunction "1_1") (pintype "passive"))
      (node (ref "S8") (pin "3") (pinfunction "SW_3") (pintype "passive"))
    )
    (net (code "43") (name "GPA5_31") (class "Default")
      (node (ref "MCP_011") (pin "26") (pinfunction "GPA5_26") (pintype "bidirectional"))
      (node (ref "R138") (pin "1") (pinfunction "1_1") (pintype "passive"))
      (node (ref "S16") (pin "A") (pinfunction "A_A") (pintype "bidirectional"))
    )
    (net (code "44") (name "GPA5_32") (class "Default")
      (node (ref "MCP_100") (pin "26") (pinfunction "GPA5_26") (pintype "bidirectional"))
      (node (ref "R187") (pin "1") (pinfunction "1_1") (pintype "passive"))
      (node (ref "S21") (pin "B") (pinfunction "B_B") (pintype "bidirectional"))
    )
    (net (code "45") (name "GPA6_2") (class "Default")
      (node (ref "MCP_010") (pin "27") (pinfunction "GPA6_27") (pintype "bidirectional"))
      (node (ref "R113") (pin "1") (pinfunction "1_1") (pintype "passive"))
      (node (ref "R97") (pin "1") (pinfunction "1_1") (pintype "passive"))
      (node (ref "S13") (pin "3") (pinfunction "SW_3") (pintype "passive"))
    )
    (net (code "46") (name "GPA6_11") (class "Default")
      (node (ref "MCP_000") (pin "27") (pinfunction "GPA6_27") (pintype "bidirectional"))
      (node (ref "R14") (pin "1") (pinfunction "1_1") (pintype "passive"))
      (node (ref "R26") (pin "1") (pinfunction "1_1") (pintype "passive"))
      (node (ref "S3") (pin "3") (pinfunction "SW_3") (pintype "passive"))
    )
    (net (code "47") (name "GPA6_12") (class "Default")
      (node (ref "MCP_001") (pin "27") (pinfunction "GPA6_27") (pintype "bidirectional"))
      (node (ref "R55") (pin "1") (pinfunction "1_1") (pintype "passive"))
      (node (ref "SW3") (pin "3") (pinfunction "3_3") (pintype "passive"))
      (node (ref "SW3") (pin "4") (pinfunction "4_4") (pintype "passive"))
    )
    (net (code "48") (name "GPA6_31") (class "Default")
      (node (ref "MCP_011") (pin "27") (pinfunction "GPA6_27") (pintype "bidirectional"))
      (node (ref "R139") (pin "1") (pinfunction "1_1") (pintype "passive"))
      (node (ref "S16") (pin "B") (pinfunction "B_B") (pintype "bidirectional"))
    )
    (net (code "49") (name "GPA6_32") (class "Default")
      (node (ref "MCP_100") (pin "27") (pinfunction "GPA6_27") (pintype "bidirectional"))
      (node (ref "R186") (pin "1") (pinfunction "1_1") (pintype "passive"))
      (node (ref "S21") (pin "A") (pinfunction "A_A") (pintype "bidirectional"))
    )
    (net (code "50") (name "GPA7_2") (class "Default")
      (node (ref "MCP_010") (pin "28") (pinfunction "GPA7_28") (pintype "bidirectional"))
      (node (ref "R93") (pin "1") (pinfunction "1_1") (pintype "passive"))
      (node (ref "S13") (pin "B") (pinfunction "B_B") (pintype "bidirectional"))
    )
    (net (code "51") (name "GPA7_11") (class "Default")
      (node (ref "MCP_000") (pin "28") (pinfunction "GPA7_28") (pintype "bidirectional"))
      (node (ref "R5") (pin "1") (pinfunction "1_1") (pintype "passive"))
      (node (ref "SW1") (pin "3") (pinfunction "3_3") (pintype "passive"))
      (node (ref "SW1") (pin "4") (pinfunction "4_4") (pintype "passive"))
    )
    (net (code "52") (name "GPA7_12") (class "Default")
      (node (ref "MCP_001") (pin "28") (pinfunction "GPA7_28") (pintype "bidirectional"))
      (node (ref "R56") (pin "1") (pinfunction "1_1") (pintype "passive"))
      (node (ref "SW4") (pin "3") (pinfunction "3_3") (pintype "passive"))
      (node (ref "SW4") (pin "4") (pinfunction "4_4") (pintype "passive"))
    )
    (net (code "53") (name "GPA7_31") (class "Default")
      (node (ref "MCP_011") (pin "28") (pinfunction "GPA7_28") (pintype "bidirectional"))
      (node (ref "R168") (pin "1") (pinfunction "1_1") (pintype "passive"))
      (node (ref "R173") (pin "1") (pinfunction "1_1") (pintype "passive"))
      (node (ref "S18") (pin "3") (pinfunction "SW_3") (pintype "passive"))
    )
    (net (code "54") (name "GPA7_32") (class "Default")
      (node (ref "MCP_100") (pin "28") (pinfunction "GPA7_28") (pintype "bidirectional"))
      (node (ref "R194") (pin "1") (pinfunction "1_1") (pintype "passive"))
      (node (ref "R207") (pin "1") (pinfunction "1_1") (pintype "passive"))
      (node (ref "S22") (pin "3") (pinfunction "SW_3") (pintype "passive"))
    )
    (net (code "55") (name "GPB0_2") (class "Default")
      (node (ref "MCP_010") (pin "1") (pinfunction "GPB0_1") (pintype "bidirectional"))
      (node (ref "R117") (pin "1") (pinfunction "1_1") (pintype "passive"))
      (node (ref "SW8") (pin "3") (pinfunction "3_3") (pintype "passive"))
      (node (ref "SW8") (pin "4") (pinfunction "4_4") (pintype "passive"))
    )
    (net (code "56") (name "GPB0_11") (class "Default")
      (node (ref "MCP_000") (pin "1") (pinfunction "GPB0_1") (pintype "bidirectional"))
      (node (ref "R10") (pin "1") (pinfunction "1_1") (pintype "passive"))
      (node (ref "S3") (pin "A") (pinfunction "A_A") (pintype "bidirectional"))
    )
    (net (code "57") (name "GPB0_31") (class "Default")
      (node (ref "MCP_011") (pin "1") (pinfunction "GPB0_1") (pintype "bidirectional"))
      (node (ref "R165") (pin "1") (pinfunction "1_1") (pintype "passive"))
      (node (ref "S18") (pin "B") (pinfunction "B_B") (pintype "bidirectional"))
    )
    (net (code "58") (name "GPB0_32") (class "Default")
      (node (ref "MCP_100") (pin "1") (pinfunction "GPB0_1") (pintype "bidirectional"))
      (node (ref "R189") (pin "1") (pinfunction "1_1") (pintype "passive"))
      (node (ref "S22") (pin "B") (pinfunction "B_B") (pintype "bidirectional"))
    )
    (net (code "59") (name "GPB1_2") (class "Default")
      (node (ref "MCP_010") (pin "2") (pinfunction "GPB1_2") (pintype "bidirectional"))
      (node (ref "R88") (pin "1") (pinfunction "1_1") (pintype "passive"))
      (node (ref "S11") (pin "A") (pinfunction "A_A") (pintype "bidirectional"))
    )
    (net (code "60") (name "GPB1_11") (class "Default")
      (node (ref "MCP_000") (pin "2") (pinfunction "GPB1_2") (pintype "bidirectional"))
      (node (ref "R11") (pin "1") (pinfunction "1_1") (pintype "passive"))
      (node (ref "S3") (pin "B") (pinfunction "B_B") (pintype "bidirectional"))
    )
    (net (code "61") (name "GPB1_12") (class "Default")
      (node (ref "MCP_001") (pin "2") (pinfunction "GPB1_2") (pintype "bidirectional"))
      (node (ref "R62") (pin "1") (pinfunction "1_1") (pintype "passive"))
      (node (ref "S9") (pin "B") (pinfunction "B_B") (pintype "bidirectional"))
    )
    (net (code "62") (name "GPB1_31") (class "Default")
      (node (ref "MCP_011") (pin "2") (pinfunction "GPB1_2") (pintype "bidirectional"))
      (node (ref "R164") (pin "1") (pinfunction "1_1") (pintype "passive"))
      (node (ref "S18") (pin "A") (pinfunction "A_A") (pintype "bidirectional"))
    )
    (net (code "63") (name "GPB1_32") (class "Default")
      (node (ref "MCP_100") (pin "2") (pinfunction "GPB1_2") (pintype "bidirectional"))
      (node (ref "R188") (pin "1") (pinfunction "1_1") (pintype "passive"))
      (node (ref "S22") (pin "A") (pinfunction "A_A") (pintype "bidirectional"))
    )
    (net (code "64") (name "GPB2_2") (class "Default")
      (node (ref "MCP_010") (pin "3") (pinfunction "GPB2_3") (pintype "bidirectional"))
      (node (ref "R89") (pin "1") (pinfunction "1_1") (pintype "passive"))
      (node (ref "S11") (pin "B") (pinfunction "B_B") (pintype "bidirectional"))
    )
    (net (code "65") (name "GPB2_11") (class "Default")
      (node (ref "MCP_000") (pin "3") (pinfunction "GPB2_3") (pintype "bidirectional"))
      (node (ref "R8") (pin "1") (pinfunction "1_1") (pintype "passive"))
      (node (ref "S2") (pin "A") (pinfunction "A_A") (pintype "bidirectional"))
    )
    (net (code "66") (name "GPB2_12") (class "Default")
      (node (ref "MCP_001") (pin "3") (pinfunction "GPB2_3") (pintype "bidirectional"))
      (node (ref "R65") (pin "1") (pinfunction "1_1") (pintype "passive"))
      (node (ref "R77") (pin "1") (pinfunction "1_1") (pintype "passive"))
      (node (ref "S9") (pin "3") (pinfunction "SW_3") (pintype "passive"))
    )
    (net (code "67") (name "GPB2_31") (class "Default")
      (node (ref "MCP_011") (pin "3") (pinfunction "GPB2_3") (pintype "bidirectional"))
      (node (ref "R169") (pin "1") (pinfunction "1_1") (pintype "passive"))
      (node (ref "R177") (pin "1") (pinfunction "1_1") (pintype "passive"))
      (node (ref "S19") (pin "3") (pinfunction "SW_3") (pintype "passive"))
    )
    (net (code "68") (name "GPB2_32") (class "Default")
      (node (ref "MCP_100") (pin "3") (pinfunction "GPB2_3") (pintype "bidirectional"))
      (node (ref "R191") (pin "1") (pinfunction "1_1") (pintype "passive"))
      (node (ref "S23") (pin "B") (pinfunction "B_B") (pintype "bidirectional"))
    )
    (net (code "69") (name "GPB3_2") (class "Default")
      (node (ref "MCP_010") (pin "4") (pinfunction "GPB3_4") (pintype "bidirectional"))
      (node (ref "R105") (pin "1") (pinfunction "1_1") (pintype "passive"))
      (node (ref "R95") (pin "1") (pinfunction "1_1") (pintype "passive"))
      (node (ref "S11") (pin "3") (pinfunction "SW_3") (pintype "passive"))
    )
    (net (code "70") (name "GPB3_11") (class "Default")
      (node (ref "MCP_000") (pin "4") (pinfunction "GPB3_4") (pintype "bidirectional"))
      (node (ref "R9") (pin "1") (pinfunction "1_1") (pintype "passive"))
      (node (ref "S2") (pin "B") (pinfunction "B_B") (pintype "bidirectional"))
    )
    (net (code "71") (name "GPB3_12") (class "Default")
      (node (ref "MCP_001") (pin "4") (pinfunction "GPB3_4") (pintype "bidirectional"))
      (node (ref "R61") (pin "1") (pinfunction "1_1") (pintype "passive"))
      (node (ref "S9") (pin "A") (pinfunction "A_A") (pintype "bidirectional"))
    )
    (net (code "72") (name "GPB3_31") (class "Default")
      (node (ref "MCP_011") (pin "4") (pinfunction "GPB3_4") (pintype "bidirectional"))
      (node (ref "R167") (pin "1") (pinfunction "1_1") (pintype "passive"))
      (node (ref "S19") (pin "B") (pinfunction "B_B") (pintype "bidirectional"))
    )
    (net (code "73") (name "GPB3_32") (class "Default")
      (node (ref "MCP_100") (pin "4") (pinfunction "GPB3_4") (pintype "bidirectional"))
      (node (ref "R190") (pin "1") (pinfunction "1_1") (pintype "passive"))
      (node (ref "S23") (pin "A") (pinfunction "A_A") (pintype "bidirectional"))
    )
    (net (code "74") (name "GPB4_2") (class "Default")
      (node (ref "MCP_010") (pin "5") (pinfunction "GPB4_5") (pintype "bidirectional"))
      (node (ref "R86") (pin "1") (pinfunction "1_1") (pintype "passive"))
      (node (ref "S10") (pin "A") (pinfunction "A_A") (pintype "bidirectional"))
    )
    (net (code "75") (name "GPB4_11") (class "Default")
      (node (ref "MCP_000") (pin "5") (pinfunction "GPB4_5") (pintype "bidirectional"))
      (node (ref "R13") (pin "1") (pinfunction "1_1") (pintype "passive"))
      (node (ref "R22") (pin "1") (pinfunction "1_1") (pintype "passive"))
      (node (ref "S2") (pin "3") (pinfunction "SW_3") (pintype "passive"))
    )
    (net (code "76") (name "GPB4_12") (class "Default")
      (node (ref "MCP_001") (pin "5") (pinfunction "GPB4_5") (pintype "bidirectional"))
      (node (ref "R39") (pin "1") (pinfunction "1_1") (pintype "passive"))
      (node (ref "R51") (pin "1") (pinfunction "1_1") (pintype "passive"))
      (node (ref "S6") (pin "3") (pinfunction "SW_3") (pintype "passive"))
    )
    (net (code "77") (name "GPB4_31") (class "Default")
      (node (ref "MCP_011") (pin "5") (pinfunction "GPB4_5") (pintype "bidirectional"))
      (node (ref "R166") (pin "1") (pinfunction "1_1") (pintype "passive"))
      (node (ref "S19") (pin "A") (pinfunction "A_A") (pintype "bidirectional"))
    )
    (net (code "78") (name "GPB4_32") (class "Default")
      (node (ref "MCP_100") (pin "5") (pinfunction "GPB4_5") (pintype "bidirectional"))
      (node (ref "R195") (pin "1") (pinfunction "1_1") (pintype "passive"))
      (node (ref "R211") (pin "1") (pinfunction "1_1") (pintype "passive"))
      (node (ref "S23") (pin "3") (pinfunction "SW_3") (pintype "passive"))
    )
    (net (code "79") (name "GPB5_2") (class "Default")
      (node (ref "MCP_010") (pin "6") (pinfunction "GPB5_6") (pintype "bidirectional"))
      (node (ref "R87") (pin "1") (pinfunction "1_1") (pintype "passive"))
      (node (ref "S10") (pin "B") (pinfunction "B_B") (pintype "bidirectional"))
    )
    (net (code "80") (name "GPB5_11") (class "Default")
      (node (ref "MCP_000") (pin "6") (pinfunction "GPB5_6") (pintype "bidirectional"))
      (node (ref "R12") (pin "1") (pinfunction "1_1") (pintype "passive"))
      (node (ref "R18") (pin "1") (pinfunction "1_1") (pintype "passive"))
      (node (ref "S1") (pin "3") (pinfunction "SW_3") (pintype "passive"))
    )
    (net (code "81") (name "GPB5_12") (class "Default")
      (node (ref "MCP_001") (pin "6") (pinfunction "GPB5_6") (pintype "bidirectional"))
      (node (ref "R35") (pin "1") (pinfunction "1_1") (pintype "passive"))
      (node (ref "S6") (pin "A") (pinfunction "A_A") (pintype "bidirectional"))
    )
    (net (code "82") (name "GPB5_31") (class "Default")
      (node (ref "MCP_011") (pin "6") (pinfunction "GPB5_6") (pintype "bidirectional"))
      (node (ref "R134") (pin "1") (pinfunction "1_1") (pintype "passive"))
      (node (ref "S14") (pin "A") (pinfunction "A_A") (pintype "bidirectional"))
    )
    (net (code "83") (name "GPB5_32") (class "Default")
      (node (ref "MCP_100") (pin "6") (pinfunction "GPB5_6") (pintype "bidirectional"))
      (node (ref "R136") (pin "1") (pinfunction "1_1") (pintype "passive"))
      (node (ref "S15") (pin "A") (pinfunction "A_A") (pintype "bidirectional"))
    )
    (net (code "84") (name "GPB6_2") (class "Default")
      (node (ref "MCP_010") (pin "7") (pinfunction "GPB6_7") (pintype "bidirectional"))
      (node (ref "R101") (pin "1") (pinfunction "1_1") (pintype "passive"))
      (node (ref "R94") (pin "1") (pinfunction "1_1") (pintype "passive"))
      (node (ref "S10") (pin "3") (pinfunction "SW_3") (pintype "passive"))
    )
    (net (code "85") (name "GPB6_11") (class "Default")
      (node (ref "MCP_000") (pin "7") (pinfunction "GPB6_7") (pintype "bidirectional"))
      (node (ref "R6") (pin "1") (pinfunction "1_1") (pintype "passive"))
      (node (ref "S1") (pin "A") (pinfunction "A_A") (pintype "bidirectional"))
    )
    (net (code "86") (name "GPB6_12") (class "Default")
      (node (ref "MCP_001") (pin "7") (pinfunction "GPB6_7") (pintype "bidirectional"))
      (node (ref "R36") (pin "1") (pinfunction "1_1") (pintype "passive"))
      (node (ref "S6") (pin "B") (pinfunction "B_B") (pintype "bidirectional"))
    )
    (net (code "87") (name "GPB6_31") (class "Default")
      (node (ref "MCP_011") (pin "7") (pinfunction "GPB6_7") (pintype "bidirectional"))
      (node (ref "R135") (pin "1") (pinfunction "1_1") (pintype "passive"))
      (node (ref "S14") (pin "B") (pinfunction "B_B") (pintype "bidirectional"))
    )
    (net (code "88") (name "GPB6_32") (class "Default")
      (node (ref "MCP_100") (pin "7") (pinfunction "GPB6_7") (pintype "bidirectional"))
      (node (ref "R137") (pin "1") (pinfunction "1_1") (pintype "passive"))
      (node (ref "S15") (pin "B") (pinfunction "B_B") (pintype "bidirectional"))
    )
    (net (code "89") (name "GPB7_2") (class "Default")
      (node (ref "MCP_010") (pin "8") (pinfunction "GPB7_8") (pintype "bidirectional"))
      (node (ref "R116") (pin "1") (pinfunction "1_1") (pintype "passive"))
      (node (ref "SW7") (pin "3") (pinfunction "3_3") (pintype "passive"))
      (node (ref "SW7") (pin "4") (pinfunction "4_4") (pintype "passive"))
    )
    (net (code "90") (name "GPB7_11") (class "Default")
      (node (ref "MCP_000") (pin "8") (pinfunction "GPB7_8") (pintype "bidirectional"))
      (node (ref "R7") (pin "1") (pinfunction "1_1") (pintype "passive"))
      (node (ref "S1") (pin "B") (pinfunction "B_B") (pintype "bidirectional"))
    )
    (net (code "91") (name "GPB7_12") (class "Default")
      (node (ref "MCP_001") (pin "8") (pinfunction "GPB7_8") (pintype "bidirectional"))
      (node (ref "R30") (pin "1") (pinfunction "1_1") (pintype "passive"))
      (node (ref "SW2") (pin "3") (pinfunction "3_3") (pintype "passive"))
      (node (ref "SW2") (pin "4") (pinfunction "4_4") (pintype "passive"))
    )
    (net (code "92") (name "GPB7_31") (class "Default")
      (node (ref "MCP_011") (pin "8") (pinfunction "GPB7_8") (pintype "bidirectional"))
      (node (ref "R142") (pin "1") (pinfunction "1_1") (pintype "passive"))
      (node (ref "R149") (pin "1") (pinfunction "1_1") (pintype "passive"))
      (node (ref "S14") (pin "3") (pinfunction "SW_3") (pintype "passive"))
    )
    (net (code "93") (name "GPB7_32") (class "Default")
      (node (ref "MCP_100") (pin "8") (pinfunction "GPB7_8") (pintype "bidirectional"))
      (node (ref "R143") (pin "1") (pinfunction "1_1") (pintype "passive"))
      (node (ref "R153") (pin "1") (pinfunction "1_1") (pintype "passive"))
      (node (ref "S15") (pin "3") (pinfunction "SW_3") (pintype "passive"))
    )
    (net (code "94") (name "I2C2_SCL") (class "Default")
      (node (ref "CON_NORTH_BRD") (pin "20") (pinfunction "20_20") (pintype "passive"))
      (node (ref "MCP_010") (pin "12") (pinfunction "SCL_12") (pintype "bidirectional"))
      (node (ref "MCP_011") (pin "12") (pinfunction "SCL_12") (pintype "bidirectional"))
      (node (ref "MCP_100") (pin "12") (pinfunction "SCL_12") (pintype "bidirectional"))
      (node (ref "R132") (pin "1") (pinfunction "1_1") (pintype "passive"))
      (node (ref "R133") (pin "1") (pinfunction "1_1") (pintype "passive"))
      (node (ref "R85") (pin "1") (pinfunction "1_1") (pintype "passive"))
    )
    (net (code "95") (name "I2C2_SDA") (class "Default")
      (node (ref "CON_NORTH_BRD") (pin "5") (pinfunction "5_5") (pintype "passive"))
      (node (ref "MCP_010") (pin "13") (pinfunction "SDA_13") (pintype "bidirectional"))
      (node (ref "MCP_011") (pin "13") (pinfunction "SDA_13") (pintype "bidirectional"))
      (node (ref "MCP_100") (pin "13") (pinfunction "SDA_13") (pintype "bidirectional"))
      (node (ref "R130") (pin "1") (pinfunction "1_1") (pintype "passive"))
      (node (ref "R131") (pin "1") (pinfunction "1_1") (pintype "passive"))
      (node (ref "R84") (pin "1") (pinfunction "1_1") (pintype "passive"))
    )
    (net (code "96") (name "I2C3_SCL") (class "Default")
      (node (ref "CON_NORTH_BRD") (pin "12") (pinfunction "12_12") (pintype "passive"))
      (node (ref "MCP_000") (pin "12") (pinfunction "SCL_12") (pintype "bidirectional"))
      (node (ref "MCP_001") (pin "12") (pinfunction "SCL_12") (pintype "bidirectional"))
      (node (ref "R2") (pin "1") (pinfunction "1_1") (pintype "passive"))
      (node (ref "R4") (pin "1") (pinfunction "1_1") (pintype "passive"))
    )
    (net (code "97") (name "I2C3_SDA") (class "Default")
      (node (ref "CON_NORTH_BRD") (pin "11") (pinfunction "11_11") (pintype "passive"))
      (node (ref "MCP_000") (pin "13") (pinfunction "SDA_13") (pintype "bidirectional"))
      (node (ref "MCP_001") (pin "13") (pinfunction "SDA_13") (pintype "bidirectional"))
      (node (ref "R1") (pin "1") (pinfunction "1_1") (pintype "passive"))
      (node (ref "R3") (pin "1") (pinfunction "1_1") (pintype "passive"))
    )
    (net (code "98") (name "INTA_2") (class "Default")
      (node (ref "CON_NORTH_BRD") (pin "13") (pinfunction "13_13") (pintype "passive"))
      (node (ref "MCP_010") (pin "20") (pinfunction "INTA_20") (pintype "bidirectional"))
    )
    (net (code "99") (name "INTA_11") (class "Default")
      (node (ref "CON_NORTH_BRD") (pin "8") (pinfunction "8_8") (pintype "passive"))
      (node (ref "MCP_000") (pin "20") (pinfunction "INTA_20") (pintype "bidirectional"))
    )
    (net (code "100") (name "INTA_12") (class "Default")
      (node (ref "CON_NORTH_BRD") (pin "9") (pinfunction "9_9") (pintype "passive"))
      (node (ref "MCP_001") (pin "20") (pinfunction "INTA_20") (pintype "bidirectional"))
    )
    (net (code "101") (name "INTA_31") (class "Default")
      (node (ref "CON_NORTH_BRD") (pin "18") (pinfunction "18_18") (pintype "passive"))
      (node (ref "MCP_011") (pin "20") (pinfunction "INTA_20") (pintype "bidirectional"))
    )
    (net (code "102") (name "INTA_32") (class "Default")
      (node (ref "CON_NORTH_BRD") (pin "15") (pinfunction "15_15") (pintype "passive"))
      (node (ref "MCP_100") (pin "20") (pinfunction "INTA_20") (pintype "bidirectional"))
    )
    (net (code "103") (name "INTB_2") (class "Default")
      (node (ref "CON_NORTH_BRD") (pin "14") (pinfunction "14_14") (pintype "passive"))
      (node (ref "MCP_010") (pin "19") (pinfunction "INTB_19") (pintype "bidirectional"))
    )
    (net (code "104") (name "INTB_11") (class "Default")
      (node (ref "CON_NORTH_BRD") (pin "7") (pinfunction "7_7") (pintype "passive"))
      (node (ref "MCP_000") (pin "19") (pinfunction "INTB_19") (pintype "bidirectional"))
    )
    (net (code "105") (name "INTB_12") (class "Default")
      (node (ref "CON_NORTH_BRD") (pin "10") (pinfunction "10_10") (pintype "passive"))
      (node (ref "MCP_001") (pin "19") (pinfunction "INTB_19") (pintype "bidirectional"))
    )
    (net (code "106") (name "INTB_31") (class "Default")
      (node (ref "CON_NORTH_BRD") (pin "17") (pinfunction "17_17") (pintype "passive"))
      (node (ref "MCP_011") (pin "19") (pinfunction "INTB_19") (pintype "bidirectional"))
    )
    (net (code "107") (name "INTB_32") (class "Default")
      (node (ref "CON_NORTH_BRD") (pin "16") (pinfunction "16_16") (pintype "passive"))
      (node (ref "MCP_100") (pin "19") (pinfunction "INTB_19") (pintype "bidirectional"))
    )
    (net (code "108") (name "Net-(C5-Pad2)") (class "Default")
      (node (ref "C5") (pin "2") (pinfunction "2_2") (pintype "passive"))
      (node (ref "R5") (pin "2") (pinfunction "2_2") (pintype "passive"))
    )
    (net (code "109") (name "Net-(C6-Pad2)") (class "Default")
      (node (ref "C6") (pin "2") (pinfunction "2_2") (pintype "passive"))
      (node (ref "R6") (pin "2") (pinfunction "2_2") (pintype "passive"))
    )
    (net (code "110") (name "Net-(C7-Pad2)") (class "Default")
      (node (ref "C7") (pin "2") (pinfunction "2_2") (pintype "passive"))
      (node (ref "R7") (pin "2") (pinfunction "2_2") (pintype "passive"))
    )
    (net (code "111") (name "Net-(C8-Pad2)") (class "Default")
      (node (ref "C8") (pin "2") (pinfunction "2_2") (pintype "passive"))
      (node (ref "R8") (pin "2") (pinfunction "2_2") (pintype "passive"))
    )
    (net (code "112") (name "Net-(C9-Pad2)") (class "Default")
      (node (ref "C9") (pin "2") (pinfunction "2_2") (pintype "passive"))
      (node (ref "R9") (pin "2") (pinfunction "2_2") (pintype "passive"))
    )
    (net (code "113") (name "Net-(C10-Pad2)") (class "Default")
      (node (ref "C10") (pin "2") (pinfunction "2_2") (pintype "passive"))
      (node (ref "R10") (pin "2") (pinfunction "2_2") (pintype "passive"))
    )
    (net (code "114") (name "Net-(C11-Pad2)") (class "Default")
      (node (ref "C11") (pin "2") (pinfunction "2_2") (pintype "passive"))
      (node (ref "R11") (pin "2") (pinfunction "2_2") (pintype "passive"))
    )
    (net (code "115") (name "Net-(C12-Pad1)") (class "Default")
      (node (ref "C12") (pin "1") (pinfunction "1_1") (pintype "passive"))
      (node (ref "R12") (pin "2") (pinfunction "2_2") (pintype "passive"))
    )
    (net (code "116") (name "Net-(C13-Pad1)") (class "Default")
      (node (ref "C13") (pin "1") (pinfunction "1_1") (pintype "passive"))
      (node (ref "R13") (pin "2") (pinfunction "2_2") (pintype "passive"))
    )
    (net (code "117") (name "Net-(C14-Pad1)") (class "Default")
      (node (ref "C14") (pin "1") (pinfunction "1_1") (pintype "passive"))
      (node (ref "R14") (pin "2") (pinfunction "2_2") (pintype "passive"))
    )
    (net (code "118") (name "Net-(C20-Pad2)") (class "Default")
      (node (ref "C20") (pin "2") (pinfunction "2_2") (pintype "passive"))
      (node (ref "R30") (pin "2") (pinfunction "2_2") (pintype "passive"))
    )
    (net (code "119") (name "Net-(C21-Pad2)") (class "Default")
      (node (ref "C21") (pin "2") (pinfunction "2_2") (pintype "passive"))
      (node (ref "R31") (pin "2") (pinfunction "2_2") (pintype "passive"))
    )
    (net (code "120") (name "Net-(C22-Pad2)") (class "Default")
      (node (ref "C22") (pin "2") (pinfunction "2_2") (pintype "passive"))
      (node (ref "R32") (pin "2") (pinfunction "2_2") (pintype "passive"))
    )
    (net (code "121") (name "Net-(C23-Pad2)") (class "Default")
      (node (ref "C23") (pin "2") (pinfunction "2_2") (pintype "passive"))
      (node (ref "R33") (pin "2") (pinfunction "2_2") (pintype "passive"))
    )
    (net (code "122") (name "Net-(C24-Pad2)") (class "Default")
      (node (ref "C24") (pin "2") (pinfunction "2_2") (pintype "passive"))
      (node (ref "R34") (pin "2") (pinfunction "2_2") (pintype "passive"))
    )
    (net (code "123") (name "Net-(C25-Pad2)") (class "Default")
      (node (ref "C25") (pin "2") (pinfunction "2_2") (pintype "passive"))
      (node (ref "R35") (pin "2") (pinfunction "2_2") (pintype "passive"))
    )
    (net (code "124") (name "Net-(C26-Pad2)") (class "Default")
      (node (ref "C26") (pin "2") (pinfunction "2_2") (pintype "passive"))
      (node (ref "R36") (pin "2") (pinfunction "2_2") (pintype "passive"))
    )
    (net (code "125") (name "Net-(C27-Pad1)") (class "Default")
      (node (ref "C27") (pin "1") (pinfunction "1_1") (pintype "passive"))
      (node (ref "R37") (pin "2") (pinfunction "2_2") (pintype "passive"))
    )
    (net (code "126") (name "Net-(C28-Pad1)") (class "Default")
      (node (ref "C28") (pin "1") (pinfunction "1_1") (pintype "passive"))
      (node (ref "R38") (pin "2") (pinfunction "2_2") (pintype "passive"))
    )
    (net (code "127") (name "Net-(C29-Pad1)") (class "Default")
      (node (ref "C29") (pin "1") (pinfunction "1_1") (pintype "passive"))
      (node (ref "R39") (pin "2") (pinfunction "2_2") (pintype "passive"))
    )
    (net (code "128") (name "Net-(C34-Pad2)") (class "Default")
      (node (ref "C34") (pin "2") (pinfunction "2_2") (pintype "passive"))
      (node (ref "R55") (pin "2") (pinfunction "2_2") (pintype "passive"))
    )
    (net (code "129") (name "Net-(C35-Pad2)") (class "Default")
      (node (ref "C35") (pin "2") (pinfunction "2_2") (pintype "passive"))
      (node (ref "R56") (pin "2") (pinfunction "2_2") (pintype "passive"))
    )
    (net (code "130") (name "Net-(C36-Pad2)") (class "Default")
      (node (ref "C36") (pin "2") (pinfunction "2_2") (pintype "passive"))
      (node (ref "R57") (pin "2") (pinfunction "2_2") (pintype "passive"))
    )
    (net (code "131") (name "Net-(C37-Pad2)") (class "Default")
      (node (ref "C37") (pin "2") (pinfunction "2_2") (pintype "passive"))
      (node (ref "R58") (pin "2") (pinfunction "2_2") (pintype "passive"))
    )
    (net (code "132") (name "Net-(C38-Pad2)") (class "Default")
      (node (ref "C38") (pin "2") (pinfunction "2_2") (pintype "passive"))
      (node (ref "R59") (pin "2") (pinfunction "2_2") (pintype "passive"))
    )
    (net (code "133") (name "Net-(C39-Pad2)") (class "Default")
      (node (ref "C39") (pin "2") (pinfunction "2_2") (pintype "passive"))
      (node (ref "R60") (pin "2") (pinfunction "2_2") (pintype "passive"))
    )
    (net (code "134") (name "Net-(C40-Pad2)") (class "Default")
      (node (ref "C40") (pin "2") (pinfunction "2_2") (pintype "passive"))
      (node (ref "R61") (pin "2") (pinfunction "2_2") (pintype "passive"))
    )
    (net (code "135") (name "Net-(C41-Pad2)") (class "Default")
      (node (ref "C41") (pin "2") (pinfunction "2_2") (pintype "passive"))
      (node (ref "R62") (pin "2") (pinfunction "2_2") (pintype "passive"))
    )
    (net (code "136") (name "Net-(C42-Pad1)") (class "Default")
      (node (ref "C42") (pin "1") (pinfunction "1_1") (pintype "passive"))
      (node (ref "R63") (pin "2") (pinfunction "2_2") (pintype "passive"))
    )
    (net (code "137") (name "Net-(C43-Pad1)") (class "Default")
      (node (ref "C43") (pin "1") (pinfunction "1_1") (pintype "passive"))
      (node (ref "R64") (pin "2") (pinfunction "2_2") (pintype "passive"))
    )
    (net (code "138") (name "Net-(C44-Pad1)") (class "Default")
      (node (ref "C44") (pin "1") (pinfunction "1_1") (pintype "passive"))
      (node (ref "R65") (pin "2") (pinfunction "2_2") (pintype "passive"))
    )
    (net (code "139") (name "Net-(C55-Pad2)") (class "Default")
      (node (ref "C55") (pin "2") (pinfunction "2_2") (pintype "passive"))
      (node (ref "R86") (pin "2") (pinfunction "2_2") (pintype "passive"))
    )
    (net (code "140") (name "Net-(C56-Pad2)") (class "Default")
      (node (ref "C56") (pin "2") (pinfunction "2_2") (pintype "passive"))
      (node (ref "R87") (pin "2") (pinfunction "2_2") (pintype "passive"))
    )
    (net (code "141") (name "Net-(C57-Pad2)") (class "Default")
      (node (ref "C57") (pin "2") (pinfunction "2_2") (pintype "passive"))
      (node (ref "R88") (pin "2") (pinfunction "2_2") (pintype "passive"))
    )
    (net (code "142") (name "Net-(C58-Pad2)") (class "Default")
      (node (ref "C58") (pin "2") (pinfunction "2_2") (pintype "passive"))
      (node (ref "R89") (pin "2") (pinfunction "2_2") (pintype "passive"))
    )
    (net (code "143") (name "Net-(C59-Pad2)") (class "Default")
      (node (ref "C59") (pin "2") (pinfunction "2_2") (pintype "passive"))
      (node (ref "R90") (pin "2") (pinfunction "2_2") (pintype "passive"))
    )
    (net (code "144") (name "Net-(C60-Pad2)") (class "Default")
      (node (ref "C60") (pin "2") (pinfunction "2_2") (pintype "passive"))
      (node (ref "R91") (pin "2") (pinfunction "2_2") (pintype "passive"))
    )
    (net (code "145") (name "Net-(C61-Pad2)") (class "Default")
      (node (ref "C61") (pin "2") (pinfunction "2_2") (pintype "passive"))
      (node (ref "R92") (pin "2") (pinfunction "2_2") (pintype "passive"))
    )
    (net (code "146") (name "Net-(C62-Pad2)") (class "Default")
      (node (ref "C62") (pin "2") (pinfunction "2_2") (pintype "passive"))
      (node (ref "R93") (pin "2") (pinfunction "2_2") (pintype "passive"))
    )
    (net (code "147") (name "Net-(C67-Pad1)") (class "Default")
      (node (ref "C67") (pin "1") (pinfunction "1_1") (pintype "passive"))
      (node (ref "R94") (pin "2") (pinfunction "2_2") (pintype "passive"))
    )
    (net (code "148") (name "Net-(C68-Pad1)") (class "Default")
      (node (ref "C68") (pin "1") (pinfunction "1_1") (pintype "passive"))
      (node (ref "R95") (pin "2") (pinfunction "2_2") (pintype "passive"))
    )
    (net (code "149") (name "Net-(C69-Pad1)") (class "Default")
      (node (ref "C69") (pin "1") (pinfunction "1_1") (pintype "passive"))
      (node (ref "R96") (pin "2") (pinfunction "2_2") (pintype "passive"))
    )
    (net (code "150") (name "Net-(C70-Pad1)") (class "Default")
      (node (ref "C70") (pin "1") (pinfunction "1_1") (pintype "passive"))
      (node (ref "R97") (pin "2") (pinfunction "2_2") (pintype "passive"))
    )
    (net (code "151") (name "Net-(C71-Pad2)") (class "Default")
      (node (ref "C71") (pin "2") (pinfunction "2_2") (pintype "passive"))
      (node (ref "R114") (pin "2") (pinfunction "2_2") (pintype "passive"))
    )
    (net (code "152") (name "Net-(C72-Pad2)") (class "Default")
      (node (ref "C72") (pin "2") (pinfunction "2_2") (pintype "passive"))
      (node (ref "R115") (pin "2") (pinfunction "2_2") (pintype "passive"))
    )
    (net (code "153") (name "Net-(C73-Pad2)") (class "Default")
      (node (ref "C73") (pin "2") (pinfunction "2_2") (pintype "passive"))
      (node (ref "R116") (pin "2") (pinfunction "2_2") (pintype "passive"))
    )
    (net (code "154") (name "Net-(C74-Pad2)") (class "Default")
      (node (ref "C74") (pin "2") (pinfunction "2_2") (pintype "passive"))
      (node (ref "R117") (pin "2") (pinfunction "2_2") (pintype "passive"))
    )
    (net (code "155") (name "Net-(C91-Pad2)") (class "Default")
      (node (ref "C91") (pin "2") (pinfunction "2_2") (pintype "passive"))
      (node (ref "R134") (pin "2") (pinfunction "2_2") (pintype "passive"))
    )
    (net (code "156") (name "Net-(C92-Pad2)") (class "Default")
      (node (ref "C92") (pin "2") (pinfunction "2_2") (pintype "passive"))
      (node (ref "R135") (pin "2") (pinfunction "2_2") (pintype "passive"))
    )
    (net (code "157") (name "Net-(C93-Pad2)") (class "Default")
      (node (ref "C93") (pin "2") (pinfunction "2_2") (pintype "passive"))
      (node (ref "R136") (pin "2") (pinfunction "2_2") (pintype "passive"))
    )
    (net (code "158") (name "Net-(C94-Pad2)") (class "Default")
      (node (ref "C94") (pin "2") (pinfunction "2_2") (pintype "passive"))
      (node (ref "R137") (pin "2") (pinfunction "2_2") (pintype "passive"))
    )
    (net (code "159") (name "Net-(C95-Pad2)") (class "Default")
      (node (ref "C95") (pin "2") (pinfunction "2_2") (pintype "passive"))
      (node (ref "R138") (pin "2") (pinfunction "2_2") (pintype "passive"))
    )
    (net (code "160") (name "Net-(C96-Pad2)") (class "Default")
      (node (ref "C96") (pin "2") (pinfunction "2_2") (pintype "passive"))
      (node (ref "R139") (pin "2") (pinfunction "2_2") (pintype "passive"))
    )
    (net (code "161") (name "Net-(C97-Pad2)") (class "Default")
      (node (ref "C97") (pin "2") (pinfunction "2_2") (pintype "passive"))
      (node (ref "R140") (pin "2") (pinfunction "2_2") (pintype "passive"))
    )
    (net (code "162") (name "Net-(C98-Pad2)") (class "Default")
      (node (ref "C98") (pin "2") (pinfunction "2_2") (pintype "passive"))
      (node (ref "R141") (pin "2") (pinfunction "2_2") (pintype "passive"))
    )
    (net (code "163") (name "Net-(C103-Pad1)") (class "Default")
      (node (ref "C103") (pin "1") (pinfunction "1_1") (pintype "passive"))
      (node (ref "R142") (pin "2") (pinfunction "2_2") (pintype "passive"))
    )
    (net (code "164") (name "Net-(C104-Pad1)") (class "Default")
      (node (ref "C104") (pin "1") (pinfunction "1_1") (pintype "passive"))
      (node (ref "R143") (pin "2") (pinfunction "2_2") (pintype "passive"))
    )
    (net (code "165") (name "Net-(C105-Pad1)") (class "Default")
      (node (ref "C105") (pin "1") (pinfunction "1_1") (pintype "passive"))
      (node (ref "R144") (pin "2") (pinfunction "2_2") (pintype "passive"))
    )
    (net (code "166") (name "Net-(C106-Pad1)") (class "Default")
      (node (ref "C106") (pin "1") (pinfunction "1_1") (pintype "passive"))
      (node (ref "R145") (pin "2") (pinfunction "2_2") (pintype "passive"))
    )
    (net (code "167") (name "Net-(C109-Pad2)") (class "Default")
      (node (ref "C109") (pin "2") (pinfunction "2_2") (pintype "passive"))
      (node (ref "R164") (pin "2") (pinfunction "2_2") (pintype "passive"))
    )
    (net (code "168") (name "Net-(C110-Pad2)") (class "Default")
      (node (ref "C110") (pin "2") (pinfunction "2_2") (pintype "passive"))
      (node (ref "R165") (pin "2") (pinfunction "2_2") (pintype "passive"))
    )
    (net (code "169") (name "Net-(C111-Pad2)") (class "Default")
      (node (ref "C111") (pin "2") (pinfunction "2_2") (pintype "passive"))
      (node (ref "R166") (pin "2") (pinfunction "2_2") (pintype "passive"))
    )
    (net (code "170") (name "Net-(C112-Pad2)") (class "Default")
      (node (ref "C112") (pin "2") (pinfunction "2_2") (pintype "passive"))
      (node (ref "R167") (pin "2") (pinfunction "2_2") (pintype "passive"))
    )
    (net (code "171") (name "Net-(C113-Pad2)") (class "Default")
      (node (ref "C113") (pin "2") (pinfunction "2_2") (pintype "passive"))
      (node (ref "R162") (pin "2") (pinfunction "2_2") (pintype "passive"))
    )
    (net (code "172") (name "Net-(C114-Pad2)") (class "Default")
      (node (ref "C114") (pin "2") (pinfunction "2_2") (pintype "passive"))
      (node (ref "R163") (pin "2") (pinfunction "2_2") (pintype "passive"))
    )
    (net (code "173") (name "Net-(C117-Pad1)") (class "Default")
      (node (ref "C117") (pin "1") (pinfunction "1_1") (pintype "passive"))
      (node (ref "R168") (pin "2") (pinfunction "2_2") (pintype "passive"))
    )
    (net (code "174") (name "Net-(C118-Pad1)") (class "Default")
      (node (ref "C118") (pin "1") (pinfunction "1_1") (pintype "passive"))
      (node (ref "R169") (pin "2") (pinfunction "2_2") (pintype "passive"))
    )
    (net (code "175") (name "Net-(C127-Pad2)") (class "Default")
      (node (ref "C127") (pin "2") (pinfunction "2_2") (pintype "passive"))
      (node (ref "R184") (pin "2") (pinfunction "2_2") (pintype "passive"))
    )
    (net (code "176") (name "Net-(C128-Pad2)") (class "Default")
      (node (ref "C128") (pin "2") (pinfunction "2_2") (pintype "passive"))
      (node (ref "R185") (pin "2") (pinfunction "2_2") (pintype "passive"))
    )
    (net (code "177") (name "Net-(C129-Pad2)") (class "Default")
      (node (ref "C129") (pin "2") (pinfunction "2_2") (pintype "passive"))
      (node (ref "R186") (pin "2") (pinfunction "2_2") (pintype "passive"))
    )
    (net (code "178") (name "Net-(C130-Pad2)") (class "Default")
      (node (ref "C130") (pin "2") (pinfunction "2_2") (pintype "passive"))
      (node (ref "R187") (pin "2") (pinfunction "2_2") (pintype "passive"))
    )
    (net (code "179") (name "Net-(C131-Pad2)") (class "Default")
      (node (ref "C131") (pin "2") (pinfunction "2_2") (pintype "passive"))
      (node (ref "R188") (pin "2") (pinfunction "2_2") (pintype "passive"))
    )
    (net (code "180") (name "Net-(C132-Pad2)") (class "Default")
      (node (ref "C132") (pin "2") (pinfunction "2_2") (pintype "passive"))
      (node (ref "R189") (pin "2") (pinfunction "2_2") (pintype "passive"))
    )
    (net (code "181") (name "Net-(C133-Pad2)") (class "Default")
      (node (ref "C133") (pin "2") (pinfunction "2_2") (pintype "passive"))
      (node (ref "R190") (pin "2") (pinfunction "2_2") (pintype "passive"))
    )
    (net (code "182") (name "Net-(C134-Pad2)") (class "Default")
      (node (ref "C134") (pin "2") (pinfunction "2_2") (pintype "passive"))
      (node (ref "R191") (pin "2") (pinfunction "2_2") (pintype "passive"))
    )
    (net (code "183") (name "Net-(C139-Pad1)") (class "Default")
      (node (ref "C139") (pin "1") (pinfunction "1_1") (pintype "passive"))
      (node (ref "R192") (pin "2") (pinfunction "2_2") (pintype "passive"))
    )
    (net (code "184") (name "Net-(C140-Pad1)") (class "Default")
      (node (ref "C140") (pin "1") (pinfunction "1_1") (pintype "passive"))
      (node (ref "R193") (pin "2") (pinfunction "2_2") (pintype "passive"))
    )
    (net (code "185") (name "Net-(C141-Pad1)") (class "Default")
      (node (ref "C141") (pin "1") (pinfunction "1_1") (pintype "passive"))
      (node (ref "R194") (pin "2") (pinfunction "2_2") (pintype "passive"))
    )
    (net (code "186") (name "Net-(C142-Pad1)") (class "Default")
      (node (ref "C142") (pin "1") (pinfunction "1_1") (pintype "passive"))
      (node (ref "R195") (pin "2") (pinfunction "2_2") (pintype "passive"))
    )
    (net (code "187") (name "Net-(D1-B)") (class "Default")
      (node (ref "D1") (pin "4") (pinfunction "B_4") (pintype "bidirectional"))
      (node (ref "R28") (pin "2") (pinfunction "2_2") (pintype "passive"))
    )
    (net (code "188") (name "Net-(D1-G)") (class "Default")
      (node (ref "D1") (pin "3") (pinfunction "G_3") (pintype "bidirectional"))
      (node (ref "R27") (pin "2") (pinfunction "2_2") (pintype "passive"))
    )
    (net (code "189") (name "Net-(D1-R)") (class "Default")
      (node (ref "D1") (pin "1") (pinfunction "R_1") (pintype "bidirectional"))
      (node (ref "R29") (pin "2") (pinfunction "2_2") (pintype "passive"))
    )
    (net (code "190") (name "Net-(D2-B)") (class "Default")
      (node (ref "D2") (pin "4") (pinfunction "B_4") (pintype "bidirectional"))
      (node (ref "R53") (pin "2") (pinfunction "2_2") (pintype "passive"))
    )
    (net (code "191") (name "Net-(D2-G)") (class "Default")
      (node (ref "D2") (pin "3") (pinfunction "G_3") (pintype "bidirectional"))
      (node (ref "R52") (pin "2") (pinfunction "2_2") (pintype "passive"))
    )
    (net (code "192") (name "Net-(D2-R)") (class "Default")
      (node (ref "D2") (pin "1") (pinfunction "R_1") (pintype "bidirectional"))
      (node (ref "R54") (pin "2") (pinfunction "2_2") (pintype "passive"))
    )
    (net (code "193") (name "Net-(D3-B)") (class "Default")
      (node (ref "D3") (pin "4") (pinfunction "B_4") (pintype "bidirectional"))
      (node (ref "R79") (pin "2") (pinfunction "2_2") (pintype "passive"))
    )
    (net (code "194") (name "Net-(D3-G)") (class "Default")
      (node (ref "D3") (pin "3") (pinfunction "G_3") (pintype "bidirectional"))
      (node (ref "R78") (pin "2") (pinfunction "2_2") (pintype "passive"))
    )
    (net (code "195") (name "Net-(D3-R)") (class "Default")
      (node (ref "D3") (pin "1") (pinfunction "R_1") (pintype "bidirectional"))
      (node (ref "R80") (pin "2") (pinfunction "2_2") (pintype "passive"))
    )
    (net (code "196") (name "Net-(D4-B)") (class "Default")
      (node (ref "D4") (pin "4") (pinfunction "B_4") (pintype "bidirectional"))
      (node (ref "R82") (pin "2") (pinfunction "2_2") (pintype "passive"))
    )
    (net (code "197") (name "Net-(D4-G)") (class "Default")
      (node (ref "D4") (pin "3") (pinfunction "G_3") (pintype "bidirectional"))
      (node (ref "R81") (pin "2") (pinfunction "2_2") (pintype "passive"))
    )
    (net (code "198") (name "Net-(D4-R)") (class "Default")
      (node (ref "D4") (pin "1") (pinfunction "R_1") (pintype "bidirectional"))
      (node (ref "R83") (pin "2") (pinfunction "2_2") (pintype "passive"))
    )
    (net (code "199") (name "Net-(D5-B)") (class "Default")
      (node (ref "D5") (pin "4") (pinfunction "B_4") (pintype "bidirectional"))
      (node (ref "R119") (pin "2") (pinfunction "2_2") (pintype "passive"))
    )
    (net (code "200") (name "Net-(D5-G)") (class "Default")
      (node (ref "D5") (pin "3") (pinfunction "G_3") (pintype "bidirectional"))
      (node (ref "R118") (pin "2") (pinfunction "2_2") (pintype "passive"))
    )
    (net (code "201") (name "Net-(D5-R)") (class "Default")
      (node (ref "D5") (pin "1") (pinfunction "R_1") (pintype "bidirectional"))
      (node (ref "R120") (pin "2") (pinfunction "2_2") (pintype "passive"))
    )
    (net (code "202") (name "Net-(D6-B)") (class "Default")
      (node (ref "D6") (pin "4") (pinfunction "B_4") (pintype "bidirectional"))
      (node (ref "R122") (pin "2") (pinfunction "2_2") (pintype "passive"))
    )
    (net (code "203") (name "Net-(D6-G)") (class "Default")
      (node (ref "D6") (pin "3") (pinfunction "G_3") (pintype "bidirectional"))
      (node (ref "R121") (pin "2") (pinfunction "2_2") (pintype "passive"))
    )
    (net (code "204") (name "Net-(D6-R)") (class "Default")
      (node (ref "D6") (pin "1") (pinfunction "R_1") (pintype "bidirectional"))
      (node (ref "R123") (pin "2") (pinfunction "2_2") (pintype "passive"))
    )
    (net (code "205") (name "Net-(D7-B)") (class "Default")
      (node (ref "D7") (pin "4") (pinfunction "B_4") (pintype "bidirectional"))
      (node (ref "R125") (pin "2") (pinfunction "2_2") (pintype "passive"))
    )
    (net (code "206") (name "Net-(D7-G)") (class "Default")
      (node (ref "D7") (pin "3") (pinfunction "G_3") (pintype "bidirectional"))
      (node (ref "R124") (pin "2") (pinfunction "2_2") (pintype "passive"))
    )
    (net (code "207") (name "Net-(D7-R)") (class "Default")
      (node (ref "D7") (pin "1") (pinfunction "R_1") (pintype "bidirectional"))
      (node (ref "R126") (pin "2") (pinfunction "2_2") (pintype "passive"))
    )
    (net (code "208") (name "Net-(D8-B)") (class "Default")
      (node (ref "D8") (pin "4") (pinfunction "B_4") (pintype "bidirectional"))
      (node (ref "R128") (pin "2") (pinfunction "2_2") (pintype "passive"))
    )
    (net (code "209") (name "Net-(D8-G)") (class "Default")
      (node (ref "D8") (pin "3") (pinfunction "G_3") (pintype "bidirectional"))
      (node (ref "R127") (pin "2") (pinfunction "2_2") (pintype "passive"))
    )
    (net (code "210") (name "Net-(D8-R)") (class "Default")
      (node (ref "D8") (pin "1") (pinfunction "R_1") (pintype "bidirectional"))
      (node (ref "R129") (pin "2") (pinfunction "2_2") (pintype "passive"))
    )
    (net (code "211") (name "Net-(D9-B)") (class "Default")
      (node (ref "D9") (pin "4") (pinfunction "B_4") (pintype "bidirectional"))
      (node (ref "R179") (pin "2") (pinfunction "2_2") (pintype "passive"))
    )
    (net (code "212") (name "Net-(D9-G)") (class "Default")
      (node (ref "D9") (pin "3") (pinfunction "G_3") (pintype "bidirectional"))
      (node (ref "R178") (pin "2") (pinfunction "2_2") (pintype "passive"))
    )
    (net (code "213") (name "Net-(D9-R)") (class "Default")
      (node (ref "D9") (pin "1") (pinfunction "R_1") (pintype "bidirectional"))
      (node (ref "R180") (pin "2") (pinfunction "2_2") (pintype "passive"))
    )
    (net (code "214") (name "Net-(D10-B)") (class "Default")
      (node (ref "D10") (pin "4") (pinfunction "B_4") (pintype "bidirectional"))
      (node (ref "R182") (pin "2") (pinfunction "2_2") (pintype "passive"))
    )
    (net (code "215") (name "Net-(D10-G)") (class "Default")
      (node (ref "D10") (pin "3") (pinfunction "G_3") (pintype "bidirectional"))
      (node (ref "R181") (pin "2") (pinfunction "2_2") (pintype "passive"))
    )
    (net (code "216") (name "Net-(D10-R)") (class "Default")
      (node (ref "D10") (pin "1") (pinfunction "R_1") (pintype "bidirectional"))
      (node (ref "R183") (pin "2") (pinfunction "2_2") (pintype "passive"))
    )
    (net (code "217") (name "Net-(IC1-OUT0)") (class "Default")
      (node (ref "IC1") (pin "1") (pinfunction "OUT0_1") (pintype "bidirectional"))
      (node (ref "R27") (pin "1") (pinfunction "1_1") (pintype "passive"))
    )
    (net (code "218") (name "Net-(IC1-OUT1)") (class "Default")
      (node (ref "IC1") (pin "2") (pinfunction "OUT1_2") (pintype "bidirectional"))
      (node (ref "R28") (pin "1") (pinfunction "1_1") (pintype "passive"))
    )
    (net (code "219") (name "Net-(IC1-OUT2)") (class "Default")
      (node (ref "IC1") (pin "3") (pinfunction "OUT2_3") (pintype "bidirectional"))
      (node (ref "R29") (pin "1") (pinfunction "1_1") (pintype "passive"))
    )
    (net (code "220") (name "Net-(IC2-OUT0)") (class "Default")
      (node (ref "IC2") (pin "1") (pinfunction "OUT0_1") (pintype "bidirectional"))
      (node (ref "R15") (pin "1") (pinfunction "1_1") (pintype "passive"))
    )
    (net (code "221") (name "Net-(IC2-OUT1)") (class "Default")
      (node (ref "IC2") (pin "2") (pinfunction "OUT1_2") (pintype "bidirectional"))
      (node (ref "R16") (pin "1") (pinfunction "1_1") (pintype "passive"))
    )
    (net (code "222") (name "Net-(IC2-OUT2)") (class "Default")
      (node (ref "IC2") (pin "3") (pinfunction "OUT2_3") (pintype "bidirectional"))
      (node (ref "R17") (pin "1") (pinfunction "1_1") (pintype "passive"))
    )
    (net (code "223") (name "Net-(IC3-OUT0)") (class "Default")
      (node (ref "IC3") (pin "1") (pinfunction "OUT0_1") (pintype "bidirectional"))
      (node (ref "R19") (pin "1") (pinfunction "1_1") (pintype "passive"))
    )
    (net (code "224") (name "Net-(IC3-OUT1)") (class "Default")
      (node (ref "IC3") (pin "2") (pinfunction "OUT1_2") (pintype "bidirectional"))
      (node (ref "R20") (pin "1") (pinfunction "1_1") (pintype "passive"))
    )
    (net (code "225") (name "Net-(IC3-OUT2)") (class "Default")
      (node (ref "IC3") (pin "3") (pinfunction "OUT2_3") (pintype "bidirectional"))
      (node (ref "R21") (pin "1") (pinfunction "1_1") (pintype "passive"))
    )
    (net (code "226") (name "Net-(IC4-OUT0)") (class "Default")
      (node (ref "IC4") (pin "1") (pinfunction "OUT0_1") (pintype "bidirectional"))
      (node (ref "R23") (pin "1") (pinfunction "1_1") (pintype "passive"))
    )
    (net (code "227") (name "Net-(IC4-OUT1)") (class "Default")
      (node (ref "IC4") (pin "2") (pinfunction "OUT1_2") (pintype "bidirectional"))
      (node (ref "R24") (pin "1") (pinfunction "1_1") (pintype "passive"))
    )
    (net (code "228") (name "Net-(IC4-OUT2)") (class "Default")
      (node (ref "IC4") (pin "3") (pinfunction "OUT2_3") (pintype "bidirectional"))
      (node (ref "R25") (pin "1") (pinfunction "1_1") (pintype "passive"))
    )
    (net (code "229") (name "Net-(IC5-OUT0)") (class "Default")
      (node (ref "IC5") (pin "1") (pinfunction "OUT0_1") (pintype "bidirectional"))
      (node (ref "R40") (pin "1") (pinfunction "1_1") (pintype "passive"))
    )
    (net (code "230") (name "Net-(IC5-OUT1)") (class "Default")
      (node (ref "IC5") (pin "2") (pinfunction "OUT1_2") (pintype "bidirectional"))
      (node (ref "R41") (pin "1") (pinfunction "1_1") (pintype "passive"))
    )
    (net (code "231") (name "Net-(IC5-OUT2)") (class "Default")
      (node (ref "IC5") (pin "3") (pinfunction "OUT2_3") (pintype "bidirectional"))
      (node (ref "R42") (pin "1") (pinfunction "1_1") (pintype "passive"))
    )
    (net (code "232") (name "Net-(IC6-OUT0)") (class "Default")
      (node (ref "IC6") (pin "1") (pinfunction "OUT0_1") (pintype "bidirectional"))
      (node (ref "R44") (pin "1") (pinfunction "1_1") (pintype "passive"))
    )
    (net (code "233") (name "Net-(IC6-OUT1)") (class "Default")
      (node (ref "IC6") (pin "2") (pinfunction "OUT1_2") (pintype "bidirectional"))
      (node (ref "R45") (pin "1") (pinfunction "1_1") (pintype "passive"))
    )
    (net (code "234") (name "Net-(IC6-OUT2)") (class "Default")
      (node (ref "IC6") (pin "3") (pinfunction "OUT2_3") (pintype "bidirectional"))
      (node (ref "R46") (pin "1") (pinfunction "1_1") (pintype "passive"))
    )
    (net (code "235") (name "Net-(IC7-OUT0)") (class "Default")
      (node (ref "IC7") (pin "1") (pinfunction "OUT0_1") (pintype "bidirectional"))
      (node (ref "R52") (pin "1") (pinfunction "1_1") (pintype "passive"))
    )
    (net (code "236") (name "Net-(IC7-OUT1)") (class "Default")
      (node (ref "IC7") (pin "2") (pinfunction "OUT1_2") (pintype "bidirectional"))
      (node (ref "R53") (pin "1") (pinfunction "1_1") (pintype "passive"))
    )
    (net (code "237") (name "Net-(IC7-OUT2)") (class "Default")
      (node (ref "IC7") (pin "3") (pinfunction "OUT2_3") (pintype "bidirectional"))
      (node (ref "R54") (pin "1") (pinfunction "1_1") (pintype "passive"))
    )
    (net (code "238") (name "Net-(IC8-OUT0)") (class "Default")
      (node (ref "IC8") (pin "1") (pinfunction "OUT0_1") (pintype "bidirectional"))
      (node (ref "R48") (pin "1") (pinfunction "1_1") (pintype "passive"))
    )
    (net (code "239") (name "Net-(IC8-OUT1)") (class "Default")
      (node (ref "IC8") (pin "2") (pinfunction "OUT1_2") (pintype "bidirectional"))
      (node (ref "R49") (pin "1") (pinfunction "1_1") (pintype "passive"))
    )
    (net (code "240") (name "Net-(IC8-OUT2)") (class "Default")
      (node (ref "IC8") (pin "3") (pinfunction "OUT2_3") (pintype "bidirectional"))
      (node (ref "R50") (pin "1") (pinfunction "1_1") (pintype "passive"))
    )
    (net (code "241") (name "Net-(IC9-OUT0)") (class "Default")
      (node (ref "IC9") (pin "1") (pinfunction "OUT0_1") (pintype "bidirectional"))
      (node (ref "R66") (pin "1") (pinfunction "1_1") (pintype "passive"))
    )
    (net (code "242") (name "Net-(IC9-OUT1)") (class "Default")
      (node (ref "IC9") (pin "2") (pinfunction "OUT1_2") (pintype "bidirectional"))
      (node (ref "R67") (pin "1") (pinfunction "1_1") (pintype "passive"))
    )
    (net (code "243") (name "Net-(IC9-OUT2)") (class "Default")
      (node (ref "IC9") (pin "3") (pinfunction "OUT2_3") (pintype "bidirectional"))
      (node (ref "R68") (pin "1") (pinfunction "1_1") (pintype "passive"))
    )
    (net (code "244") (name "Net-(IC10-OUT0)") (class "Default")
      (node (ref "IC10") (pin "1") (pinfunction "OUT0_1") (pintype "bidirectional"))
      (node (ref "R70") (pin "1") (pinfunction "1_1") (pintype "passive"))
    )
    (net (code "245") (name "Net-(IC10-OUT1)") (class "Default")
      (node (ref "IC10") (pin "2") (pinfunction "OUT1_2") (pintype "bidirectional"))
      (node (ref "R71") (pin "1") (pinfunction "1_1") (pintype "passive"))
    )
    (net (code "246") (name "Net-(IC10-OUT2)") (class "Default")
      (node (ref "IC10") (pin "3") (pinfunction "OUT2_3") (pintype "bidirectional"))
      (node (ref "R72") (pin "1") (pinfunction "1_1") (pintype "passive"))
    )
    (net (code "247") (name "Net-(IC11-OUT0)") (class "Default")
      (node (ref "IC11") (pin "1") (pinfunction "OUT0_1") (pintype "bidirectional"))
      (node (ref "R78") (pin "1") (pinfunction "1_1") (pintype "passive"))
    )
    (net (code "248") (name "Net-(IC11-OUT1)") (class "Default")
      (node (ref "IC11") (pin "2") (pinfunction "OUT1_2") (pintype "bidirectional"))
      (node (ref "R79") (pin "1") (pinfunction "1_1") (pintype "passive"))
    )
    (net (code "249") (name "Net-(IC11-OUT2)") (class "Default")
      (node (ref "IC11") (pin "3") (pinfunction "OUT2_3") (pintype "bidirectional"))
      (node (ref "R80") (pin "1") (pinfunction "1_1") (pintype "passive"))
    )
    (net (code "250") (name "Net-(IC12-OUT0)") (class "Default")
      (node (ref "IC12") (pin "1") (pinfunction "OUT0_1") (pintype "bidirectional"))
      (node (ref "R81") (pin "1") (pinfunction "1_1") (pintype "passive"))
    )
    (net (code "251") (name "Net-(IC12-OUT1)") (class "Default")
      (node (ref "IC12") (pin "2") (pinfunction "OUT1_2") (pintype "bidirectional"))
      (node (ref "R82") (pin "1") (pinfunction "1_1") (pintype "passive"))
    )
    (net (code "252") (name "Net-(IC12-OUT2)") (class "Default")
      (node (ref "IC12") (pin "3") (pinfunction "OUT2_3") (pintype "bidirectional"))
      (node (ref "R83") (pin "1") (pinfunction "1_1") (pintype "passive"))
    )
    (net (code "253") (name "Net-(IC13-OUT0)") (class "Default")
      (node (ref "IC13") (pin "1") (pinfunction "OUT0_1") (pintype "bidirectional"))
      (node (ref "R74") (pin "1") (pinfunction "1_1") (pintype "passive"))
    )
    (net (code "254") (name "Net-(IC13-OUT1)") (class "Default")
      (node (ref "IC13") (pin "2") (pinfunction "OUT1_2") (pintype "bidirectional"))
      (node (ref "R75") (pin "1") (pinfunction "1_1") (pintype "passive"))
    )
    (net (code "255") (name "Net-(IC13-OUT2)") (class "Default")
      (node (ref "IC13") (pin "3") (pinfunction "OUT2_3") (pintype "bidirectional"))
      (node (ref "R76") (pin "1") (pinfunction "1_1") (pintype "passive"))
    )
    (net (code "256") (name "Net-(IC14-OUT0)") (class "Default")
      (node (ref "IC14") (pin "1") (pinfunction "OUT0_1") (pintype "bidirectional"))
      (node (ref "R98") (pin "1") (pinfunction "1_1") (pintype "passive"))
    )
    (net (code "257") (name "Net-(IC14-OUT1)") (class "Default")
      (node (ref "IC14") (pin "2") (pinfunction "OUT1_2") (pintype "bidirectional"))
      (node (ref "R99") (pin "1") (pinfunction "1_1") (pintype "passive"))
    )
    (net (code "258") (name "Net-(IC14-OUT2)") (class "Default")
      (node (ref "IC14") (pin "3") (pinfunction "OUT2_3") (pintype "bidirectional"))
      (node (ref "R100") (pin "1") (pinfunction "1_1") (pintype "passive"))
    )
    (net (code "259") (name "Net-(IC15-OUT0)") (class "Default")
      (node (ref "IC15") (pin "1") (pinfunction "OUT0_1") (pintype "bidirectional"))
      (node (ref "R102") (pin "1") (pinfunction "1_1") (pintype "passive"))
    )
    (net (code "260") (name "Net-(IC15-OUT1)") (class "Default")
      (node (ref "IC15") (pin "2") (pinfunction "OUT1_2") (pintype "bidirectional"))
      (node (ref "R103") (pin "1") (pinfunction "1_1") (pintype "passive"))
    )
    (net (code "261") (name "Net-(IC15-OUT2)") (class "Default")
      (node (ref "IC15") (pin "3") (pinfunction "OUT2_3") (pintype "bidirectional"))
      (node (ref "R104") (pin "1") (pinfunction "1_1") (pintype "passive"))
    )
    (net (code "262") (name "Net-(IC16-OUT0)") (class "Default")
      (node (ref "IC16") (pin "1") (pinfunction "OUT0_1") (pintype "bidirectional"))
      (node (ref "R106") (pin "1") (pinfunction "1_1") (pintype "passive"))
    )
    (net (code "263") (name "Net-(IC16-OUT1)") (class "Default")
      (node (ref "IC16") (pin "2") (pinfunction "OUT1_2") (pintype "bidirectional"))
      (node (ref "R107") (pin "1") (pinfunction "1_1") (pintype "passive"))
    )
    (net (code "264") (name "Net-(IC16-OUT2)") (class "Default")
      (node (ref "IC16") (pin "3") (pinfunction "OUT2_3") (pintype "bidirectional"))
      (node (ref "R108") (pin "1") (pinfunction "1_1") (pintype "passive"))
    )
    (net (code "265") (name "Net-(IC17-OUT0)") (class "Default")
      (node (ref "IC17") (pin "1") (pinfunction "OUT0_1") (pintype "bidirectional"))
      (node (ref "R110") (pin "1") (pinfunction "1_1") (pintype "passive"))
    )
    (net (code "266") (name "Net-(IC17-OUT1)") (class "Default")
      (node (ref "IC17") (pin "2") (pinfunction "OUT1_2") (pintype "bidirectional"))
      (node (ref "R111") (pin "1") (pinfunction "1_1") (pintype "passive"))
    )
    (net (code "267") (name "Net-(IC17-OUT2)") (class "Default")
      (node (ref "IC17") (pin "3") (pinfunction "OUT2_3") (pintype "bidirectional"))
      (node (ref "R112") (pin "1") (pinfunction "1_1") (pintype "passive"))
    )
    (net (code "268") (name "Net-(IC18-OUT0)") (class "Default")
      (node (ref "IC18") (pin "1") (pinfunction "OUT0_1") (pintype "bidirectional"))
      (node (ref "R118") (pin "1") (pinfunction "1_1") (pintype "passive"))
    )
    (net (code "269") (name "Net-(IC18-OUT1)") (class "Default")
      (node (ref "IC18") (pin "2") (pinfunction "OUT1_2") (pintype "bidirectional"))
      (node (ref "R119") (pin "1") (pinfunction "1_1") (pintype "passive"))
    )
    (net (code "270") (name "Net-(IC18-OUT2)") (class "Default")
      (node (ref "IC18") (pin "3") (pinfunction "OUT2_3") (pintype "bidirectional"))
      (node (ref "R120") (pin "1") (pinfunction "1_1") (pintype "passive"))
    )
    (net (code "271") (name "Net-(IC19-OUT0)") (class "Default")
      (node (ref "IC19") (pin "1") (pinfunction "OUT0_1") (pintype "bidirectional"))
      (node (ref "R121") (pin "1") (pinfunction "1_1") (pintype "passive"))
    )
    (net (code "272") (name "Net-(IC19-OUT1)") (class "Default")
      (node (ref "IC19") (pin "2") (pinfunction "OUT1_2") (pintype "bidirectional"))
      (node (ref "R122") (pin "1") (pinfunction "1_1") (pintype "passive"))
    )
    (net (code "273") (name "Net-(IC19-OUT2)") (class "Default")
      (node (ref "IC19") (pin "3") (pinfunction "OUT2_3") (pintype "bidirectional"))
      (node (ref "R123") (pin "1") (pinfunction "1_1") (pintype "passive"))
    )
    (net (code "274") (name "Net-(IC20-OUT0)") (class "Default")
      (node (ref "IC20") (pin "1") (pinfunction "OUT0_1") (pintype "bidirectional"))
      (node (ref "R124") (pin "1") (pinfunction "1_1") (pintype "passive"))
    )
    (net (code "275") (name "Net-(IC20-OUT1)") (class "Default")
      (node (ref "IC20") (pin "2") (pinfunction "OUT1_2") (pintype "bidirectional"))
      (node (ref "R125") (pin "1") (pinfunction "1_1") (pintype "passive"))
    )
    (net (code "276") (name "Net-(IC20-OUT2)") (class "Default")
      (node (ref "IC20") (pin "3") (pinfunction "OUT2_3") (pintype "bidirectional"))
      (node (ref "R126") (pin "1") (pinfunction "1_1") (pintype "passive"))
    )
    (net (code "277") (name "Net-(IC21-OUT0)") (class "Default")
      (node (ref "IC21") (pin "1") (pinfunction "OUT0_1") (pintype "bidirectional"))
      (node (ref "R127") (pin "1") (pinfunction "1_1") (pintype "passive"))
    )
    (net (code "278") (name "Net-(IC21-OUT1)") (class "Default")
      (node (ref "IC21") (pin "2") (pinfunction "OUT1_2") (pintype "bidirectional"))
      (node (ref "R128") (pin "1") (pinfunction "1_1") (pintype "passive"))
    )
    (net (code "279") (name "Net-(IC21-OUT2)") (class "Default")
      (node (ref "IC21") (pin "3") (pinfunction "OUT2_3") (pintype "bidirectional"))
      (node (ref "R129") (pin "1") (pinfunction "1_1") (pintype "passive"))
    )
    (net (code "280") (name "Net-(IC22-OUT0)") (class "Default")
      (node (ref "IC22") (pin "1") (pinfunction "OUT0_1") (pintype "bidirectional"))
      (node (ref "R146") (pin "1") (pinfunction "1_1") (pintype "passive"))
    )
    (net (code "281") (name "Net-(IC22-OUT1)") (class "Default")
      (node (ref "IC22") (pin "2") (pinfunction "OUT1_2") (pintype "bidirectional"))
      (node (ref "R147") (pin "1") (pinfunction "1_1") (pintype "passive"))
    )
    (net (code "282") (name "Net-(IC22-OUT2)") (class "Default")
      (node (ref "IC22") (pin "3") (pinfunction "OUT2_3") (pintype "bidirectional"))
      (node (ref "R148") (pin "1") (pinfunction "1_1") (pintype "passive"))
    )
    (net (code "283") (name "Net-(IC23-OUT0)") (class "Default")
      (node (ref "IC23") (pin "1") (pinfunction "OUT0_1") (pintype "bidirectional"))
      (node (ref "R150") (pin "1") (pinfunction "1_1") (pintype "passive"))
    )
    (net (code "284") (name "Net-(IC23-OUT1)") (class "Default")
      (node (ref "IC23") (pin "2") (pinfunction "OUT1_2") (pintype "bidirectional"))
      (node (ref "R151") (pin "1") (pinfunction "1_1") (pintype "passive"))
    )
    (net (code "285") (name "Net-(IC23-OUT2)") (class "Default")
      (node (ref "IC23") (pin "3") (pinfunction "OUT2_3") (pintype "bidirectional"))
      (node (ref "R152") (pin "1") (pinfunction "1_1") (pintype "passive"))
    )
    (net (code "286") (name "Net-(IC24-OUT0)") (class "Default")
      (node (ref "IC24") (pin "1") (pinfunction "OUT0_1") (pintype "bidirectional"))
      (node (ref "R154") (pin "1") (pinfunction "1_1") (pintype "passive"))
    )
    (net (code "287") (name "Net-(IC24-OUT1)") (class "Default")
      (node (ref "IC24") (pin "2") (pinfunction "OUT1_2") (pintype "bidirectional"))
      (node (ref "R155") (pin "1") (pinfunction "1_1") (pintype "passive"))
    )
    (net (code "288") (name "Net-(IC24-OUT2)") (class "Default")
      (node (ref "IC24") (pin "3") (pinfunction "OUT2_3") (pintype "bidirectional"))
      (node (ref "R156") (pin "1") (pinfunction "1_1") (pintype "passive"))
    )
    (net (code "289") (name "Net-(IC25-OUT0)") (class "Default")
      (node (ref "IC25") (pin "1") (pinfunction "OUT0_1") (pintype "bidirectional"))
      (node (ref "R158") (pin "1") (pinfunction "1_1") (pintype "passive"))
    )
    (net (code "290") (name "Net-(IC25-OUT1)") (class "Default")
      (node (ref "IC25") (pin "2") (pinfunction "OUT1_2") (pintype "bidirectional"))
      (node (ref "R159") (pin "1") (pinfunction "1_1") (pintype "passive"))
    )
    (net (code "291") (name "Net-(IC25-OUT2)") (class "Default")
      (node (ref "IC25") (pin "3") (pinfunction "OUT2_3") (pintype "bidirectional"))
      (node (ref "R160") (pin "1") (pinfunction "1_1") (pintype "passive"))
    )
    (net (code "292") (name "Net-(IC26-OUT0)") (class "Default")
      (node (ref "IC26") (pin "1") (pinfunction "OUT0_1") (pintype "bidirectional"))
      (node (ref "R178") (pin "1") (pinfunction "1_1") (pintype "passive"))
    )
    (net (code "293") (name "Net-(IC26-OUT1)") (class "Default")
      (node (ref "IC26") (pin "2") (pinfunction "OUT1_2") (pintype "bidirectional"))
      (node (ref "R179") (pin "1") (pinfunction "1_1") (pintype "passive"))
    )
    (net (code "294") (name "Net-(IC26-OUT2)") (class "Default")
      (node (ref "IC26") (pin "3") (pinfunction "OUT2_3") (pintype "bidirectional"))
      (node (ref "R180") (pin "1") (pinfunction "1_1") (pintype "passive"))
    )
    (net (code "295") (name "Net-(IC27-OUT0)") (class "Default")
      (node (ref "IC27") (pin "1") (pinfunction "OUT0_1") (pintype "bidirectional"))
      (node (ref "R181") (pin "1") (pinfunction "1_1") (pintype "passive"))
    )
    (net (code "296") (name "Net-(IC27-OUT1)") (class "Default")
      (node (ref "IC27") (pin "2") (pinfunction "OUT1_2") (pintype "bidirectional"))
      (node (ref "R182") (pin "1") (pinfunction "1_1") (pintype "passive"))
    )
    (net (code "297") (name "Net-(IC27-OUT2)") (class "Default")
      (node (ref "IC27") (pin "3") (pinfunction "OUT2_3") (pintype "bidirectional"))
      (node (ref "R183") (pin "1") (pinfunction "1_1") (pintype "passive"))
    )
    (net (code "298") (name "Net-(IC28-OUT0)") (class "Default")
      (node (ref "IC28") (pin "1") (pinfunction "OUT0_1") (pintype "bidirectional"))
      (node (ref "R170") (pin "1") (pinfunction "1_1") (pintype "passive"))
    )
    (net (code "299") (name "Net-(IC28-OUT1)") (class "Default")
      (node (ref "IC28") (pin "2") (pinfunction "OUT1_2") (pintype "bidirectional"))
      (node (ref "R171") (pin "1") (pinfunction "1_1") (pintype "passive"))
    )
    (net (code "300") (name "Net-(IC28-OUT2)") (class "Default")
      (node (ref "IC28") (pin "3") (pinfunction "OUT2_3") (pintype "bidirectional"))
      (node (ref "R172") (pin "1") (pinfunction "1_1") (pintype "passive"))
    )
    (net (code "301") (name "Net-(IC29-OUT0)") (class "Default")
      (node (ref "IC29") (pin "1") (pinfunction "OUT0_1") (pintype "bidirectional"))
      (node (ref "R174") (pin "1") (pinfunction "1_1") (pintype "passive"))
    )
    (net (code "302") (name "Net-(IC29-OUT1)") (class "Default")
      (node (ref "IC29") (pin "2") (pinfunction "OUT1_2") (pintype "bidirectional"))
      (node (ref "R175") (pin "1") (pinfunction "1_1") (pintype "passive"))
    )
    (net (code "303") (name "Net-(IC29-OUT2)") (class "Default")
      (node (ref "IC29") (pin "3") (pinfunction "OUT2_3") (pintype "bidirectional"))
      (node (ref "R176") (pin "1") (pinfunction "1_1") (pintype "passive"))
    )
    (net (code "304") (name "Net-(IC30-OUT0)") (class "Default")
      (node (ref "IC30") (pin "1") (pinfunction "OUT0_1") (pintype "bidirectional"))
      (node (ref "R196") (pin "1") (pinfunction "1_1") (pintype "passive"))
    )
    (net (code "305") (name "Net-(IC30-OUT1)") (class "Default")
      (node (ref "IC30") (pin "2") (pinfunction "OUT1_2") (pintype "bidirectional"))
      (node (ref "R197") (pin "1") (pinfunction "1_1") (pintype "passive"))
    )
    (net (code "306") (name "Net-(IC30-OUT2)") (class "Default")
      (node (ref "IC30") (pin "3") (pinfunction "OUT2_3") (pintype "bidirectional"))
      (node (ref "R198") (pin "1") (pinfunction "1_1") (pintype "passive"))
    )
    (net (code "307") (name "Net-(IC31-OUT0)") (class "Default")
      (node (ref "IC31") (pin "1") (pinfunction "OUT0_1") (pintype "bidirectional"))
      (node (ref "R200") (pin "1") (pinfunction "1_1") (pintype "passive"))
    )
    (net (code "308") (name "Net-(IC31-OUT1)") (class "Default")
      (node (ref "IC31") (pin "2") (pinfunction "OUT1_2") (pintype "bidirectional"))
      (node (ref "R201") (pin "1") (pinfunction "1_1") (pintype "passive"))
    )
    (net (code "309") (name "Net-(IC31-OUT2)") (class "Default")
      (node (ref "IC31") (pin "3") (pinfunction "OUT2_3") (pintype "bidirectional"))
      (node (ref "R202") (pin "1") (pinfunction "1_1") (pintype "passive"))
    )
    (net (code "310") (name "Net-(IC32-OUT0)") (class "Default")
      (node (ref "IC32") (pin "1") (pinfunction "OUT0_1") (pintype "bidirectional"))
      (node (ref "R204") (pin "1") (pinfunction "1_1") (pintype "passive"))
    )
    (net (code "311") (name "Net-(IC32-OUT1)") (class "Default")
      (node (ref "IC32") (pin "2") (pinfunction "OUT1_2") (pintype "bidirectional"))
      (node (ref "R205") (pin "1") (pinfunction "1_1") (pintype "passive"))
    )
    (net (code "312") (name "Net-(IC32-OUT2)") (class "Default")
      (node (ref "IC32") (pin "3") (pinfunction "OUT2_3") (pintype "bidirectional"))
      (node (ref "R206") (pin "1") (pinfunction "1_1") (pintype "passive"))
    )
    (net (code "313") (name "Net-(IC33-OUT0)") (class "Default")
      (node (ref "IC33") (pin "1") (pinfunction "OUT0_1") (pintype "bidirectional"))
      (node (ref "R208") (pin "1") (pinfunction "1_1") (pintype "passive"))
    )
    (net (code "314") (name "Net-(IC33-OUT1)") (class "Default")
      (node (ref "IC33") (pin "2") (pinfunction "OUT1_2") (pintype "bidirectional"))
      (node (ref "R209") (pin "1") (pinfunction "1_1") (pintype "passive"))
    )
    (net (code "315") (name "Net-(IC33-OUT2)") (class "Default")
      (node (ref "IC33") (pin "3") (pinfunction "OUT2_3") (pintype "bidirectional"))
      (node (ref "R210") (pin "1") (pinfunction "1_1") (pintype "passive"))
    )
    (net (code "316") (name "Net-(S1--B)") (class "Default")
      (node (ref "R17") (pin "2") (pinfunction "2_2") (pintype "passive"))
      (node (ref "S1") (pin "4") (pinfunction "-B_4") (pintype "passive"))
    )
    (net (code "317") (name "Net-(S1--G)") (class "Default")
      (node (ref "R16") (pin "2") (pinfunction "2_2") (pintype "passive"))
      (node (ref "S1") (pin "2") (pinfunction "-G_2") (pintype "passive"))
    )
    (net (code "318") (name "Net-(S1--R)") (class "Default")
      (node (ref "R15") (pin "2") (pinfunction "2_2") (pintype "passive"))
      (node (ref "S1") (pin "1") (pinfunction "-R_1") (pintype "passive"))
    )
    (net (code "319") (name "Net-(S2--B)") (class "Default")
      (node (ref "R21") (pin "2") (pinfunction "2_2") (pintype "passive"))
      (node (ref "S2") (pin "4") (pinfunction "-B_4") (pintype "passive"))
    )
    (net (code "320") (name "Net-(S2--G)") (class "Default")
      (node (ref "R20") (pin "2") (pinfunction "2_2") (pintype "passive"))
      (node (ref "S2") (pin "2") (pinfunction "-G_2") (pintype "passive"))
    )
    (net (code "321") (name "Net-(S2--R)") (class "Default")
      (node (ref "R19") (pin "2") (pinfunction "2_2") (pintype "passive"))
      (node (ref "S2") (pin "1") (pinfunction "-R_1") (pintype "passive"))
    )
    (net (code "322") (name "Net-(S3--B)") (class "Default")
      (node (ref "R25") (pin "2") (pinfunction "2_2") (pintype "passive"))
      (node (ref "S3") (pin "4") (pinfunction "-B_4") (pintype "passive"))
    )
    (net (code "323") (name "Net-(S3--G)") (class "Default")
      (node (ref "R24") (pin "2") (pinfunction "2_2") (pintype "passive"))
      (node (ref "S3") (pin "2") (pinfunction "-G_2") (pintype "passive"))
    )
    (net (code "324") (name "Net-(S3--R)") (class "Default")
      (node (ref "R23") (pin "2") (pinfunction "2_2") (pintype "passive"))
      (node (ref "S3") (pin "1") (pinfunction "-R_1") (pintype "passive"))
    )
    (net (code "325") (name "Net-(S4--B)") (class "Default")
      (node (ref "R42") (pin "2") (pinfunction "2_2") (pintype "passive"))
      (node (ref "S4") (pin "4") (pinfunction "-B_4") (pintype "passive"))
    )
    (net (code "326") (name "Net-(S4--G)") (class "Default")
      (node (ref "R41") (pin "2") (pinfunction "2_2") (pintype "passive"))
      (node (ref "S4") (pin "2") (pinfunction "-G_2") (pintype "passive"))
    )
    (net (code "327") (name "Net-(S4--R)") (class "Default")
      (node (ref "R40") (pin "2") (pinfunction "2_2") (pintype "passive"))
      (node (ref "S4") (pin "1") (pinfunction "-R_1") (pintype "passive"))
    )
    (net (code "328") (name "Net-(S5--B)") (class "Default")
      (node (ref "R46") (pin "2") (pinfunction "2_2") (pintype "passive"))
      (node (ref "S5") (pin "4") (pinfunction "-B_4") (pintype "passive"))
    )
    (net (code "329") (name "Net-(S5--G)") (class "Default")
      (node (ref "R45") (pin "2") (pinfunction "2_2") (pintype "passive"))
      (node (ref "S5") (pin "2") (pinfunction "-G_2") (pintype "passive"))
    )
    (net (code "330") (name "Net-(S5--R)") (class "Default")
      (node (ref "R44") (pin "2") (pinfunction "2_2") (pintype "passive"))
      (node (ref "S5") (pin "1") (pinfunction "-R_1") (pintype "passive"))
    )
    (net (code "331") (name "Net-(S6--B)") (class "Default")
      (node (ref "R50") (pin "2") (pinfunction "2_2") (pintype "passive"))
      (node (ref "S6") (pin "4") (pinfunction "-B_4") (pintype "passive"))
    )
    (net (code "332") (name "Net-(S6--G)") (class "Default")
      (node (ref "R49") (pin "2") (pinfunction "2_2") (pintype "passive"))
      (node (ref "S6") (pin "2") (pinfunction "-G_2") (pintype "passive"))
    )
    (net (code "333") (name "Net-(S6--R)") (class "Default")
      (node (ref "R48") (pin "2") (pinfunction "2_2") (pintype "passive"))
      (node (ref "S6") (pin "1") (pinfunction "-R_1") (pintype "passive"))
    )
    (net (code "334") (name "Net-(S7--B)") (class "Default")
      (node (ref "R68") (pin "2") (pinfunction "2_2") (pintype "passive"))
      (node (ref "S7") (pin "4") (pinfunction "-B_4") (pintype "passive"))
    )
    (net (code "335") (name "Net-(S7--G)") (class "Default")
      (node (ref "R67") (pin "2") (pinfunction "2_2") (pintype "passive"))
      (node (ref "S7") (pin "2") (pinfunction "-G_2") (pintype "passive"))
    )
    (net (code "336") (name "Net-(S7--R)") (class "Default")
      (node (ref "R66") (pin "2") (pinfunction "2_2") (pintype "passive"))
      (node (ref "S7") (pin "1") (pinfunction "-R_1") (pintype "passive"))
    )
    (net (code "337") (name "Net-(S8--B)") (class "Default")
      (node (ref "R72") (pin "2") (pinfunction "2_2") (pintype "passive"))
      (node (ref "S8") (pin "4") (pinfunction "-B_4") (pintype "passive"))
    )
    (net (code "338") (name "Net-(S8--G)") (class "Default")
      (node (ref "R71") (pin "2") (pinfunction "2_2") (pintype "passive"))
      (node (ref "S8") (pin "2") (pinfunction "-G_2") (pintype "passive"))
    )
    (net (code "339") (name "Net-(S8--R)") (class "Default")
      (node (ref "R70") (pin "2") (pinfunction "2_2") (pintype "passive"))
      (node (ref "S8") (pin "1") (pinfunction "-R_1") (pintype "passive"))
    )
    (net (code "340") (name "Net-(S9--B)") (class "Default")
      (node (ref "R76") (pin "2") (pinfunction "2_2") (pintype "passive"))
      (node (ref "S9") (pin "4") (pinfunction "-B_4") (pintype "passive"))
    )
    (net (code "341") (name "Net-(S9--G)") (class "Default")
      (node (ref "R75") (pin "2") (pinfunction "2_2") (pintype "passive"))
      (node (ref "S9") (pin "2") (pinfunction "-G_2") (pintype "passive"))
    )
    (net (code "342") (name "Net-(S9--R)") (class "Default")
      (node (ref "R74") (pin "2") (pinfunction "2_2") (pintype "passive"))
      (node (ref "S9") (pin "1") (pinfunction "-R_1") (pintype "passive"))
    )
    (net (code "343") (name "Net-(S10--B)") (class "Default")
      (node (ref "R100") (pin "2") (pinfunction "2_2") (pintype "passive"))
      (node (ref "S10") (pin "4") (pinfunction "-B_4") (pintype "passive"))
    )
    (net (code "344") (name "Net-(S10--G)") (class "Default")
      (node (ref "R99") (pin "2") (pinfunction "2_2") (pintype "passive"))
      (node (ref "S10") (pin "2") (pinfunction "-G_2") (pintype "passive"))
    )
    (net (code "345") (name "Net-(S10--R)") (class "Default")
      (node (ref "R98") (pin "2") (pinfunction "2_2") (pintype "passive"))
      (node (ref "S10") (pin "1") (pinfunction "-R_1") (pintype "passive"))
    )
    (net (code "346") (name "Net-(S11--B)") (class "Default")
      (node (ref "R104") (pin "2") (pinfunction "2_2") (pintype "passive"))
      (node (ref "S11") (pin "4") (pinfunction "-B_4") (pintype "passive"))
    )
    (net (code "347") (name "Net-(S11--G)") (class "Default")
      (node (ref "R103") (pin "2") (pinfunction "2_2") (pintype "passive"))
      (node (ref "S11") (pin "2") (pinfunction "-G_2") (pintype "passive"))
    )
    (net (code "348") (name "Net-(S11--R)") (class "Default")
      (node (ref "R102") (pin "2") (pinfunction "2_2") (pintype "passive"))
      (node (ref "S11") (pin "1") (pinfunction "-R_1") (pintype "passive"))
    )
    (net (code "349") (name "Net-(S12--B)") (class "Default")
      (node (ref "R108") (pin "2") (pinfunction "2_2") (pintype "passive"))
      (node (ref "S12") (pin "4") (pinfunction "-B_4") (pintype "passive"))
    )
    (net (code "350") (name "Net-(S12--G)") (class "Default")
      (node (ref "R107") (pin "2") (pinfunction "2_2") (pintype "passive"))
      (node (ref "S12") (pin "2") (pinfunction "-G_2") (pintype "passive"))
    )
    (net (code "351") (name "Net-(S12--R)") (class "Default")
      (node (ref "R106") (pin "2") (pinfunction "2_2") (pintype "passive"))
      (node (ref "S12") (pin "1") (pinfunction "-R_1") (pintype "passive"))
    )
    (net (code "352") (name "Net-(S13--B)") (class "Default")
      (node (ref "R112") (pin "2") (pinfunction "2_2") (pintype "passive"))
      (node (ref "S13") (pin "4") (pinfunction "-B_4") (pintype "passive"))
    )
    (net (code "353") (name "Net-(S13--G)") (class "Default")
      (node (ref "R111") (pin "2") (pinfunction "2_2") (pintype "passive"))
      (node (ref "S13") (pin "2") (pinfunction "-G_2") (pintype "passive"))
    )
    (net (code "354") (name "Net-(S13--R)") (class "Default")
      (node (ref "R110") (pin "2") (pinfunction "2_2") (pintype "passive"))
      (node (ref "S13") (pin "1") (pinfunction "-R_1") (pintype "passive"))
    )
    (net (code "355") (name "Net-(S14--B)") (class "Default")
      (node (ref "R148") (pin "2") (pinfunction "2_2") (pintype "passive"))
      (node (ref "S14") (pin "4") (pinfunction "-B_4") (pintype "passive"))
    )
    (net (code "356") (name "Net-(S14--G)") (class "Default")
      (node (ref "R147") (pin "2") (pinfunction "2_2") (pintype "passive"))
      (node (ref "S14") (pin "2") (pinfunction "-G_2") (pintype "passive"))
    )
    (net (code "357") (name "Net-(S14--R)") (class "Default")
      (node (ref "R146") (pin "2") (pinfunction "2_2") (pintype "passive"))
      (node (ref "S14") (pin "1") (pinfunction "-R_1") (pintype "passive"))
    )
    (net (code "358") (name "Net-(S15--B)") (class "Default")
      (node (ref "R152") (pin "2") (pinfunction "2_2") (pintype "passive"))
      (node (ref "S15") (pin "4") (pinfunction "-B_4") (pintype "passive"))
    )
    (net (code "359") (name "Net-(S15--G)") (class "Default")
      (node (ref "R151") (pin "2") (pinfunction "2_2") (pintype "passive"))
      (node (ref "S15") (pin "2") (pinfunction "-G_2") (pintype "passive"))
    )
    (net (code "360") (name "Net-(S15--R)") (class "Default")
      (node (ref "R150") (pin "2") (pinfunction "2_2") (pintype "passive"))
      (node (ref "S15") (pin "1") (pinfunction "-R_1") (pintype "passive"))
    )
    (net (code "361") (name "Net-(S16--B)") (class "Default")
      (node (ref "R156") (pin "2") (pinfunction "2_2") (pintype "passive"))
      (node (ref "S16") (pin "4") (pinfunction "-B_4") (pintype "passive"))
    )
    (net (code "362") (name "Net-(S16--G)") (class "Default")
      (node (ref "R155") (pin "2") (pinfunction "2_2") (pintype "passive"))
      (node (ref "S16") (pin "2") (pinfunction "-G_2") (pintype "passive"))
    )
    (net (code "363") (name "Net-(S16--R)") (class "Default")
      (node (ref "R154") (pin "2") (pinfunction "2_2") (pintype "passive"))
      (node (ref "S16") (pin "1") (pinfunction "-R_1") (pintype "passive"))
    )
    (net (code "364") (name "Net-(S17--B)") (class "Default")
      (node (ref "R160") (pin "2") (pinfunction "2_2") (pintype "passive"))
      (node (ref "S17") (pin "4") (pinfunction "-B_4") (pintype "passive"))
    )
    (net (code "365") (name "Net-(S17--G)") (class "Default")
      (node (ref "R159") (pin "2") (pinfunction "2_2") (pintype "passive"))
      (node (ref "S17") (pin "2") (pinfunction "-G_2") (pintype "passive"))
    )
    (net (code "366") (name "Net-(S17--R)") (class "Default")
      (node (ref "R158") (pin "2") (pinfunction "2_2") (pintype "passive"))
      (node (ref "S17") (pin "1") (pinfunction "-R_1") (pintype "passive"))
    )
    (net (code "367") (name "Net-(S18--B)") (class "Default")
      (node (ref "R172") (pin "2") (pinfunction "2_2") (pintype "passive"))
      (node (ref "S18") (pin "4") (pinfunction "-B_4") (pintype "passive"))
    )
    (net (code "368") (name "Net-(S18--G)") (class "Default")
      (node (ref "R171") (pin "2") (pinfunction "2_2") (pintype "passive"))
      (node (ref "S18") (pin "2") (pinfunction "-G_2") (pintype "passive"))
    )
    (net (code "369") (name "Net-(S18--R)") (class "Default")
      (node (ref "R170") (pin "2") (pinfunction "2_2") (pintype "passive"))
      (node (ref "S18") (pin "1") (pinfunction "-R_1") (pintype "passive"))
    )
    (net (code "370") (name "Net-(S19--B)") (class "Default")
      (node (ref "R176") (pin "2") (pinfunction "2_2") (pintype "passive"))
      (node (ref "S19") (pin "4") (pinfunction "-B_4") (pintype "passive"))
    )
    (net (code "371") (name "Net-(S19--G)") (class "Default")
      (node (ref "R175") (pin "2") (pinfunction "2_2") (pintype "passive"))
      (node (ref "S19") (pin "2") (pinfunction "-G_2") (pintype "passive"))
    )
    (net (code "372") (name "Net-(S19--R)") (class "Default")
      (node (ref "R174") (pin "2") (pinfunction "2_2") (pintype "passive"))
      (node (ref "S19") (pin "1") (pinfunction "-R_1") (pintype "passive"))
    )
    (net (code "373") (name "Net-(S20--B)") (class "Default")
      (node (ref "R198") (pin "2") (pinfunction "2_2") (pintype "passive"))
      (node (ref "S20") (pin "4") (pinfunction "-B_4") (pintype "passive"))
    )
    (net (code "374") (name "Net-(S20--G)") (class "Default")
      (node (ref "R197") (pin "2") (pinfunction "2_2") (pintype "passive"))
      (node (ref "S20") (pin "2") (pinfunction "-G_2") (pintype "passive"))
    )
    (net (code "375") (name "Net-(S20--R)") (class "Default")
      (node (ref "R196") (pin "2") (pinfunction "2_2") (pintype "passive"))
      (node (ref "S20") (pin "1") (pinfunction "-R_1") (pintype "passive"))
    )
    (net (code "376") (name "Net-(S21--B)") (class "Default")
      (node (ref "R202") (pin "2") (pinfunction "2_2") (pintype "passive"))
      (node (ref "S21") (pin "4") (pinfunction "-B_4") (pintype "passive"))
    )
    (net (code "377") (name "Net-(S21--G)") (class "Default")
      (node (ref "R201") (pin "2") (pinfunction "2_2") (pintype "passive"))
      (node (ref "S21") (pin "2") (pinfunction "-G_2") (pintype "passive"))
    )
    (net (code "378") (name "Net-(S21--R)") (class "Default")
      (node (ref "R200") (pin "2") (pinfunction "2_2") (pintype "passive"))
      (node (ref "S21") (pin "1") (pinfunction "-R_1") (pintype "passive"))
    )
    (net (code "379") (name "Net-(S22--B)") (class "Default")
      (node (ref "R206") (pin "2") (pinfunction "2_2") (pintype "passive"))
      (node (ref "S22") (pin "4") (pinfunction "-B_4") (pintype "passive"))
    )
    (net (code "380") (name "Net-(S22--G)") (class "Default")
      (node (ref "R205") (pin "2") (pinfunction "2_2") (pintype "passive"))
      (node (ref "S22") (pin "2") (pinfunction "-G_2") (pintype "passive"))
    )
    (net (code "381") (name "Net-(S22--R)") (class "Default")
      (node (ref "R204") (pin "2") (pinfunction "2_2") (pintype "passive"))
      (node (ref "S22") (pin "1") (pinfunction "-R_1") (pintype "passive"))
    )
    (net (code "382") (name "Net-(S23--B)") (class "Default")
      (node (ref "R210") (pin "2") (pinfunction "2_2") (pintype "passive"))
      (node (ref "S23") (pin "4") (pinfunction "-B_4") (pintype "passive"))
    )
    (net (code "383") (name "Net-(S23--G)") (class "Default")
      (node (ref "R209") (pin "2") (pinfunction "2_2") (pintype "passive"))
      (node (ref "S23") (pin "2") (pinfunction "-G_2") (pintype "passive"))
    )
    (net (code "384") (name "Net-(S23--R)") (class "Default")
      (node (ref "R208") (pin "2") (pinfunction "2_2") (pintype "passive"))
      (node (ref "S23") (pin "1") (pinfunction "-R_1") (pintype "passive"))
    )
    (net (code "385") (name "PIXEL41") (class "Default")
      (node (ref "IC14") (pin "5") (pinfunction "SDO_5") (pintype "bidirectional"))
      (node (ref "IC20") (pin "6") (pinfunction "SDI_6") (pintype "bidirectional"))
    )
    (net (code "386") (name "PIXEL42") (class "Default")
      (node (ref "IC2") (pin "6") (pinfunction "SDI_6") (pintype "bidirectional"))
      (node (ref "IC21") (pin "5") (pinfunction "SDO_5") (pintype "bidirectional"))
    )
    (net (code "387") (name "PIXEL43") (class "Default")
      (node (ref "IC15") (pin "6") (pinfunction "SDI_6") (pintype "bidirectional"))
      (node (ref "IC20") (pin "5") (pinfunction "SDO_5") (pintype "bidirectional"))
    )
    (net (code "388") (name "PIXEL44") (class "Default")
      (node (ref "IC15") (pin "5") (pinfunction "SDO_5") (pintype "bidirectional"))
      (node (ref "IC21") (pin "6") (pinfunction "SDI_6") (pintype "bidirectional"))
    )
    (net (code "389") (name "PIXEL_45") (class "Default")
      (node (ref "IC16") (pin "5") (pinfunction "SDO_5") (pintype "bidirectional"))
      (node (ref "IC19") (pin "6") (pinfunction "SDI_6") (pintype "bidirectional"))
    )
    (net (code "390") (name "PIXEL_46") (class "Default")
      (node (ref "IC17") (pin "6") (pinfunction "SDI_6") (pintype "bidirectional"))
      (node (ref "IC19") (pin "5") (pinfunction "SDO_5") (pintype "bidirectional"))
    )
    (net (code "391") (name "PIXEL_47") (class "Default")
      (node (ref "IC16") (pin "6") (pinfunction "SDI_6") (pintype "bidirectional"))
      (node (ref "IC18") (pin "5") (pinfunction "SDO_5") (pintype "bidirectional"))
    )
    (net (code "392") (name "PIXEL_48") (class "Default")
      (node (ref "IC17") (pin "5") (pinfunction "SDO_5") (pintype "bidirectional"))
      (node (ref "IC33") (pin "6") (pinfunction "SDI_6") (pintype "bidirectional"))
    )
    (net (code "393") (name "PIXEL_51") (class "Default")
      (node (ref "IC25") (pin "5") (pinfunction "SDO_5") (pintype "bidirectional"))
      (node (ref "IC27") (pin "6") (pinfunction "SDI_6") (pintype "bidirectional"))
    )
    (net (code "394") (name "PIXEL_52") (class "Default")
      (node (ref "IC24") (pin "6") (pinfunction "SDI_6") (pintype "bidirectional"))
      (node (ref "IC27") (pin "5") (pinfunction "SDO_5") (pintype "bidirectional"))
    )
    (net (code "395") (name "PIXEL_53") (class "Default")
      (node (ref "IC24") (pin "5") (pinfunction "SDO_5") (pintype "bidirectional"))
      (node (ref "IC28") (pin "6") (pinfunction "SDI_6") (pintype "bidirectional"))
    )
    (net (code "396") (name "PIXEL_54") (class "Default")
      (node (ref "IC18") (pin "6") (pinfunction "SDI_6") (pintype "bidirectional"))
      (node (ref "IC23") (pin "5") (pinfunction "SDO_5") (pintype "bidirectional"))
    )
    (net (code "397") (name "PIXEL_55") (class "Default")
      (node (ref "IC22") (pin "5") (pinfunction "SDO_5") (pintype "bidirectional"))
      (node (ref "IC23") (pin "6") (pinfunction "SDI_6") (pintype "bidirectional"))
    )
    (net (code "398") (name "PIXEL_56") (class "Default")
      (node (ref "IC22") (pin "6") (pinfunction "SDI_6") (pintype "bidirectional"))
      (node (ref "IC29") (pin "5") (pinfunction "SDO_5") (pintype "bidirectional"))
    )
    (net (code "399") (name "PIXEL_57") (class "Default")
      (node (ref "IC28") (pin "5") (pinfunction "SDO_5") (pintype "bidirectional"))
      (node (ref "IC29") (pin "6") (pinfunction "SDI_6") (pintype "bidirectional"))
    )
    (net (code "400") (name "PIXEL_61") (class "Default")
      (node (ref "IC32") (pin "6") (pinfunction "SDI_6") (pintype "bidirectional"))
      (node (ref "IC33") (pin "5") (pinfunction "SDO_5") (pintype "bidirectional"))
    )
    (net (code "401") (name "PIXEL_62") (class "Default")
      (node (ref "IC31") (pin "6") (pinfunction "SDI_6") (pintype "bidirectional"))
      (node (ref "IC32") (pin "5") (pinfunction "SDO_5") (pintype "bidirectional"))
    )
    (net (code "402") (name "PIXEL_63") (class "Default")
      (node (ref "IC30") (pin "6") (pinfunction "SDI_6") (pintype "bidirectional"))
      (node (ref "IC31") (pin "5") (pinfunction "SDO_5") (pintype "bidirectional"))
    )
    (net (code "403") (name "PIXEL_64") (class "Default")
      (node (ref "IC26") (pin "6") (pinfunction "SDI_6") (pintype "bidirectional"))
      (node (ref "IC30") (pin "5") (pinfunction "SDO_5") (pintype "bidirectional"))
    )
    (net (code "404") (name "RST") (class "Default")
      (node (ref "CON_NORTH_BRD") (pin "3") (pinfunction "3_3") (pintype "passive"))
      (node (ref "MCP_000") (pin "18") (pinfunction "~{RESET}_18") (pintype "bidirectional"))
      (node (ref "MCP_001") (pin "18") (pinfunction "~{RESET}_18") (pintype "bidirectional"))
      (node (ref "MCP_010") (pin "18") (pinfunction "~{RESET}_18") (pintype "bidirectional"))
      (node (ref "MCP_011") (pin "18") (pinfunction "~{RESET}_18") (pintype "bidirectional"))
      (node (ref "MCP_100") (pin "18") (pinfunction "~{RESET}_18") (pintype "bidirectional"))
    )
    (net (code "405") (name "SPI1_MOSI") (class "Default")
      (node (ref "CON_NORTH_BRD") (pin "6") (pinfunction "6_6") (pintype "passive"))
      (node (ref "IC14") (pin "6") (pinfunction "SDI_6") (pintype "bidirectional"))
    )
    (net (code "406") (name "SPI3_MOSI") (class "Default")
      (node (ref "CON_NORTH_BRD") (pin "19") (pinfunction "19_19") (pintype "passive"))
      (node (ref "IC25") (pin "6") (pinfunction "SDI_6") (pintype "bidirectional"))
    )
    (net (code "407") (name "unconnected-(IC1-TEST-Pad7)") (class "Default")
      (node (ref "IC1") (pin "7") (pinfunction "TEST_7") (pintype "bidirectional"))
    )
    (net (code "408") (name "unconnected-(IC2-TEST-Pad7)") (class "Default")
      (node (ref "IC2") (pin "7") (pinfunction "TEST_7") (pintype "bidirectional"))
    )
    (net (code "409") (name "unconnected-(IC3-TEST-Pad7)") (class "Default")
      (node (ref "IC3") (pin "7") (pinfunction "TEST_7") (pintype "bidirectional"))
    )
    (net (code "410") (name "unconnected-(IC4-TEST-Pad7)") (class "Default")
      (node (ref "IC4") (pin "7") (pinfunction "TEST_7") (pintype "bidirectional"))
    )
    (net (code "411") (name "unconnected-(IC5-TEST-Pad7)") (class "Default")
      (node (ref "IC5") (pin "7") (pinfunction "TEST_7") (pintype "bidirectional"))
    )
    (net (code "412") (name "unconnected-(IC6-TEST-Pad7)") (class "Default")
      (node (ref "IC6") (pin "7") (pinfunction "TEST_7") (pintype "bidirectional"))
    )
    (net (code "413") (name "unconnected-(IC7-TEST-Pad7)") (class "Default")
      (node (ref "IC7") (pin "7") (pinfunction "TEST_7") (pintype "bidirectional"))
    )
    (net (code "414") (name "unconnected-(IC8-TEST-Pad7)") (class "Default")
      (node (ref "IC8") (pin "7") (pinfunction "TEST_7") (pintype "bidirectional"))
    )
    (net (code "415") (name "unconnected-(IC9-TEST-Pad7)") (class "Default")
      (node (ref "IC9") (pin "7") (pinfunction "TEST_7") (pintype "bidirectional"))
    )
    (net (code "416") (name "unconnected-(IC10-TEST-Pad7)") (class "Default")
      (node (ref "IC10") (pin "7") (pinfunction "TEST_7") (pintype "bidirectional"))
    )
    (net (code "417") (name "unconnected-(IC11-TEST-Pad7)") (class "Default")
      (node (ref "IC11") (pin "7") (pinfunction "TEST_7") (pintype "bidirectional"))
    )
    (net (code "418") (name "unconnected-(IC12-TEST-Pad7)") (class "Default")
      (node (ref "IC12") (pin "7") (pinfunction "TEST_7") (pintype "bidirectional"))
    )
    (net (code "419") (name "unconnected-(IC13-SDO-Pad5)") (class "Default")
      (node (ref "IC13") (pin "5") (pinfunction "SDO_5") (pintype "bidirectional"))
    )
    (net (code "420") (name "unconnected-(IC13-TEST-Pad7)") (class "Default")
      (node (ref "IC13") (pin "7") (pinfunction "TEST_7") (pintype "bidirectional"))
    )
    (net (code "421") (name "unconnected-(IC14-TEST-Pad7)") (class "Default")
      (node (ref "IC14") (pin "7") (pinfunction "TEST_7") (pintype "bidirectional"))
    )
    (net (code "422") (name "unconnected-(IC15-TEST-Pad7)") (class "Default")
      (node (ref "IC15") (pin "7") (pinfunction "TEST_7") (pintype "bidirectional"))
    )
    (net (code "423") (name "unconnected-(IC16-TEST-Pad7)") (class "Default")
      (node (ref "IC16") (pin "7") (pinfunction "TEST_7") (pintype "bidirectional"))
    )
    (net (code "424") (name "unconnected-(IC17-TEST-Pad7)") (class "Default")
      (node (ref "IC17") (pin "7") (pinfunction "TEST_7") (pintype "bidirectional"))
    )
    (net (code "425") (name "unconnected-(IC18-TEST-Pad7)") (class "Default")
      (node (ref "IC18") (pin "7") (pinfunction "TEST_7") (pintype "bidirectional"))
    )
    (net (code "426") (name "unconnected-(IC19-TEST-Pad7)") (class "Default")
      (node (ref "IC19") (pin "7") (pinfunction "TEST_7") (pintype "bidirectional"))
    )
    (net (code "427") (name "unconnected-(IC20-TEST-Pad7)") (class "Default")
      (node (ref "IC20") (pin "7") (pinfunction "TEST_7") (pintype "bidirectional"))
    )
    (net (code "428") (name "unconnected-(IC21-TEST-Pad7)") (class "Default")
      (node (ref "IC21") (pin "7") (pinfunction "TEST_7") (pintype "bidirectional"))
    )
    (net (code "429") (name "unconnected-(IC22-TEST-Pad7)") (class "Default")
      (node (ref "IC22") (pin "7") (pinfunction "TEST_7") (pintype "bidirectional"))
    )
    (net (code "430") (name "unconnected-(IC23-TEST-Pad7)") (class "Default")
      (node (ref "IC23") (pin "7") (pinfunction "TEST_7") (pintype "bidirectional"))
    )
    (net (code "431") (name "unconnected-(IC24-TEST-Pad7)") (class "Default")
      (node (ref "IC24") (pin "7") (pinfunction "TEST_7") (pintype "bidirectional"))
    )
    (net (code "432") (name "unconnected-(IC25-TEST-Pad7)") (class "Default")
      (node (ref "IC25") (pin "7") (pinfunction "TEST_7") (pintype "bidirectional"))
    )
    (net (code "433") (name "unconnected-(IC26-SDO-Pad5)") (class "Default")
      (node (ref "IC26") (pin "5") (pinfunction "SDO_5") (pintype "bidirectional"))
    )
    (net (code "434") (name "unconnected-(IC26-TEST-Pad7)") (class "Default")
      (node (ref "IC26") (pin "7") (pinfunction "TEST_7") (pintype "bidirectional"))
    )
    (net (code "435") (name "unconnected-(IC27-TEST-Pad7)") (class "Default")
      (node (ref "IC27") (pin "7") (pinfunction "TEST_7") (pintype "bidirectional"))
    )
    (net (code "436") (name "unconnected-(IC28-TEST-Pad7)") (class "Default")
      (node (ref "IC28") (pin "7") (pinfunction "TEST_7") (pintype "bidirectional"))
    )
    (net (code "437") (name "unconnected-(IC29-TEST-Pad7)") (class "Default")
      (node (ref "IC29") (pin "7") (pinfunction "TEST_7") (pintype "bidirectional"))
    )
    (net (code "438") (name "unconnected-(IC30-TEST-Pad7)") (class "Default")
      (node (ref "IC30") (pin "7") (pinfunction "TEST_7") (pintype "bidirectional"))
    )
    (net (code "439") (name "unconnected-(IC31-TEST-Pad7)") (class "Default")
      (node (ref "IC31") (pin "7") (pinfunction "TEST_7") (pintype "bidirectional"))
    )
    (net (code "440") (name "unconnected-(IC32-TEST-Pad7)") (class "Default")
      (node (ref "IC32") (pin "7") (pinfunction "TEST_7") (pintype "bidirectional"))
    )
    (net (code "441") (name "unconnected-(IC33-TEST-Pad7)") (class "Default")
      (node (ref "IC33") (pin "7") (pinfunction "TEST_7") (pintype "bidirectional"))
    )
    (net (code "442") (name "unconnected-(MCP_001-GPB0-Pad1)") (class "Default")
      (node (ref "MCP_001") (pin "1") (pinfunction "GPB0_1") (pintype "bidirectional"))
    )
  )
)
